# EEZ_DIB_MIO168_r1B1.net
KiCad netlist of a schematic drawn in EAGLE
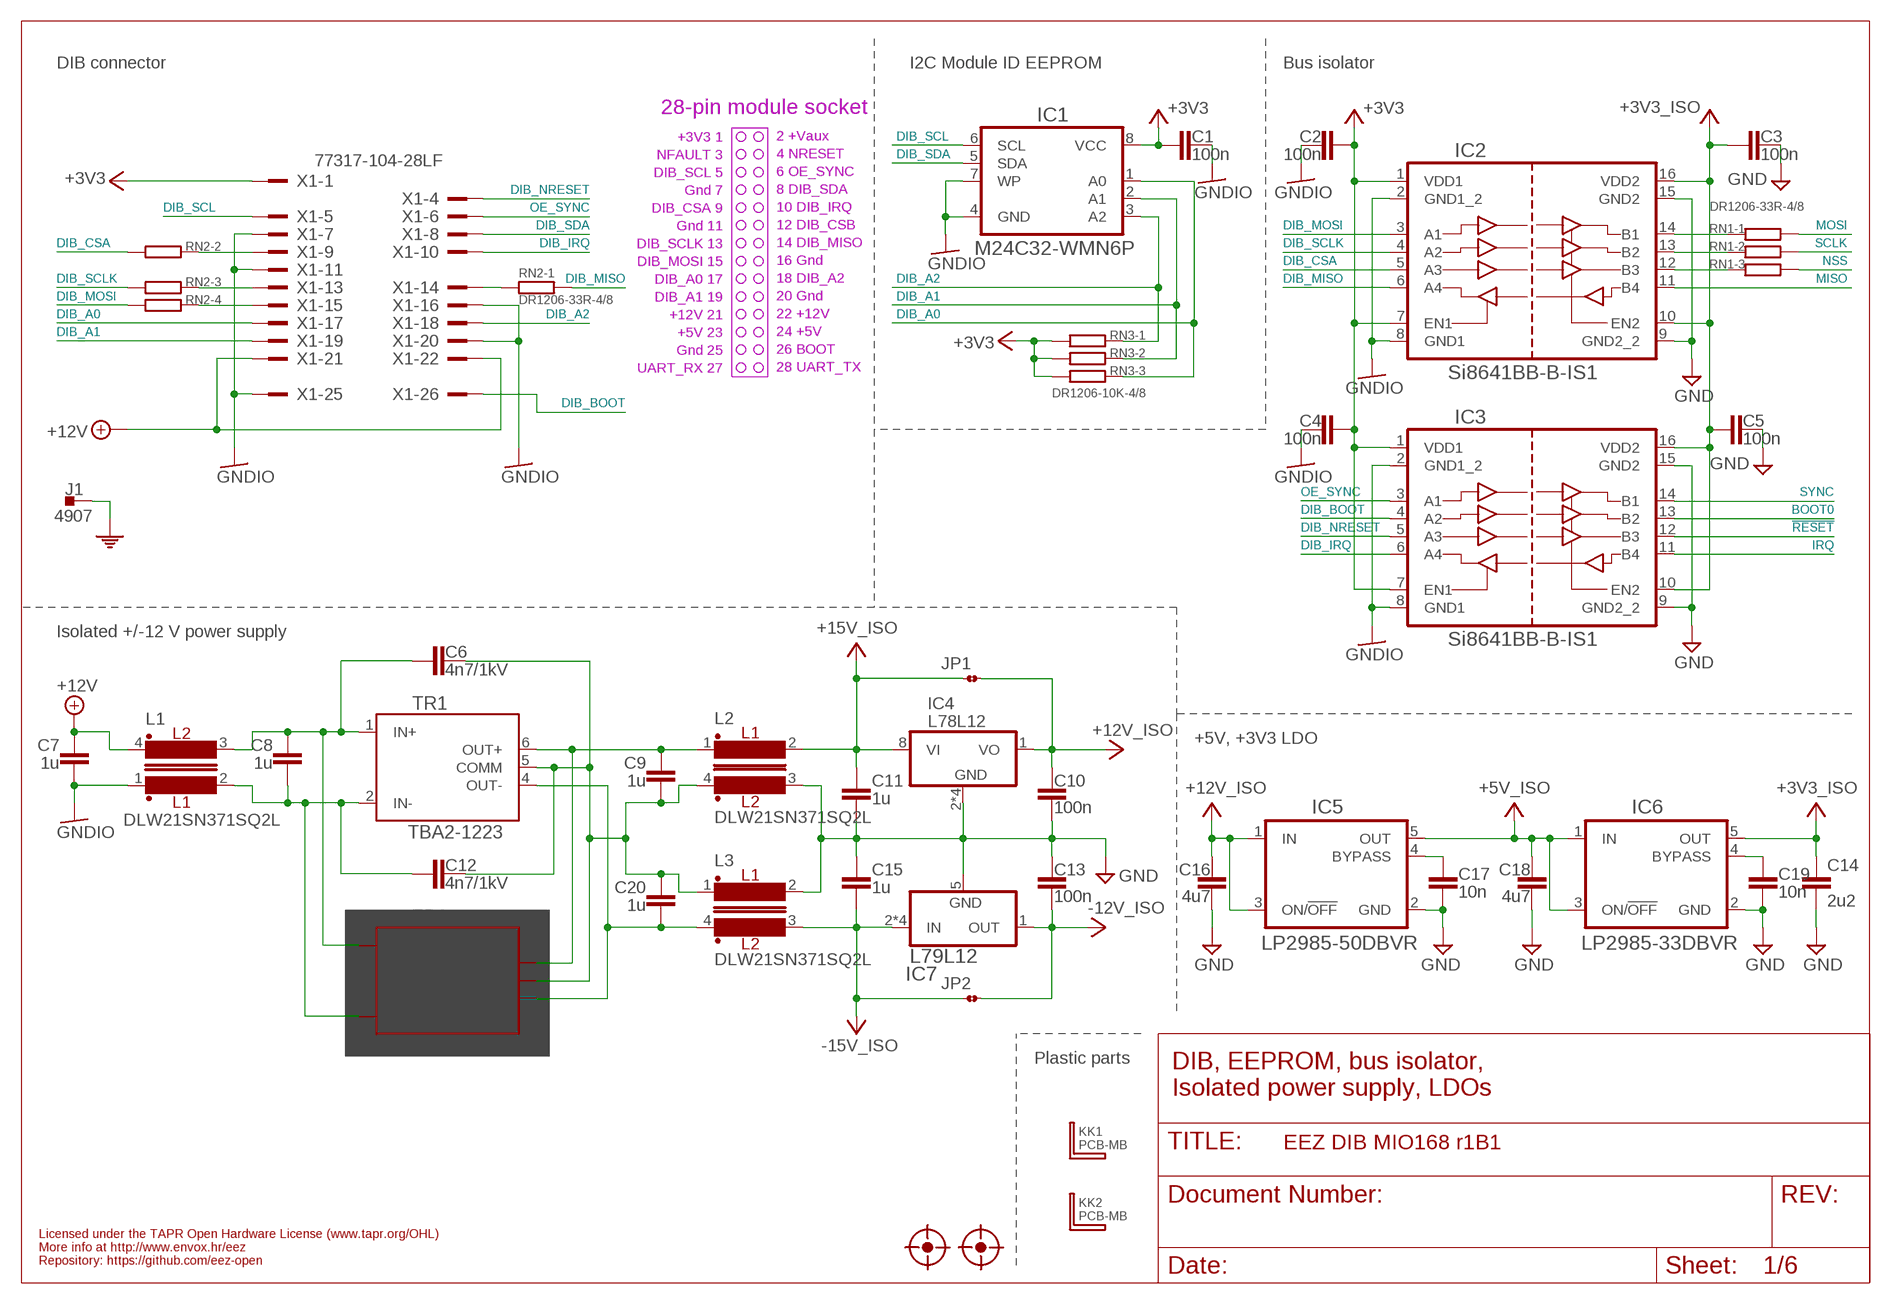
[diagram p0: schematic, sheet 1]
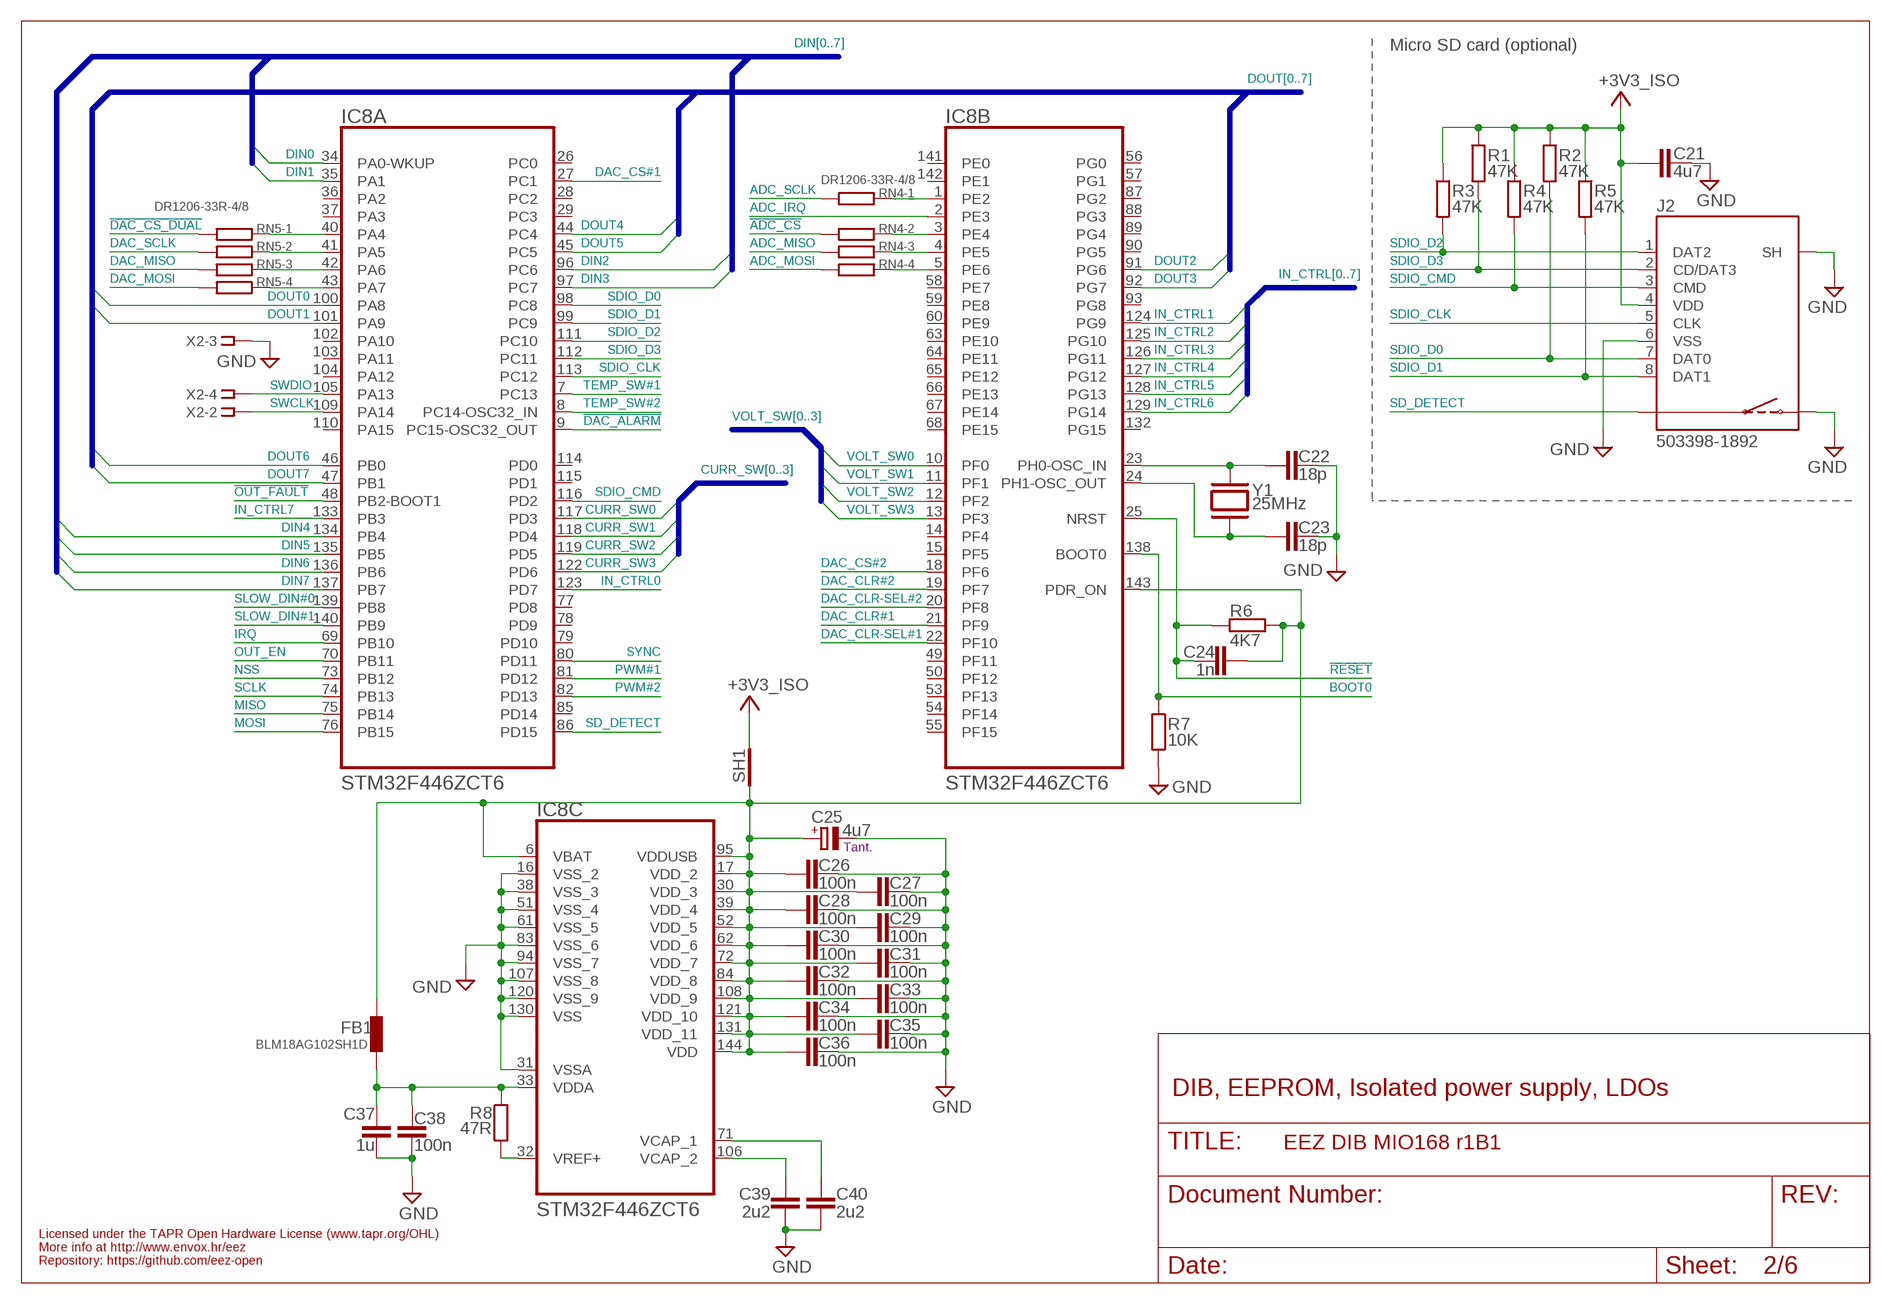
[diagram p1: schematic, sheet 2]
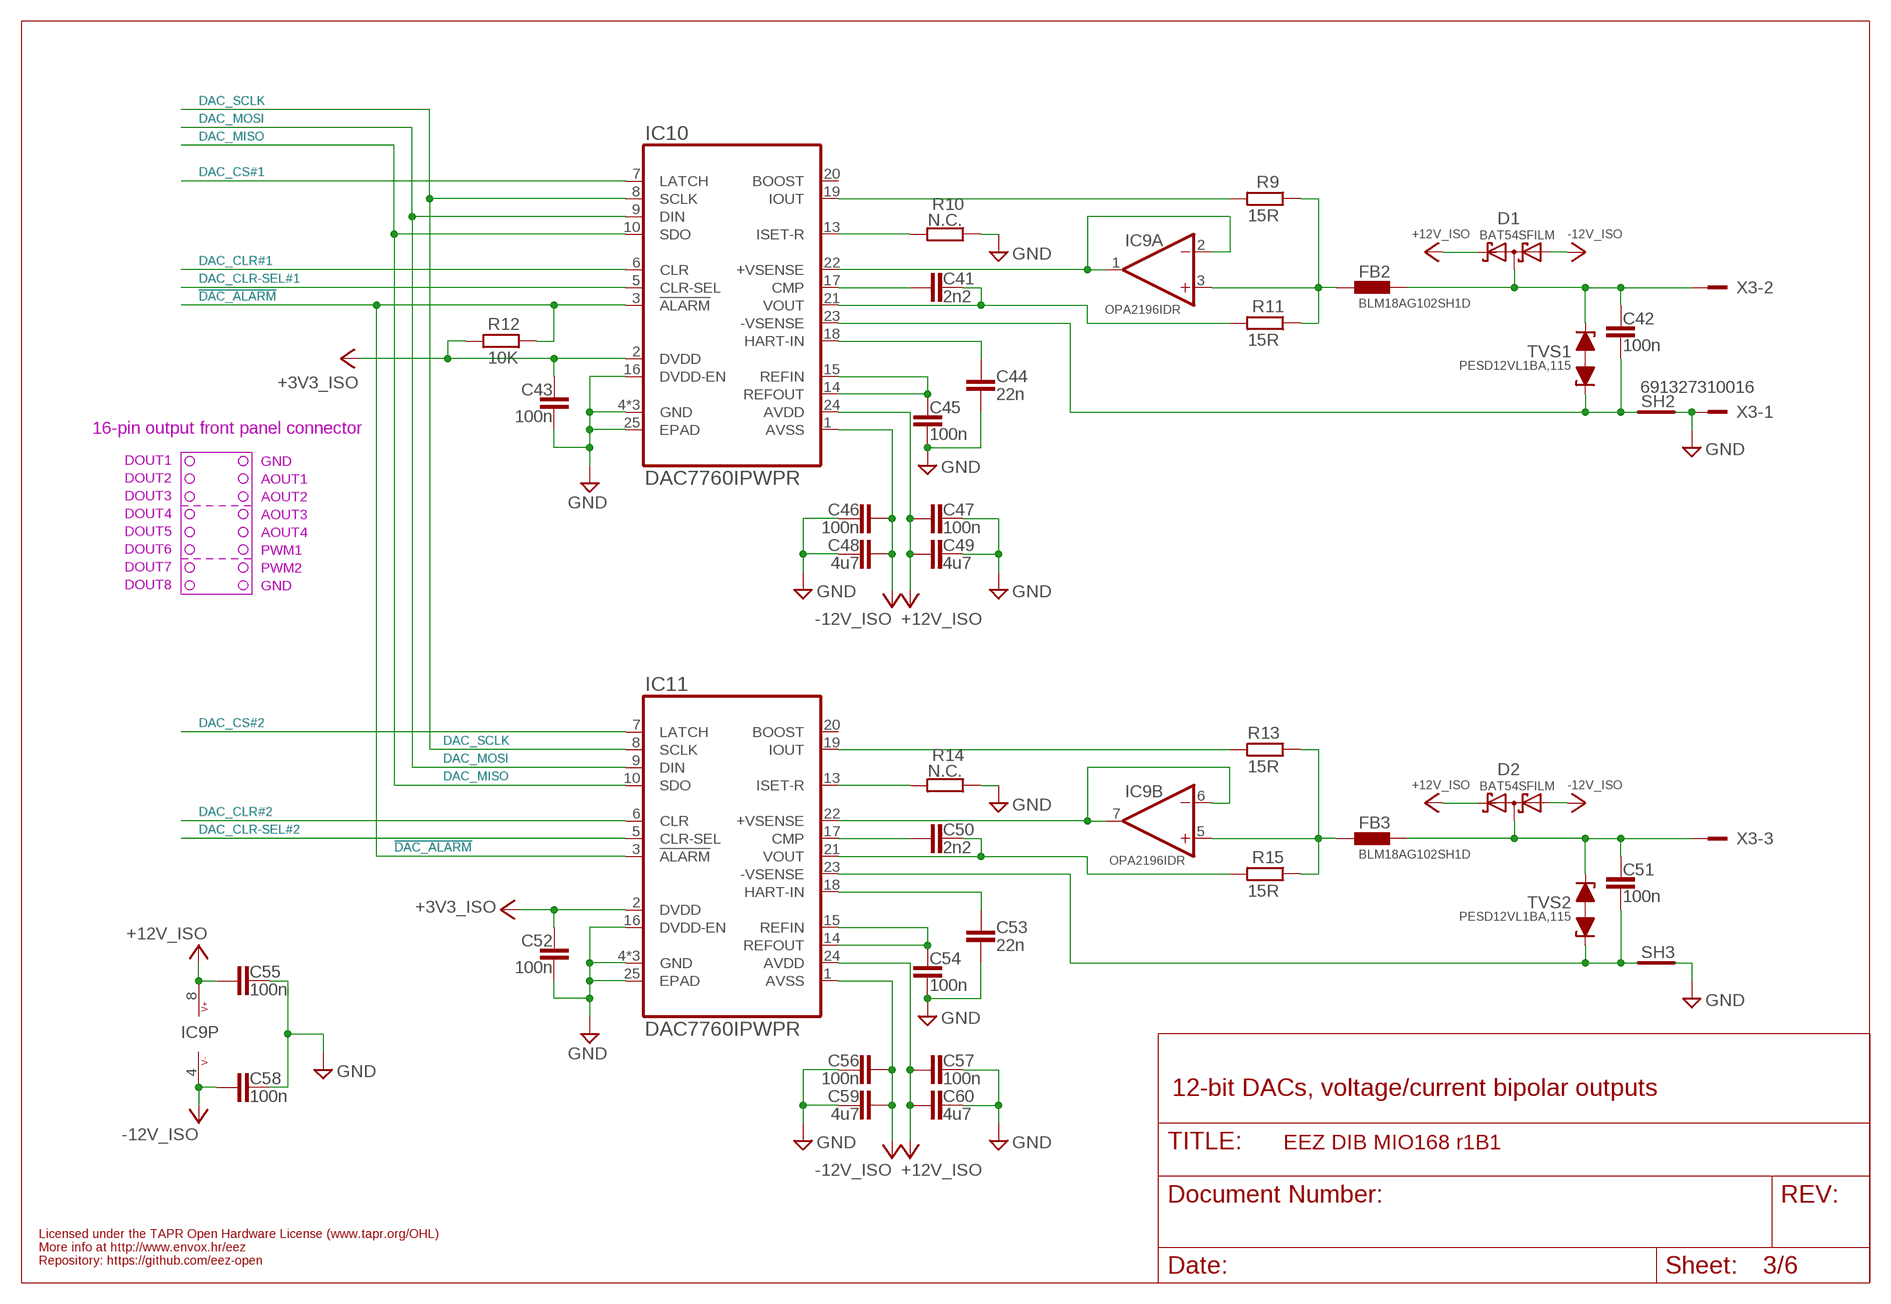
[diagram p2: schematic, sheet 3]
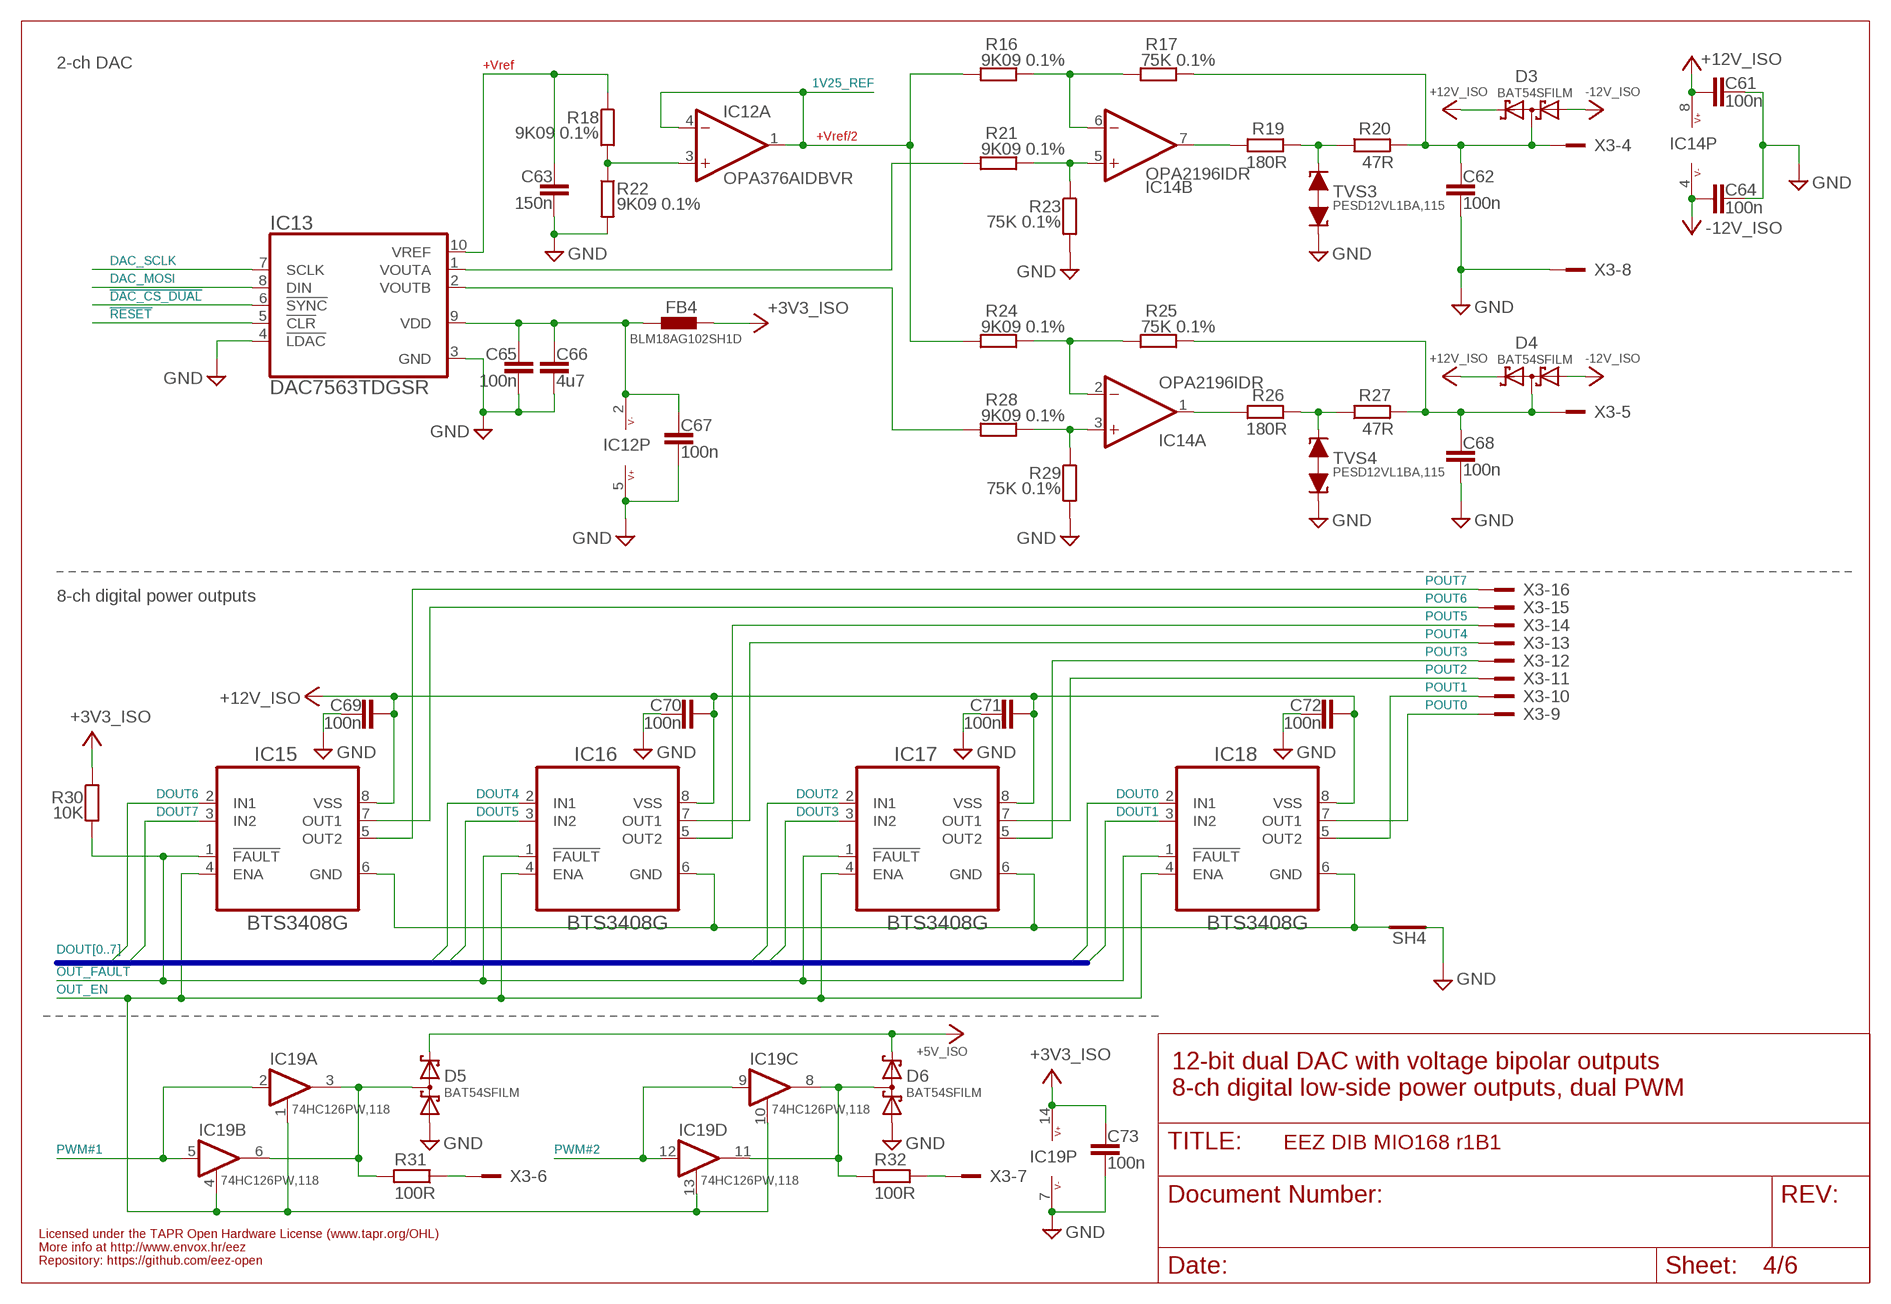
[diagram p3: schematic, sheet 4]
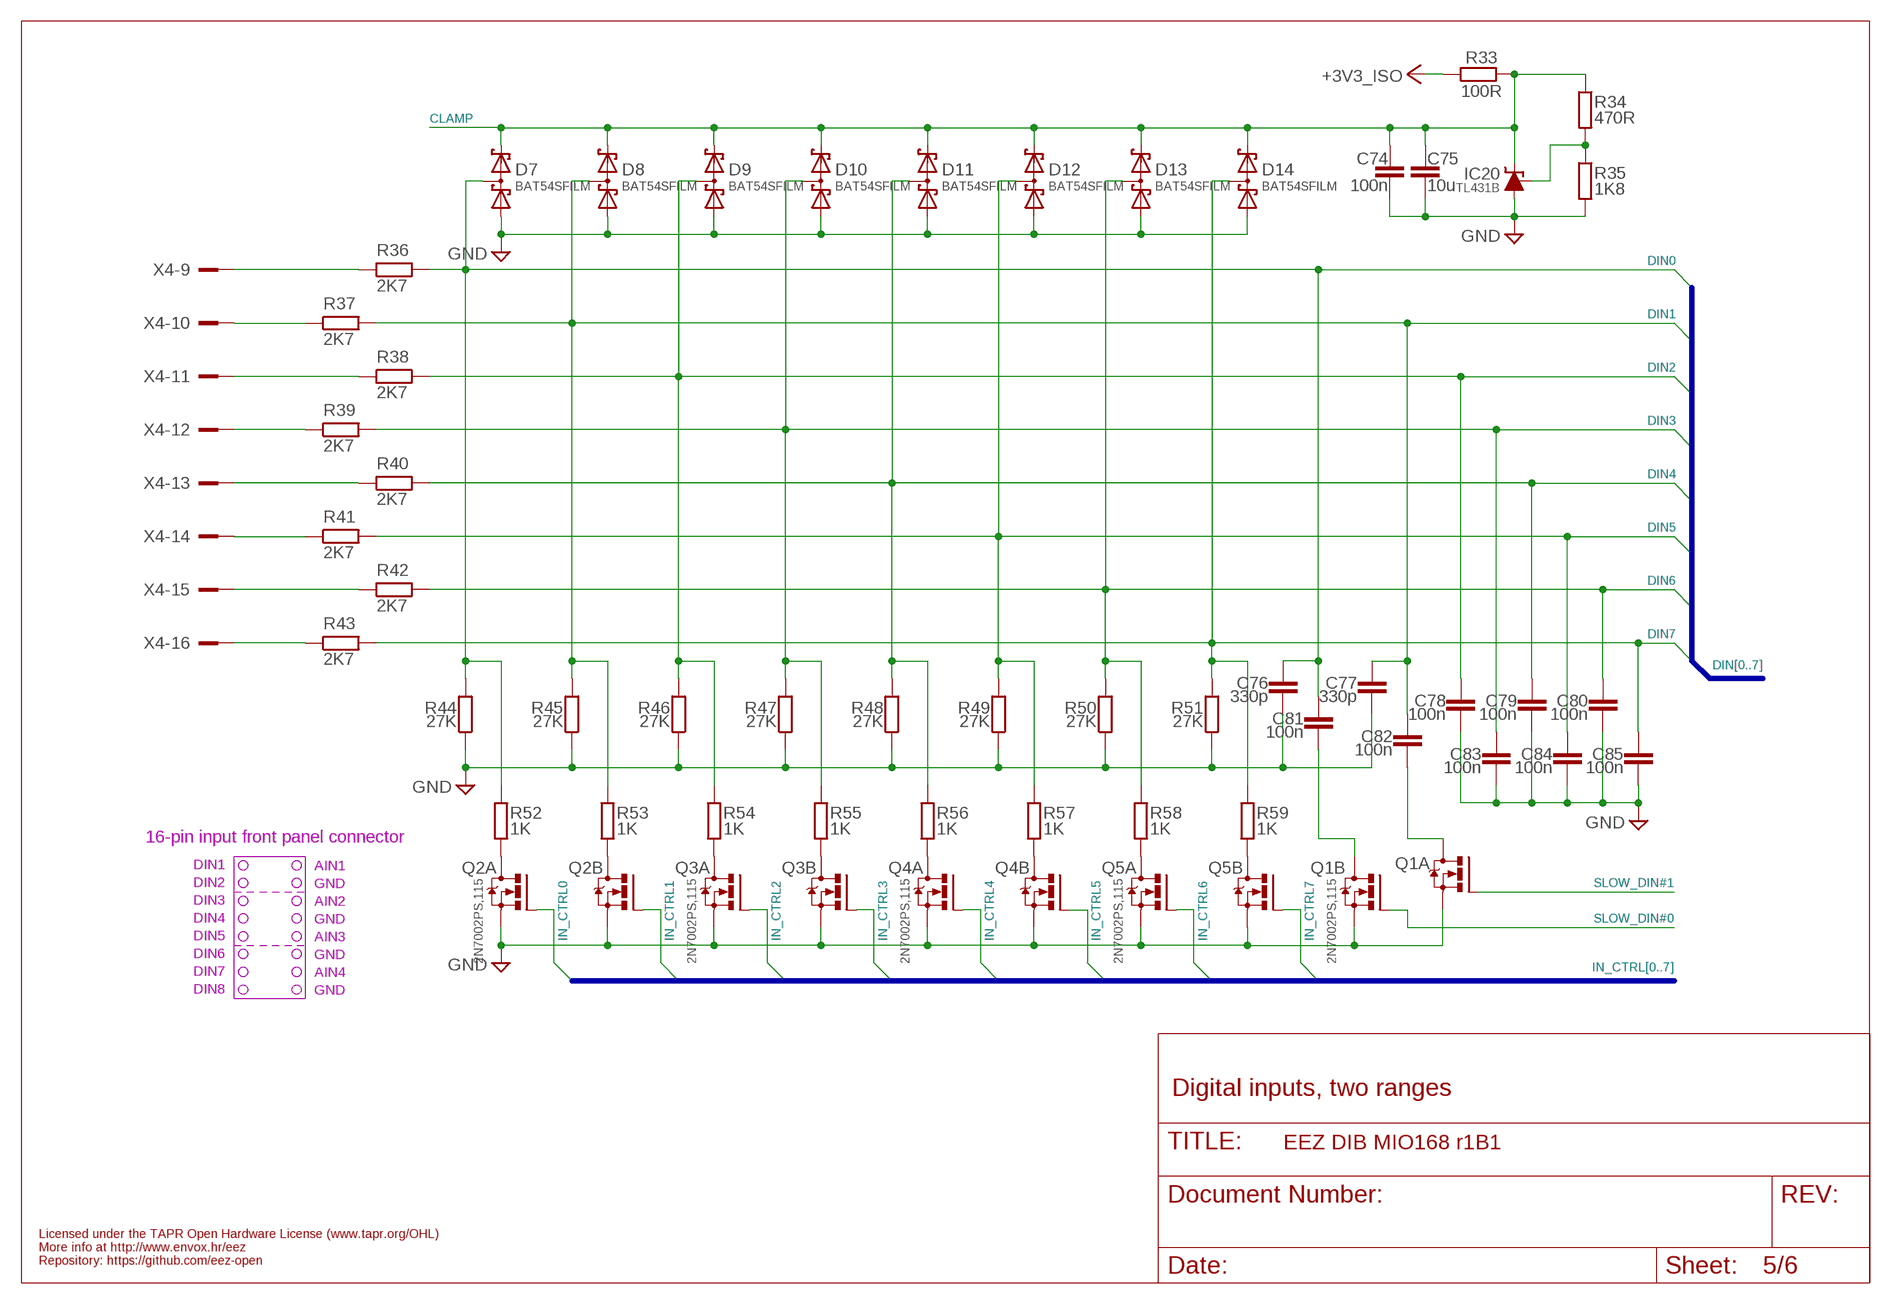
[diagram p4: schematic, sheet 5]
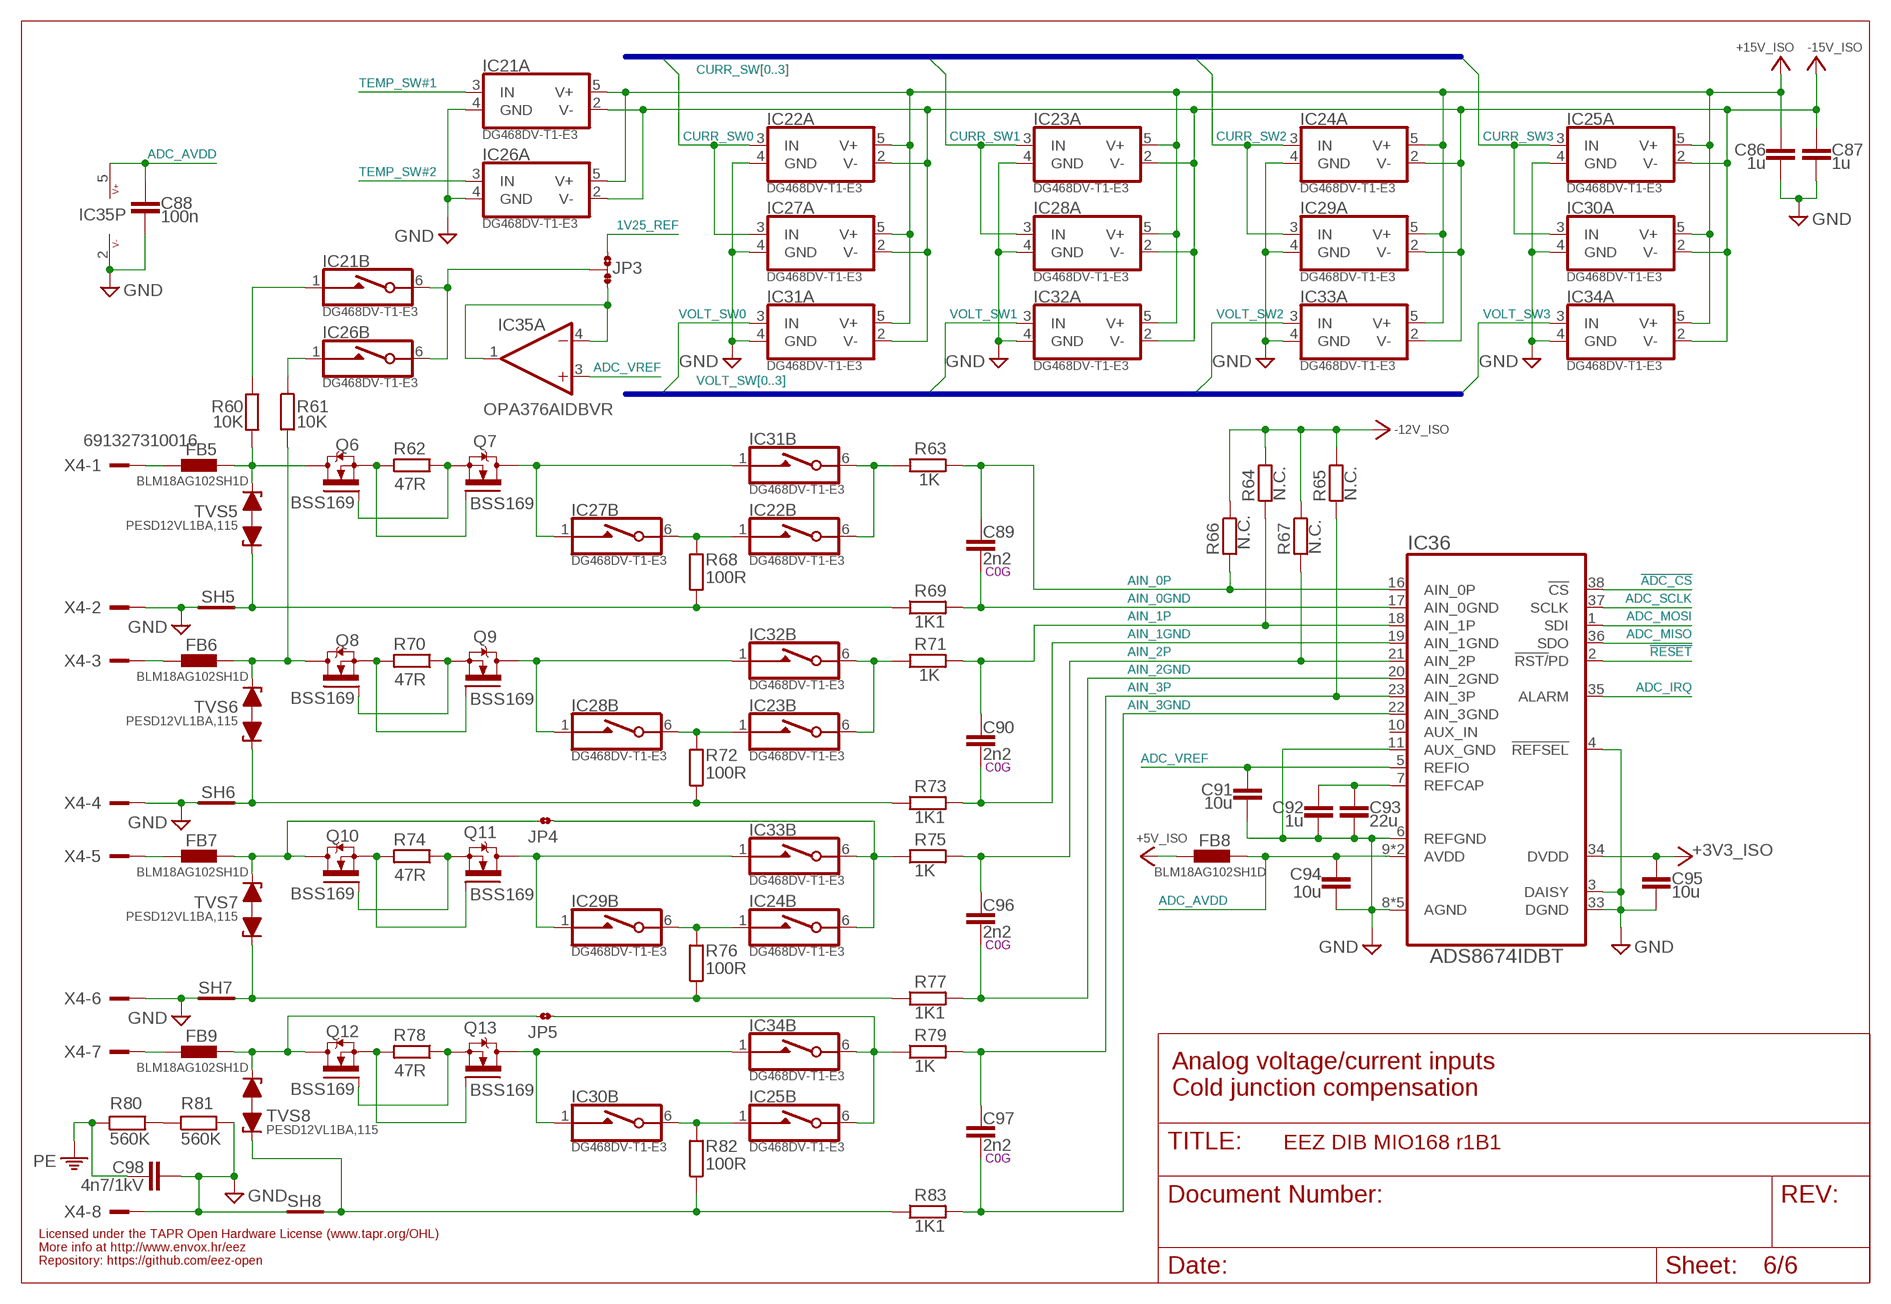
[diagram p5: schematic, sheet 6]

(export (version "E")
  (design (tool "Eeschema 10.0.6"))
  (components
    (comp (ref "C41")
      (value "2n2")
      (footprint "eagle-import:C0805")
      (libsource (lib "eagle-import") (part "C-EUC0805"))
    )
    (comp (ref "C42")
      (value "100n")
      (footprint "eagle-import:C0603")
      (libsource (lib "eagle-import") (part "C-EUC0603"))
    )
    (comp (ref "C43")
      (value "100n")
      (footprint "eagle-import:C0603")
      (libsource (lib "eagle-import") (part "C-EUC0603"))
    )
    (comp (ref "C44")
      (value "22n")
      (footprint "eagle-import:C0805")
      (libsource (lib "eagle-import") (part "C-EUC0805"))
    )
    (comp (ref "C45")
      (value "100n")
      (footprint "eagle-import:C0603")
      (libsource (lib "eagle-import") (part "C-EUC0603"))
    )
    (comp (ref "C46")
      (value "100n")
      (footprint "eagle-import:C0603")
      (libsource (lib "eagle-import") (part "C-EUC0603"))
    )
    (comp (ref "C47")
      (value "100n")
      (footprint "eagle-import:C0603")
      (libsource (lib "eagle-import") (part "C-EUC0603"))
    )
    (comp (ref "C48")
      (value "4u7")
      (footprint "eagle-import:C0805")
      (libsource (lib "eagle-import") (part "C-EUC0805"))
    )
    (comp (ref "C49")
      (value "4u7")
      (footprint "eagle-import:C0805")
      (libsource (lib "eagle-import") (part "C-EUC0805"))
    )
    (comp (ref "C50")
      (value "2n2")
      (footprint "eagle-import:C0805")
      (libsource (lib "eagle-import") (part "C-EUC0805"))
    )
    (comp (ref "C51")
      (value "100n")
      (footprint "eagle-import:C0603")
      (libsource (lib "eagle-import") (part "C-EUC0603"))
    )
    (comp (ref "C52")
      (value "100n")
      (footprint "eagle-import:C0603")
      (libsource (lib "eagle-import") (part "C-EUC0603"))
    )
    (comp (ref "C53")
      (value "22n")
      (footprint "eagle-import:C0805")
      (libsource (lib "eagle-import") (part "C-EUC0805"))
    )
    (comp (ref "C54")
      (value "100n")
      (footprint "eagle-import:C0603")
      (libsource (lib "eagle-import") (part "C-EUC0603"))
    )
    (comp (ref "C55")
      (value "100n")
      (footprint "eagle-import:C0603")
      (libsource (lib "eagle-import") (part "C-EUC0603"))
    )
    (comp (ref "C56")
      (value "100n")
      (footprint "eagle-import:C0603")
      (libsource (lib "eagle-import") (part "C-EUC0603"))
    )
    (comp (ref "C57")
      (value "100n")
      (footprint "eagle-import:C0603")
      (libsource (lib "eagle-import") (part "C-EUC0603"))
    )
    (comp (ref "C58")
      (value "100n")
      (footprint "eagle-import:C0603")
      (libsource (lib "eagle-import") (part "C-EUC0603"))
    )
    (comp (ref "C59")
      (value "4u7")
      (footprint "eagle-import:C0805")
      (libsource (lib "eagle-import") (part "C-EUC0805"))
    )
    (comp (ref "C60")
      (value "4u7")
      (footprint "eagle-import:C0805")
      (libsource (lib "eagle-import") (part "C-EUC0805"))
    )
    (comp (ref "D1")
      (value "BAT54SFILM")
      (footprint "eagle-import:SOT23")
      (libsource (lib "eagle-import") (part "BAT54S"))
    )
    (comp (ref "D2")
      (value "BAT54SFILM")
      (footprint "eagle-import:SOT23")
      (libsource (lib "eagle-import") (part "BAT54S"))
    )
    (comp (ref "FB2")
      (value "BLM18AG102SH1D")
      (footprint "eagle-import:BEAD0603")
      (libsource (lib "eagle-import") (part "FERRITE_BEAD0603"))
    )
    (comp (ref "FB3")
      (value "BLM18AG102SH1D")
      (footprint "eagle-import:BEAD0603")
      (libsource (lib "eagle-import") (part "FERRITE_BEAD0603"))
    )
    (comp (ref "IC9")
      (value "OPA2196IDR")
      (footprint "eagle-import:SOIC127P600X173-8N")
      (libsource (lib "eagle-import") (part "TL072SOIC8"))
    )
    (comp (ref "IC10")
      (value "DAC7760IPWPR")
      (footprint "eagle-import:PWP24")
      (libsource (lib "eagle-import") (part "DAC7760IPWPR"))
    )
    (comp (ref "IC11")
      (value "DAC7760IPWPR")
      (footprint "eagle-import:PWP24")
      (libsource (lib "eagle-import") (part "DAC7760IPWPR"))
    )
    (comp (ref "R9")
      (value "15R")
      (footprint "eagle-import:R0805")
      (libsource (lib "eagle-import") (part "R-EU_R0805"))
    )
    (comp (ref "R10")
      (value "N.C.")
      (footprint "eagle-import:R0805")
      (libsource (lib "eagle-import") (part "R-EU_R0805"))
    )
    (comp (ref "R11")
      (value "15R")
      (footprint "eagle-import:R0805")
      (libsource (lib "eagle-import") (part "R-EU_R0805"))
    )
    (comp (ref "R12")
      (value "10K")
      (footprint "eagle-import:R0805")
      (libsource (lib "eagle-import") (part "R-EU_R0805"))
    )
    (comp (ref "R13")
      (value "15R")
      (footprint "eagle-import:R0805")
      (libsource (lib "eagle-import") (part "R-EU_R0805"))
    )
    (comp (ref "R14")
      (value "N.C.")
      (footprint "eagle-import:R0805")
      (libsource (lib "eagle-import") (part "R-EU_R0805"))
    )
    (comp (ref "R15")
      (value "15R")
      (footprint "eagle-import:R0805")
      (libsource (lib "eagle-import") (part "R-EU_R0805"))
    )
    (comp (ref "SH2")
      (value "SHORTNOHOLE")
      (footprint "eagle-import:SHORT_NOHOLE")
      (libsource (lib "eagle-import") (part "SHORTNOHOLE"))
    )
    (comp (ref "SH3")
      (value "SHORTNOHOLE")
      (footprint "eagle-import:SHORT_NOHOLE")
      (libsource (lib "eagle-import") (part "SHORTNOHOLE"))
    )
    (comp (ref "TVS1")
      (value "PESD12VL1BA,115")
      (footprint "eagle-import:SOD323-BIDIR")
      (libsource (lib "eagle-import") (part "PESDXL1BA"))
    )
    (comp (ref "TVS2")
      (value "PESD12VL1BA,115")
      (footprint "eagle-import:SOD323-BIDIR")
      (libsource (lib "eagle-import") (part "PESDXL1BA"))
    )
    (comp (ref "X3")
      (value "691327310016")
      (footprint "eagle-import:691327310016")
      (libsource (lib "eagle-import") (part "691327310016"))
    )
    (comp (ref "C74")
      (value "100n")
      (footprint "eagle-import:C0603")
      (libsource (lib "eagle-import") (part "C-EUC0603"))
    )
    (comp (ref "C75")
      (value "10u")
      (footprint "eagle-import:C1206")
      (libsource (lib "eagle-import") (part "C-EUC1206"))
    )
    (comp (ref "C76")
      (value "330p")
      (footprint "eagle-import:C0805")
      (libsource (lib "eagle-import") (part "C-EUC0805"))
    )
    (comp (ref "C77")
      (value "330p")
      (footprint "eagle-import:C0805")
      (libsource (lib "eagle-import") (part "C-EUC0805"))
    )
    (comp (ref "C78")
      (value "100n")
      (footprint "eagle-import:C0603")
      (libsource (lib "eagle-import") (part "C-EUC0603"))
    )
    (comp (ref "C79")
      (value "100n")
      (footprint "eagle-import:C0603")
      (libsource (lib "eagle-import") (part "C-EUC0603"))
    )
    (comp (ref "C80")
      (value "100n")
      (footprint "eagle-import:C0603")
      (libsource (lib "eagle-import") (part "C-EUC0603"))
    )
    (comp (ref "C81")
      (value "100n")
      (footprint "eagle-import:C0603")
      (libsource (lib "eagle-import") (part "C-EUC0603"))
    )
    (comp (ref "C82")
      (value "100n")
      (footprint "eagle-import:C0603")
      (libsource (lib "eagle-import") (part "C-EUC0603"))
    )
    (comp (ref "C83")
      (value "100n")
      (footprint "eagle-import:C0603")
      (libsource (lib "eagle-import") (part "C-EUC0603"))
    )
    (comp (ref "C84")
      (value "100n")
      (footprint "eagle-import:C0603")
      (libsource (lib "eagle-import") (part "C-EUC0603"))
    )
    (comp (ref "C85")
      (value "100n")
      (footprint "eagle-import:C0603")
      (libsource (lib "eagle-import") (part "C-EUC0603"))
    )
    (comp (ref "D7")
      (value "BAT54SFILM")
      (footprint "eagle-import:SOT23")
      (libsource (lib "eagle-import") (part "BAT54S"))
    )
    (comp (ref "D8")
      (value "BAT54SFILM")
      (footprint "eagle-import:SOT23")
      (libsource (lib "eagle-import") (part "BAT54S"))
    )
    (comp (ref "D9")
      (value "BAT54SFILM")
      (footprint "eagle-import:SOT23")
      (libsource (lib "eagle-import") (part "BAT54S"))
    )
    (comp (ref "D10")
      (value "BAT54SFILM")
      (footprint "eagle-import:SOT23")
      (libsource (lib "eagle-import") (part "BAT54S"))
    )
    (comp (ref "D11")
      (value "BAT54SFILM")
      (footprint "eagle-import:SOT23")
      (libsource (lib "eagle-import") (part "BAT54S"))
    )
    (comp (ref "D12")
      (value "BAT54SFILM")
      (footprint "eagle-import:SOT23")
      (libsource (lib "eagle-import") (part "BAT54S"))
    )
    (comp (ref "D13")
      (value "BAT54SFILM")
      (footprint "eagle-import:SOT23")
      (libsource (lib "eagle-import") (part "BAT54S"))
    )
    (comp (ref "D14")
      (value "BAT54SFILM")
      (footprint "eagle-import:SOT23")
      (libsource (lib "eagle-import") (part "BAT54S"))
    )
    (comp (ref "IC20")
      (value "TL431B")
      (footprint "eagle-import:SOT103P240X110-3N")
      (libsource (lib "eagle-import") (part "TL431"))
    )
    (comp (ref "Q1")
      (value "2N7002PS,115")
      (footprint "eagle-import:SC88")
      (libsource (lib "eagle-import") (part "2N7002PS,115"))
    )
    (comp (ref "Q2")
      (value "2N7002PS,115")
      (footprint "eagle-import:SC88")
      (libsource (lib "eagle-import") (part "2N7002PS,115"))
    )
    (comp (ref "Q3")
      (value "2N7002PS,115")
      (footprint "eagle-import:SC88")
      (libsource (lib "eagle-import") (part "2N7002PS,115"))
    )
    (comp (ref "Q4")
      (value "2N7002PS,115")
      (footprint "eagle-import:SC88")
      (libsource (lib "eagle-import") (part "2N7002PS,115"))
    )
    (comp (ref "Q5")
      (value "2N7002PS,115")
      (footprint "eagle-import:SC88")
      (libsource (lib "eagle-import") (part "2N7002PS,115"))
    )
    (comp (ref "R33")
      (value "100R")
      (footprint "eagle-import:R0805")
      (libsource (lib "eagle-import") (part "R-EU_R0805"))
    )
    (comp (ref "R34")
      (value "470R")
      (footprint "eagle-import:R0805")
      (libsource (lib "eagle-import") (part "R-EU_R0805"))
    )
    (comp (ref "R35")
      (value "1K8")
      (footprint "eagle-import:R0805")
      (libsource (lib "eagle-import") (part "R-EU_R0805"))
    )
    (comp (ref "R36")
      (value "2K7")
      (footprint "eagle-import:R1206")
      (libsource (lib "eagle-import") (part "R-EU_R1206"))
    )
    (comp (ref "R37")
      (value "2K7")
      (footprint "eagle-import:R1206")
      (libsource (lib "eagle-import") (part "R-EU_R1206"))
    )
    (comp (ref "R38")
      (value "2K7")
      (footprint "eagle-import:R1206")
      (libsource (lib "eagle-import") (part "R-EU_R1206"))
    )
    (comp (ref "R39")
      (value "2K7")
      (footprint "eagle-import:R1206")
      (libsource (lib "eagle-import") (part "R-EU_R1206"))
    )
    (comp (ref "R40")
      (value "2K7")
      (footprint "eagle-import:R1206")
      (libsource (lib "eagle-import") (part "R-EU_R1206"))
    )
    (comp (ref "R41")
      (value "2K7")
      (footprint "eagle-import:R1206")
      (libsource (lib "eagle-import") (part "R-EU_R1206"))
    )
    (comp (ref "R42")
      (value "2K7")
      (footprint "eagle-import:R1206")
      (libsource (lib "eagle-import") (part "R-EU_R1206"))
    )
    (comp (ref "R43")
      (value "2K7")
      (footprint "eagle-import:R1206")
      (libsource (lib "eagle-import") (part "R-EU_R1206"))
    )
    (comp (ref "R44")
      (value "27K")
      (footprint "eagle-import:R0805")
      (libsource (lib "eagle-import") (part "R-EU_R0805"))
    )
    (comp (ref "R45")
      (value "27K")
      (footprint "eagle-import:R0805")
      (libsource (lib "eagle-import") (part "R-EU_R0805"))
    )
    (comp (ref "R46")
      (value "27K")
      (footprint "eagle-import:R0805")
      (libsource (lib "eagle-import") (part "R-EU_R0805"))
    )
    (comp (ref "R47")
      (value "27K")
      (footprint "eagle-import:R0805")
      (libsource (lib "eagle-import") (part "R-EU_R0805"))
    )
    (comp (ref "R48")
      (value "27K")
      (footprint "eagle-import:R0805")
      (libsource (lib "eagle-import") (part "R-EU_R0805"))
    )
    (comp (ref "R49")
      (value "27K")
      (footprint "eagle-import:R0805")
      (libsource (lib "eagle-import") (part "R-EU_R0805"))
    )
    (comp (ref "R50")
      (value "27K")
      (footprint "eagle-import:R0805")
      (libsource (lib "eagle-import") (part "R-EU_R0805"))
    )
    (comp (ref "R51")
      (value "27K")
      (footprint "eagle-import:R0805")
      (libsource (lib "eagle-import") (part "R-EU_R0805"))
    )
    (comp (ref "R52")
      (value "1K")
      (footprint "eagle-import:R0805")
      (libsource (lib "eagle-import") (part "R-EU_R0805"))
    )
    (comp (ref "R53")
      (value "1K")
      (footprint "eagle-import:R0805")
      (libsource (lib "eagle-import") (part "R-EU_R0805"))
    )
    (comp (ref "R54")
      (value "1K")
      (footprint "eagle-import:R0805")
      (libsource (lib "eagle-import") (part "R-EU_R0805"))
    )
    (comp (ref "R55")
      (value "1K")
      (footprint "eagle-import:R0805")
      (libsource (lib "eagle-import") (part "R-EU_R0805"))
    )
    (comp (ref "R56")
      (value "1K")
      (footprint "eagle-import:R0805")
      (libsource (lib "eagle-import") (part "R-EU_R0805"))
    )
    (comp (ref "R57")
      (value "1K")
      (footprint "eagle-import:R0805")
      (libsource (lib "eagle-import") (part "R-EU_R0805"))
    )
    (comp (ref "R58")
      (value "1K")
      (footprint "eagle-import:R0805")
      (libsource (lib "eagle-import") (part "R-EU_R0805"))
    )
    (comp (ref "R59")
      (value "1K")
      (footprint "eagle-import:R0805")
      (libsource (lib "eagle-import") (part "R-EU_R0805"))
    )
    (comp (ref "X4")
      (value "691327310016")
      (footprint "eagle-import:691327310016")
      (libsource (lib "eagle-import") (part "691327310016"))
    )
    (comp (ref "C21")
      (value "4u7")
      (footprint "eagle-import:C0805")
      (libsource (lib "eagle-import") (part "C-EUC0805"))
    )
    (comp (ref "C22")
      (value "18p")
      (footprint "eagle-import:C0603")
      (libsource (lib "eagle-import") (part "C-EUC0603"))
    )
    (comp (ref "C23")
      (value "18p")
      (footprint "eagle-import:C0603")
      (libsource (lib "eagle-import") (part "C-EUC0603"))
    )
    (comp (ref "C24")
      (value "1n")
      (footprint "eagle-import:C0805")
      (libsource (lib "eagle-import") (part "C-EUC0805"))
    )
    (comp (ref "C25")
      (value "4u7")
      (footprint "eagle-import:EC1206")
      (libsource (lib "eagle-import") (part "ECAP1206"))
    )
    (comp (ref "C26")
      (value "100n")
      (footprint "eagle-import:C0603")
      (libsource (lib "eagle-import") (part "C-EUC0603"))
    )
    (comp (ref "C27")
      (value "100n")
      (footprint "eagle-import:C0603")
      (libsource (lib "eagle-import") (part "C-EUC0603"))
    )
    (comp (ref "C28")
      (value "100n")
      (footprint "eagle-import:C0603")
      (libsource (lib "eagle-import") (part "C-EUC0603"))
    )
    (comp (ref "C29")
      (value "100n")
      (footprint "eagle-import:C0603")
      (libsource (lib "eagle-import") (part "C-EUC0603"))
    )
    (comp (ref "C30")
      (value "100n")
      (footprint "eagle-import:C0603")
      (libsource (lib "eagle-import") (part "C-EUC0603"))
    )
    (comp (ref "C31")
      (value "100n")
      (footprint "eagle-import:C0603")
      (libsource (lib "eagle-import") (part "C-EUC0603"))
    )
    (comp (ref "C32")
      (value "100n")
      (footprint "eagle-import:C0603")
      (libsource (lib "eagle-import") (part "C-EUC0603"))
    )
    (comp (ref "C33")
      (value "100n")
      (footprint "eagle-import:C0603")
      (libsource (lib "eagle-import") (part "C-EUC0603"))
    )
    (comp (ref "C34")
      (value "100n")
      (footprint "eagle-import:C0603")
      (libsource (lib "eagle-import") (part "C-EUC0603"))
    )
    (comp (ref "C35")
      (value "100n")
      (footprint "eagle-import:C0603")
      (libsource (lib "eagle-import") (part "C-EUC0603"))
    )
    (comp (ref "C36")
      (value "100n")
      (footprint "eagle-import:C0603")
      (libsource (lib "eagle-import") (part "C-EUC0603"))
    )
    (comp (ref "C37")
      (value "1u")
      (footprint "eagle-import:C0805")
      (libsource (lib "eagle-import") (part "C-EUC0805"))
    )
    (comp (ref "C38")
      (value "100n")
      (footprint "eagle-import:C0603")
      (libsource (lib "eagle-import") (part "C-EUC0603"))
    )
    (comp (ref "C39")
      (value "2u2")
      (footprint "eagle-import:C0805")
      (libsource (lib "eagle-import") (part "C-EUC0805"))
    )
    (comp (ref "C40")
      (value "2u2")
      (footprint "eagle-import:C0805")
      (libsource (lib "eagle-import") (part "C-EUC0805"))
    )
    (comp (ref "FB1")
      (value "BLM18AG102SH1D")
      (footprint "eagle-import:BEAD0603")
      (libsource (lib "eagle-import") (part "FERRITE_BEAD0603"))
    )
    (comp (ref "IC8")
      (value "STM32F446ZCT6")
      (footprint "eagle-import:LQFP-144")
      (libsource (lib "eagle-import") (part "STM32F446ZCT6"))
    )
    (comp (ref "J2")
      (value "503398-1892")
      (footprint "eagle-import:5033981892")
      (libsource (lib "eagle-import") (part "5033981892"))
    )
    (comp (ref "R1")
      (value "47K")
      (footprint "eagle-import:R0805")
      (libsource (lib "eagle-import") (part "R-EU_R0805"))
    )
    (comp (ref "R2")
      (value "47K")
      (footprint "eagle-import:R0805")
      (libsource (lib "eagle-import") (part "R-EU_R0805"))
    )
    (comp (ref "R3")
      (value "47K")
      (footprint "eagle-import:R0805")
      (libsource (lib "eagle-import") (part "R-EU_R0805"))
    )
    (comp (ref "R4")
      (value "47K")
      (footprint "eagle-import:R0805")
      (libsource (lib "eagle-import") (part "R-EU_R0805"))
    )
    (comp (ref "R5")
      (value "47K")
      (footprint "eagle-import:R0805")
      (libsource (lib "eagle-import") (part "R-EU_R0805"))
    )
    (comp (ref "R6")
      (value "4K7")
      (footprint "eagle-import:R0805")
      (libsource (lib "eagle-import") (part "R-EU_R0805"))
    )
    (comp (ref "R7")
      (value "10K")
      (footprint "eagle-import:R0805")
      (libsource (lib "eagle-import") (part "R-EU_R0805"))
    )
    (comp (ref "R8")
      (value "47R")
      (footprint "eagle-import:R0805")
      (libsource (lib "eagle-import") (part "R-EU_R0805"))
    )
    (comp (ref "RN4")
      (value "DR1206-33R-4/8")
      (footprint "eagle-import:CAY16")
      (libsource (lib "eagle-import") (part "R_ARRAY4"))
    )
    (comp (ref "RN5")
      (value "DR1206-33R-4/8")
      (footprint "eagle-import:CAY16")
      (libsource (lib "eagle-import") (part "R_ARRAY4"))
    )
    (comp (ref "SH1")
      (value "SHORTNOHOLE")
      (footprint "eagle-import:SHORT_NOHOLE")
      (libsource (lib "eagle-import") (part "SHORTNOHOLE"))
    )
    (comp (ref "X2")
      (value "SSW-106-02-S-S")
      (footprint "eagle-import:SSW-106-02-S-S")
      (libsource (lib "eagle-import") (part "SSW-106-02-S-S"))
    )
    (comp (ref "Y1")
      (value "25MHz")
      (footprint "eagle-import:HC-49_4H")
      (libsource (lib "eagle-import") (part "XTALSMD"))
    )
    (comp (ref "C1")
      (value "100n")
      (footprint "eagle-import:C0603")
      (libsource (lib "eagle-import") (part "C-EUC0603"))
    )
    (comp (ref "C2")
      (value "100n")
      (footprint "eagle-import:C0603")
      (libsource (lib "eagle-import") (part "C-EUC0603"))
    )
    (comp (ref "C3")
      (value "100n")
      (footprint "eagle-import:C0603")
      (libsource (lib "eagle-import") (part "C-EUC0603"))
    )
    (comp (ref "C4")
      (value "100n")
      (footprint "eagle-import:C0603")
      (libsource (lib "eagle-import") (part "C-EUC0603"))
    )
    (comp (ref "C5")
      (value "100n")
      (footprint "eagle-import:C0603")
      (libsource (lib "eagle-import") (part "C-EUC0603"))
    )
    (comp (ref "C6")
      (value "4n7/1kV")
      (footprint "eagle-import:C1812")
      (libsource (lib "eagle-import") (part "C-EUC1812"))
    )
    (comp (ref "C7")
      (value "1u")
      (footprint "eagle-import:C0805")
      (libsource (lib "eagle-import") (part "C-EUC0805"))
    )
    (comp (ref "C8")
      (value "1u")
      (footprint "eagle-import:C0805")
      (libsource (lib "eagle-import") (part "C-EUC0805"))
    )
    (comp (ref "C9")
      (value "1u")
      (footprint "eagle-import:C0805")
      (libsource (lib "eagle-import") (part "C-EUC0805"))
    )
    (comp (ref "C10")
      (value "100n")
      (footprint "eagle-import:C0603")
      (libsource (lib "eagle-import") (part "C-EUC0603"))
    )
    (comp (ref "C11")
      (value "1u")
      (footprint "eagle-import:C0805")
      (libsource (lib "eagle-import") (part "C-EUC0805"))
    )
    (comp (ref "C12")
      (value "4n7/1kV")
      (footprint "eagle-import:C1812")
      (libsource (lib "eagle-import") (part "C-EUC1812"))
    )
    (comp (ref "C13")
      (value "100n")
      (footprint "eagle-import:C0603")
      (libsource (lib "eagle-import") (part "C-EUC0603"))
    )
    (comp (ref "C14")
      (value "2u2")
      (footprint "eagle-import:C0805")
      (libsource (lib "eagle-import") (part "C-EUC0805"))
    )
    (comp (ref "C15")
      (value "1u")
      (footprint "eagle-import:C0805")
      (libsource (lib "eagle-import") (part "C-EUC0805"))
    )
    (comp (ref "C16")
      (value "4u7")
      (footprint "eagle-import:C0805")
      (libsource (lib "eagle-import") (part "C-EUC0805"))
    )
    (comp (ref "C17")
      (value "10n")
      (footprint "eagle-import:C0805")
      (libsource (lib "eagle-import") (part "C-EUC0805"))
    )
    (comp (ref "C18")
      (value "4u7")
      (footprint "eagle-import:C0805")
      (libsource (lib "eagle-import") (part "C-EUC0805"))
    )
    (comp (ref "C19")
      (value "10n")
      (footprint "eagle-import:C0805")
      (libsource (lib "eagle-import") (part "C-EUC0805"))
    )
    (comp (ref "C20")
      (value "1u")
      (footprint "eagle-import:C0805")
      (libsource (lib "eagle-import") (part "C-EUC0805"))
    )
    (comp (ref "FM1")
      (value "FIDUCIAL_2")
      (footprint "eagle-import:FIDUCIAL_DUAL")
      (libsource (lib "eagle-import") (part "FIDUCIAL_2"))
    )
    (comp (ref "FM2")
      (value "FIDUCIAL_2")
      (footprint "eagle-import:FIDUCIAL_DUAL")
      (libsource (lib "eagle-import") (part "FIDUCIAL_2"))
    )
    (comp (ref "IC1")
      (value "M24C32-WMN6P")
      (footprint "eagle-import:SOIC127P600X173-8N")
      (libsource (lib "eagle-import") (part "AT24CXXSOIC8"))
    )
    (comp (ref "IC2")
      (value "Si8641BB-B-IS1")
      (footprint "eagle-import:SOIC-16")
      (libsource (lib "eagle-import") (part "SI8641NSOIC-16"))
    )
    (comp (ref "IC3")
      (value "Si8641BB-B-IS1")
      (footprint "eagle-import:SOIC-16")
      (libsource (lib "eagle-import") (part "SI8641NSOIC-16"))
    )
    (comp (ref "IC4")
      (value "L78L12")
      (footprint "eagle-import:SOIC127P600X173-8N")
      (libsource (lib "eagle-import") (part "MC78LXXSOIC8"))
    )
    (comp (ref "IC5")
      (value "LP2985-50DBVR")
      (footprint "eagle-import:SOT95P270X145-5N")
      (libsource (lib "eagle-import") (part "LP2985"))
    )
    (comp (ref "IC6")
      (value "LP2985-33DBVR")
      (footprint "eagle-import:SOT95P270X145-5N")
      (libsource (lib "eagle-import") (part "LP2985"))
    )
    (comp (ref "IC7")
      (value "L79L12")
      (footprint "eagle-import:SOIC127P600X173-8N")
      (libsource (lib "eagle-import") (part "MC79LXXSOIC"))
    )
    (comp (ref "J1")
      (value "4907")
      (footprint "eagle-import:PCB_TAB-4907")
      (libsource (lib "eagle-import") (part "PCB_TAB-4907"))
    )
    (comp (ref "JP1")
      (value "JP2-CUT-0805")
      (footprint "eagle-import:R_0805")
      (libsource (lib "eagle-import") (part "JP2-CUT-0805"))
    )
    (comp (ref "JP2")
      (value "JP2-CUT-0805")
      (footprint "eagle-import:R_0805")
      (libsource (lib "eagle-import") (part "JP2-CUT-0805"))
    )
    (comp (ref "KK1")
      (value "PCB-MB")
      (footprint "eagle-import:PCB-MB")
      (libsource (lib "eagle-import") (part "PCB-MB"))
    )
    (comp (ref "KK2")
      (value "PCB-MB")
      (footprint "eagle-import:PCB-MB")
      (libsource (lib "eagle-import") (part "PCB-MB"))
    )
    (comp (ref "L1")
      (value "DLW21SN371SQ2L")
      (footprint "eagle-import:MURATA_DLW21S")
      (libsource (lib "eagle-import") (part "DLW21S"))
    )
    (comp (ref "L2")
      (value "DLW21SN371SQ2L")
      (footprint "eagle-import:MURATA_DLW21S")
      (libsource (lib "eagle-import") (part "DLW21S"))
    )
    (comp (ref "L3")
      (value "DLW21SN371SQ2L")
      (footprint "eagle-import:MURATA_DLW21S")
      (libsource (lib "eagle-import") (part "DLW21S"))
    )
    (comp (ref "RN1")
      (value "DR1206-33R-4/8")
      (footprint "eagle-import:CAY16")
      (libsource (lib "eagle-import") (part "R_ARRAY4"))
    )
    (comp (ref "RN2")
      (value "DR1206-33R-4/8")
      (footprint "eagle-import:CAY16")
      (libsource (lib "eagle-import") (part "R_ARRAY4"))
    )
    (comp (ref "RN3")
      (value "DR1206-10K-4/8")
      (footprint "eagle-import:CAY16")
      (libsource (lib "eagle-import") (part "R_ARRAY4"))
    )
    (comp (ref "TR1")
      (value "TBA2-1223")
      (footprint "eagle-import:TBA2")
      (libsource (lib "eagle-import") (part "TBA-DUAL-2W"))
    )
    (comp (ref "TR2")
      (value "MDD02M-15")
      (footprint "eagle-import:MDD02")
      (libsource (lib "eagle-import") (part "MDD02"))
    )
    (comp (ref "X1")
      (value "77317-104-28LF")
      (footprint "eagle-import:77317-104-28LF")
      (libsource (lib "eagle-import") (part "77317-104-28LF"))
    )
    (comp (ref "C86")
      (value "1u")
      (footprint "eagle-import:C0805")
      (libsource (lib "eagle-import") (part "C-EUC0805"))
    )
    (comp (ref "C87")
      (value "1u")
      (footprint "eagle-import:C0805")
      (libsource (lib "eagle-import") (part "C-EUC0805"))
    )
    (comp (ref "C88")
      (value "100n")
      (footprint "eagle-import:C0603")
      (libsource (lib "eagle-import") (part "C-EUC0603"))
    )
    (comp (ref "C89")
      (value "2n2")
      (footprint "eagle-import:C0805")
      (libsource (lib "eagle-import") (part "C-EUC0805"))
    )
    (comp (ref "C90")
      (value "2n2")
      (footprint "eagle-import:C0805")
      (libsource (lib "eagle-import") (part "C-EUC0805"))
    )
    (comp (ref "C91")
      (value "10u")
      (footprint "eagle-import:C1206")
      (libsource (lib "eagle-import") (part "C-EUC1206"))
    )
    (comp (ref "C92")
      (value "1u")
      (footprint "eagle-import:C0805")
      (libsource (lib "eagle-import") (part "C-EUC0805"))
    )
    (comp (ref "C93")
      (value "22u")
      (footprint "eagle-import:C1206")
      (libsource (lib "eagle-import") (part "C-EUC1206"))
    )
    (comp (ref "C94")
      (value "10u")
      (footprint "eagle-import:C1206")
      (libsource (lib "eagle-import") (part "C-EUC1206"))
    )
    (comp (ref "C95")
      (value "10u")
      (footprint "eagle-import:C1206")
      (libsource (lib "eagle-import") (part "C-EUC1206"))
    )
    (comp (ref "C96")
      (value "2n2")
      (footprint "eagle-import:C0805")
      (libsource (lib "eagle-import") (part "C-EUC0805"))
    )
    (comp (ref "C97")
      (value "2n2")
      (footprint "eagle-import:C0805")
      (libsource (lib "eagle-import") (part "C-EUC0805"))
    )
    (comp (ref "C98")
      (value "4n7/1kV")
      (footprint "eagle-import:C1812")
      (libsource (lib "eagle-import") (part "C-EUC1812"))
    )
    (comp (ref "FB5")
      (value "BLM18AG102SH1D")
      (footprint "eagle-import:BEAD0603")
      (libsource (lib "eagle-import") (part "FERRITE_BEAD0603"))
    )
    (comp (ref "FB6")
      (value "BLM18AG102SH1D")
      (footprint "eagle-import:BEAD0603")
      (libsource (lib "eagle-import") (part "FERRITE_BEAD0603"))
    )
    (comp (ref "FB7")
      (value "BLM18AG102SH1D")
      (footprint "eagle-import:BEAD0603")
      (libsource (lib "eagle-import") (part "FERRITE_BEAD0603"))
    )
    (comp (ref "FB8")
      (value "BLM18AG102SH1D")
      (footprint "eagle-import:BEAD0603")
      (libsource (lib "eagle-import") (part "FERRITE_BEAD0603"))
    )
    (comp (ref "FB9")
      (value "BLM18AG102SH1D")
      (footprint "eagle-import:BEAD0603")
      (libsource (lib "eagle-import") (part "FERRITE_BEAD0603"))
    )
    (comp (ref "IC21")
      (value "DG468DV-T1-E3")
      (footprint "eagle-import:DG6_TSOP6")
      (libsource (lib "eagle-import") (part "DG468DV-T1-E3"))
    )
    (comp (ref "IC22")
      (value "DG468DV-T1-E3")
      (footprint "eagle-import:DG6_TSOP6")
      (libsource (lib "eagle-import") (part "DG468DV-T1-E3"))
    )
    (comp (ref "IC23")
      (value "DG468DV-T1-E3")
      (footprint "eagle-import:DG6_TSOP6")
      (libsource (lib "eagle-import") (part "DG468DV-T1-E3"))
    )
    (comp (ref "IC24")
      (value "DG468DV-T1-E3")
      (footprint "eagle-import:DG6_TSOP6")
      (libsource (lib "eagle-import") (part "DG468DV-T1-E3"))
    )
    (comp (ref "IC25")
      (value "DG468DV-T1-E3")
      (footprint "eagle-import:DG6_TSOP6")
      (libsource (lib "eagle-import") (part "DG468DV-T1-E3"))
    )
    (comp (ref "IC26")
      (value "DG468DV-T1-E3")
      (footprint "eagle-import:DG6_TSOP6")
      (libsource (lib "eagle-import") (part "DG468DV-T1-E3"))
    )
    (comp (ref "IC27")
      (value "DG468DV-T1-E3")
      (footprint "eagle-import:DG6_TSOP6")
      (libsource (lib "eagle-import") (part "DG468DV-T1-E3"))
    )
    (comp (ref "IC28")
      (value "DG468DV-T1-E3")
      (footprint "eagle-import:DG6_TSOP6")
      (libsource (lib "eagle-import") (part "DG468DV-T1-E3"))
    )
    (comp (ref "IC29")
      (value "DG468DV-T1-E3")
      (footprint "eagle-import:DG6_TSOP6")
      (libsource (lib "eagle-import") (part "DG468DV-T1-E3"))
    )
    (comp (ref "IC30")
      (value "DG468DV-T1-E3")
      (footprint "eagle-import:DG6_TSOP6")
      (libsource (lib "eagle-import") (part "DG468DV-T1-E3"))
    )
    (comp (ref "IC31")
      (value "DG468DV-T1-E3")
      (footprint "eagle-import:DG6_TSOP6")
      (libsource (lib "eagle-import") (part "DG468DV-T1-E3"))
    )
    (comp (ref "IC32")
      (value "DG468DV-T1-E3")
      (footprint "eagle-import:DG6_TSOP6")
      (libsource (lib "eagle-import") (part "DG468DV-T1-E3"))
    )
    (comp (ref "IC33")
      (value "DG468DV-T1-E3")
      (footprint "eagle-import:DG6_TSOP6")
      (libsource (lib "eagle-import") (part "DG468DV-T1-E3"))
    )
    (comp (ref "IC34")
      (value "DG468DV-T1-E3")
      (footprint "eagle-import:DG6_TSOP6")
      (libsource (lib "eagle-import") (part "DG468DV-T1-E3"))
    )
    (comp (ref "IC35")
      (value "OPA376AIDBVR")
      (footprint "eagle-import:DBV5")
      (libsource (lib "eagle-import") (part "OPA376AIDBVR"))
    )
    (comp (ref "IC36")
      (value "ADS8674IDBT")
      (footprint "eagle-import:DBT38")
      (libsource (lib "eagle-import") (part "ADS8674IDBT"))
    )
    (comp (ref "JP3")
      (value "JP3-CUT")
      (footprint "eagle-import:JP3-CUT")
      (libsource (lib "eagle-import") (part "JP3-CUT"))
    )
    (comp (ref "JP4")
      (value "JP2-CUT-0805")
      (footprint "eagle-import:R_0805")
      (libsource (lib "eagle-import") (part "JP2-CUT-0805"))
    )
    (comp (ref "JP5")
      (value "JP2-CUT-0805")
      (footprint "eagle-import:R_0805")
      (libsource (lib "eagle-import") (part "JP2-CUT-0805"))
    )
    (comp (ref "Q6")
      (value "BSS169")
      (footprint "eagle-import:SOT103P240X110-3N")
      (libsource (lib "eagle-import") (part "BSS169"))
    )
    (comp (ref "Q7")
      (value "BSS169")
      (footprint "eagle-import:SOT103P240X110-3N")
      (libsource (lib "eagle-import") (part "BSS169"))
    )
    (comp (ref "Q8")
      (value "BSS169")
      (footprint "eagle-import:SOT103P240X110-3N")
      (libsource (lib "eagle-import") (part "BSS169"))
    )
    (comp (ref "Q9")
      (value "BSS169")
      (footprint "eagle-import:SOT103P240X110-3N")
      (libsource (lib "eagle-import") (part "BSS169"))
    )
    (comp (ref "Q10")
      (value "BSS169")
      (footprint "eagle-import:SOT103P240X110-3N")
      (libsource (lib "eagle-import") (part "BSS169"))
    )
    (comp (ref "Q11")
      (value "BSS169")
      (footprint "eagle-import:SOT103P240X110-3N")
      (libsource (lib "eagle-import") (part "BSS169"))
    )
    (comp (ref "Q12")
      (value "BSS169")
      (footprint "eagle-import:SOT103P240X110-3N")
      (libsource (lib "eagle-import") (part "BSS169"))
    )
    (comp (ref "Q13")
      (value "BSS169")
      (footprint "eagle-import:SOT103P240X110-3N")
      (libsource (lib "eagle-import") (part "BSS169"))
    )
    (comp (ref "R60")
      (value "10K")
      (footprint "eagle-import:R0805")
      (libsource (lib "eagle-import") (part "R-EU_R0805"))
    )
    (comp (ref "R61")
      (value "10K")
      (footprint "eagle-import:R0805")
      (libsource (lib "eagle-import") (part "R-EU_R0805"))
    )
    (comp (ref "R62")
      (value "47R")
      (footprint "eagle-import:R0805")
      (libsource (lib "eagle-import") (part "R-EU_R0805"))
    )
    (comp (ref "R63")
      (value "1K")
      (footprint "eagle-import:R0805")
      (libsource (lib "eagle-import") (part "R-EU_R0805"))
    )
    (comp (ref "R64")
      (value "N.C.")
      (footprint "eagle-import:R0805")
      (libsource (lib "eagle-import") (part "R-EU_R0805"))
    )
    (comp (ref "R65")
      (value "N.C.")
      (footprint "eagle-import:R0805")
      (libsource (lib "eagle-import") (part "R-EU_R0805"))
    )
    (comp (ref "R66")
      (value "N.C.")
      (footprint "eagle-import:R0805")
      (libsource (lib "eagle-import") (part "R-EU_R0805"))
    )
    (comp (ref "R67")
      (value "N.C.")
      (footprint "eagle-import:R0805")
      (libsource (lib "eagle-import") (part "R-EU_R0805"))
    )
    (comp (ref "R68")
      (value "100R")
      (footprint "eagle-import:R0805")
      (libsource (lib "eagle-import") (part "R-EU_R0805"))
    )
    (comp (ref "R69")
      (value "1K1")
      (footprint "eagle-import:R0805")
      (libsource (lib "eagle-import") (part "R-EU_R0805"))
    )
    (comp (ref "R70")
      (value "47R")
      (footprint "eagle-import:R0805")
      (libsource (lib "eagle-import") (part "R-EU_R0805"))
    )
    (comp (ref "R71")
      (value "1K")
      (footprint "eagle-import:R0805")
      (libsource (lib "eagle-import") (part "R-EU_R0805"))
    )
    (comp (ref "R72")
      (value "100R")
      (footprint "eagle-import:R0805")
      (libsource (lib "eagle-import") (part "R-EU_R0805"))
    )
    (comp (ref "R73")
      (value "1K1")
      (footprint "eagle-import:R0805")
      (libsource (lib "eagle-import") (part "R-EU_R0805"))
    )
    (comp (ref "R74")
      (value "47R")
      (footprint "eagle-import:R0805")
      (libsource (lib "eagle-import") (part "R-EU_R0805"))
    )
    (comp (ref "R75")
      (value "1K")
      (footprint "eagle-import:R0805")
      (libsource (lib "eagle-import") (part "R-EU_R0805"))
    )
    (comp (ref "R76")
      (value "100R")
      (footprint "eagle-import:R0805")
      (libsource (lib "eagle-import") (part "R-EU_R0805"))
    )
    (comp (ref "R77")
      (value "1K1")
      (footprint "eagle-import:R0805")
      (libsource (lib "eagle-import") (part "R-EU_R0805"))
    )
    (comp (ref "R78")
      (value "47R")
      (footprint "eagle-import:R0805")
      (libsource (lib "eagle-import") (part "R-EU_R0805"))
    )
    (comp (ref "R79")
      (value "1K")
      (footprint "eagle-import:R0805")
      (libsource (lib "eagle-import") (part "R-EU_R0805"))
    )
    (comp (ref "R80")
      (value "560K")
      (footprint "eagle-import:R1206")
      (libsource (lib "eagle-import") (part "R-EU_R1206"))
    )
    (comp (ref "R81")
      (value "560K")
      (footprint "eagle-import:R1206")
      (libsource (lib "eagle-import") (part "R-EU_R1206"))
    )
    (comp (ref "R82")
      (value "100R")
      (footprint "eagle-import:R0805")
      (libsource (lib "eagle-import") (part "R-EU_R0805"))
    )
    (comp (ref "R83")
      (value "1K1")
      (footprint "eagle-import:R0805")
      (libsource (lib "eagle-import") (part "R-EU_R0805"))
    )
    (comp (ref "SH5")
      (value "SHORTNOHOLE")
      (footprint "eagle-import:SHORT_NOHOLE")
      (libsource (lib "eagle-import") (part "SHORTNOHOLE"))
    )
    (comp (ref "SH6")
      (value "SHORTNOHOLE")
      (footprint "eagle-import:SHORT_NOHOLE")
      (libsource (lib "eagle-import") (part "SHORTNOHOLE"))
    )
    (comp (ref "SH7")
      (value "SHORTNOHOLE")
      (footprint "eagle-import:SHORT_NOHOLE")
      (libsource (lib "eagle-import") (part "SHORTNOHOLE"))
    )
    (comp (ref "SH8")
      (value "SHORTNOHOLE")
      (footprint "eagle-import:SHORT_NOHOLE")
      (libsource (lib "eagle-import") (part "SHORTNOHOLE"))
    )
    (comp (ref "TVS5")
      (value "PESD12VL1BA,115")
      (footprint "eagle-import:SOD323-BIDIR")
      (libsource (lib "eagle-import") (part "PESDXL1BA"))
    )
    (comp (ref "TVS6")
      (value "PESD12VL1BA,115")
      (footprint "eagle-import:SOD323-BIDIR")
      (libsource (lib "eagle-import") (part "PESDXL1BA"))
    )
    (comp (ref "TVS7")
      (value "PESD12VL1BA,115")
      (footprint "eagle-import:SOD323-BIDIR")
      (libsource (lib "eagle-import") (part "PESDXL1BA"))
    )
    (comp (ref "TVS8")
      (value "PESD12VL1BA,115")
      (footprint "eagle-import:SOD323-BIDIR")
      (libsource (lib "eagle-import") (part "PESDXL1BA"))
    )
    (comp (ref "C61")
      (value "100n")
      (footprint "eagle-import:C0603")
      (libsource (lib "eagle-import") (part "C-EUC0603"))
    )
    (comp (ref "C62")
      (value "100n")
      (footprint "eagle-import:C0603")
      (libsource (lib "eagle-import") (part "C-EUC0603"))
    )
    (comp (ref "C63")
      (value "150n")
      (footprint "eagle-import:C0805")
      (libsource (lib "eagle-import") (part "C-EUC0805"))
    )
    (comp (ref "C64")
      (value "100n")
      (footprint "eagle-import:C0603")
      (libsource (lib "eagle-import") (part "C-EUC0603"))
    )
    (comp (ref "C65")
      (value "100n")
      (footprint "eagle-import:C0603")
      (libsource (lib "eagle-import") (part "C-EUC0603"))
    )
    (comp (ref "C66")
      (value "4u7")
      (footprint "eagle-import:C0805")
      (libsource (lib "eagle-import") (part "C-EUC0805"))
    )
    (comp (ref "C67")
      (value "100n")
      (footprint "eagle-import:C0603")
      (libsource (lib "eagle-import") (part "C-EUC0603"))
    )
    (comp (ref "C68")
      (value "100n")
      (footprint "eagle-import:C0603")
      (libsource (lib "eagle-import") (part "C-EUC0603"))
    )
    (comp (ref "C69")
      (value "100n")
      (footprint "eagle-import:C0603")
      (libsource (lib "eagle-import") (part "C-EUC0603"))
    )
    (comp (ref "C70")
      (value "100n")
      (footprint "eagle-import:C0603")
      (libsource (lib "eagle-import") (part "C-EUC0603"))
    )
    (comp (ref "C71")
      (value "100n")
      (footprint "eagle-import:C0603")
      (libsource (lib "eagle-import") (part "C-EUC0603"))
    )
    (comp (ref "C72")
      (value "100n")
      (footprint "eagle-import:C0603")
      (libsource (lib "eagle-import") (part "C-EUC0603"))
    )
    (comp (ref "C73")
      (value "100n")
      (footprint "eagle-import:C0603")
      (libsource (lib "eagle-import") (part "C-EUC0603"))
    )
    (comp (ref "D3")
      (value "BAT54SFILM")
      (footprint "eagle-import:SOT23")
      (libsource (lib "eagle-import") (part "BAT54S"))
    )
    (comp (ref "D4")
      (value "BAT54SFILM")
      (footprint "eagle-import:SOT23")
      (libsource (lib "eagle-import") (part "BAT54S"))
    )
    (comp (ref "D5")
      (value "BAT54SFILM")
      (footprint "eagle-import:SOT23")
      (libsource (lib "eagle-import") (part "BAT54S"))
    )
    (comp (ref "D6")
      (value "BAT54SFILM")
      (footprint "eagle-import:SOT23")
      (libsource (lib "eagle-import") (part "BAT54S"))
    )
    (comp (ref "FB4")
      (value "BLM18AG102SH1D")
      (footprint "eagle-import:BEAD0603")
      (libsource (lib "eagle-import") (part "FERRITE_BEAD0603"))
    )
    (comp (ref "IC12")
      (value "OPA376AIDBVR")
      (footprint "eagle-import:DBV5")
      (libsource (lib "eagle-import") (part "OPA376AIDBVR"))
    )
    (comp (ref "IC13")
      (value "DAC7563TDGSR")
      (footprint "eagle-import:DGS10")
      (libsource (lib "eagle-import") (part "DAC7563TDGSR"))
    )
    (comp (ref "IC14")
      (value "OPA2196IDR")
      (footprint "eagle-import:SOIC127P600X173-8N")
      (libsource (lib "eagle-import") (part "TL072SOIC8"))
    )
    (comp (ref "IC15")
      (value "BTS3408G")
      (footprint "eagle-import:SOIC127P600X173-8N")
      (libsource (lib "eagle-import") (part "BTS3408G"))
    )
    (comp (ref "IC16")
      (value "BTS3408G")
      (footprint "eagle-import:SOIC127P600X173-8N")
      (libsource (lib "eagle-import") (part "BTS3408G"))
    )
    (comp (ref "IC17")
      (value "BTS3408G")
      (footprint "eagle-import:SOIC127P600X173-8N")
      (libsource (lib "eagle-import") (part "BTS3408G"))
    )
    (comp (ref "IC18")
      (value "BTS3408G")
      (footprint "eagle-import:SOIC127P600X173-8N")
      (libsource (lib "eagle-import") (part "BTS3408G"))
    )
    (comp (ref "IC19")
      (value "74HC126PW,118")
      (footprint "eagle-import:PW14")
      (libsource (lib "eagle-import") (part "74HC126PW,118"))
    )
    (comp (ref "R16")
      (value "9K09 0.1%")
      (footprint "eagle-import:R0805")
      (libsource (lib "eagle-import") (part "R-EU_R0805"))
    )
    (comp (ref "R17")
      (value "75K 0.1%")
      (footprint "eagle-import:R0805")
      (libsource (lib "eagle-import") (part "R-EU_R0805"))
    )
    (comp (ref "R18")
      (value "9K09 0.1%")
      (footprint "eagle-import:R0805")
      (libsource (lib "eagle-import") (part "R-EU_R0805"))
    )
    (comp (ref "R19")
      (value "180R")
      (footprint "eagle-import:R0805")
      (libsource (lib "eagle-import") (part "R-EU_R0805"))
    )
    (comp (ref "R20")
      (value "47R")
      (footprint "eagle-import:R0805")
      (libsource (lib "eagle-import") (part "R-EU_R0805"))
    )
    (comp (ref "R21")
      (value "9K09 0.1%")
      (footprint "eagle-import:R0805")
      (libsource (lib "eagle-import") (part "R-EU_R0805"))
    )
    (comp (ref "R22")
      (value "9K09 0.1%")
      (footprint "eagle-import:R0805")
      (libsource (lib "eagle-import") (part "R-EU_R0805"))
    )
    (comp (ref "R23")
      (value "75K 0.1%")
      (footprint "eagle-import:R0805")
      (libsource (lib "eagle-import") (part "R-EU_R0805"))
    )
    (comp (ref "R24")
      (value "9K09 0.1%")
      (footprint "eagle-import:R0805")
      (libsource (lib "eagle-import") (part "R-EU_R0805"))
    )
    (comp (ref "R25")
      (value "75K 0.1%")
      (footprint "eagle-import:R0805")
      (libsource (lib "eagle-import") (part "R-EU_R0805"))
    )
    (comp (ref "R26")
      (value "180R")
      (footprint "eagle-import:R0805")
      (libsource (lib "eagle-import") (part "R-EU_R0805"))
    )
    (comp (ref "R27")
      (value "47R")
      (footprint "eagle-import:R0805")
      (libsource (lib "eagle-import") (part "R-EU_R0805"))
    )
    (comp (ref "R28")
      (value "9K09 0.1%")
      (footprint "eagle-import:R0805")
      (libsource (lib "eagle-import") (part "R-EU_R0805"))
    )
    (comp (ref "R29")
      (value "75K 0.1%")
      (footprint "eagle-import:R0805")
      (libsource (lib "eagle-import") (part "R-EU_R0805"))
    )
    (comp (ref "R30")
      (value "10K")
      (footprint "eagle-import:R0805")
      (libsource (lib "eagle-import") (part "R-EU_R0805"))
    )
    (comp (ref "R31")
      (value "100R")
      (footprint "eagle-import:R0805")
      (libsource (lib "eagle-import") (part "R-EU_R0805"))
    )
    (comp (ref "R32")
      (value "100R")
      (footprint "eagle-import:R0805")
      (libsource (lib "eagle-import") (part "R-EU_R0805"))
    )
    (comp (ref "SH4")
      (value "SHORTNOHOLE")
      (footprint "eagle-import:SHORT_NOHOLE")
      (libsource (lib "eagle-import") (part "SHORTNOHOLE"))
    )
    (comp (ref "TVS3")
      (value "PESD12VL1BA,115")
      (footprint "eagle-import:SOD323-BIDIR")
      (libsource (lib "eagle-import") (part "PESDXL1BA"))
    )
    (comp (ref "TVS4")
      (value "PESD12VL1BA,115")
      (footprint "eagle-import:SOD323-BIDIR")
      (libsource (lib "eagle-import") (part "PESDXL1BA"))
    )
  )
  (nets
    (net (code "1") (name "+3V3") (class "Default")
      (node (ref "C1") (pin "2") (pinfunction "2_2") (pintype "passive"))
      (node (ref "C2") (pin "1") (pinfunction "1_1") (pintype "passive"))
      (node (ref "C4") (pin "1") (pinfunction "1_1") (pintype "passive"))
      (node (ref "IC1") (pin "8") (pinfunction "VCC_8") (pintype "power_in"))
      (node (ref "IC2") (pin "1") (pinfunction "VDD1_1") (pintype "passive"))
      (node (ref "IC2") (pin "7") (pinfunction "EN1_7") (pintype "input"))
      (node (ref "IC3") (pin "1") (pinfunction "VDD1_1") (pintype "passive"))
      (node (ref "IC3") (pin "7") (pinfunction "EN1_7") (pintype "input"))
      (node (ref "RN3") (pin "6") (pinfunction "2_6") (pintype "passive"))
      (node (ref "RN3") (pin "7") (pinfunction "2_7") (pintype "passive"))
      (node (ref "RN3") (pin "8") (pinfunction "2_8") (pintype "passive"))
      (node (ref "X1") (pin "1") (pinfunction "1_1") (pintype "passive"))
    )
    (net (code "2") (name "+3V3_ISO") (class "Default")
      (node (ref "C14") (pin "1") (pinfunction "1_1") (pintype "passive"))
      (node (ref "C21") (pin "1") (pinfunction "1_1") (pintype "passive"))
      (node (ref "C3") (pin "2") (pinfunction "2_2") (pintype "passive"))
      (node (ref "C43") (pin "1") (pinfunction "1_1") (pintype "passive"))
      (node (ref "C5") (pin "2") (pinfunction "2_2") (pintype "passive"))
      (node (ref "C52") (pin "1") (pinfunction "1_1") (pintype "passive"))
      (node (ref "C73") (pin "2") (pinfunction "2_2") (pintype "passive"))
      (node (ref "C95") (pin "2") (pinfunction "2_2") (pintype "passive"))
      (node (ref "FB4") (pin "P$2") (pinfunction "2_P$2") (pintype "passive"))
      (node (ref "IC10") (pin "2") (pinfunction "DVDD_2") (pintype "power_in"))
      (node (ref "IC11") (pin "2") (pinfunction "DVDD_2") (pintype "power_in"))
      (node (ref "IC19") (pin "14") (pinfunction "V+_14") (pintype "power_in"))
      (node (ref "IC2") (pin "10") (pinfunction "EN2_10") (pintype "input"))
      (node (ref "IC2") (pin "16") (pinfunction "VDD2_16") (pintype "passive"))
      (node (ref "IC3") (pin "10") (pinfunction "EN2_10") (pintype "input"))
      (node (ref "IC3") (pin "16") (pinfunction "VDD2_16") (pintype "passive"))
      (node (ref "IC36") (pin "34") (pinfunction "DVDD_34") (pintype "power_in"))
      (node (ref "IC6") (pin "5") (pinfunction "OUT_5") (pintype "passive"))
      (node (ref "J2") (pin "4") (pinfunction "VDD_4") (pintype "power_in"))
      (node (ref "R1") (pin "1") (pinfunction "1_1") (pintype "passive"))
      (node (ref "R12") (pin "1") (pinfunction "1_1") (pintype "passive"))
      (node (ref "R2") (pin "1") (pinfunction "1_1") (pintype "passive"))
      (node (ref "R3") (pin "1") (pinfunction "1_1") (pintype "passive"))
      (node (ref "R30") (pin "1") (pinfunction "1_1") (pintype "passive"))
      (node (ref "R33") (pin "1") (pinfunction "1_1") (pintype "passive"))
      (node (ref "R4") (pin "1") (pinfunction "1_1") (pintype "passive"))
      (node (ref "R5") (pin "1") (pinfunction "1_1") (pintype "passive"))
      (node (ref "SH1") (pin "2") (pinfunction "GND_B_2") (pintype "bidirectional"))
    )
    (net (code "3") (name "+5V_ISO") (class "Default")
      (node (ref "C18") (pin "2") (pinfunction "2_2") (pintype "passive"))
      (node (ref "D5") (pin "2") (pinfunction "C2_2") (pintype "passive"))
      (node (ref "D6") (pin "2") (pinfunction "C2_2") (pintype "passive"))
      (node (ref "FB8") (pin "P$1") (pinfunction "1_P$1") (pintype "passive"))
      (node (ref "IC5") (pin "5") (pinfunction "OUT_5") (pintype "passive"))
      (node (ref "IC6") (pin "1") (pinfunction "IN_1") (pintype "input"))
      (node (ref "IC6") (pin "3") (pinfunction "ON/~{OFF}_3") (pintype "input"))
    )
    (net (code "4") (name "+12V") (class "Default")
      (node (ref "C7") (pin "2") (pinfunction "2_2") (pintype "passive"))
      (node (ref "L1") (pin "4") (pinfunction "4_4") (pintype "passive"))
      (node (ref "X1") (pin "21") (pinfunction "1_21") (pintype "passive"))
      (node (ref "X1") (pin "22") (pinfunction "1_22") (pintype "passive"))
    )
    (net (code "5") (name "+12V_ISO") (class "Default")
      (node (ref "C10") (pin "1") (pinfunction "1_1") (pintype "passive"))
      (node (ref "C16") (pin "2") (pinfunction "2_2") (pintype "passive"))
      (node (ref "C47") (pin "1") (pinfunction "1_1") (pintype "passive"))
      (node (ref "C49") (pin "2") (pinfunction "2_2") (pintype "passive"))
      (node (ref "C55") (pin "1") (pinfunction "1_1") (pintype "passive"))
      (node (ref "C57") (pin "1") (pinfunction "1_1") (pintype "passive"))
      (node (ref "C60") (pin "2") (pinfunction "2_2") (pintype "passive"))
      (node (ref "C61") (pin "1") (pinfunction "1_1") (pintype "passive"))
      (node (ref "C69") (pin "2") (pinfunction "2_2") (pintype "passive"))
      (node (ref "C70") (pin "2") (pinfunction "2_2") (pintype "passive"))
      (node (ref "C71") (pin "2") (pinfunction "2_2") (pintype "passive"))
      (node (ref "C72") (pin "2") (pinfunction "2_2") (pintype "passive"))
      (node (ref "D1") (pin "2") (pinfunction "C2_2") (pintype "passive"))
      (node (ref "D2") (pin "2") (pinfunction "C2_2") (pintype "passive"))
      (node (ref "D3") (pin "2") (pinfunction "C2_2") (pintype "passive"))
      (node (ref "D4") (pin "2") (pinfunction "C2_2") (pintype "passive"))
      (node (ref "IC10") (pin "24") (pinfunction "AVDD_24") (pintype "power_in"))
      (node (ref "IC11") (pin "24") (pinfunction "AVDD_24") (pintype "power_in"))
      (node (ref "IC14") (pin "8") (pinfunction "V+_8") (pintype "power_in"))
      (node (ref "IC15") (pin "8") (pinfunction "VSS_8") (pintype "passive"))
      (node (ref "IC16") (pin "8") (pinfunction "VSS_8") (pintype "passive"))
      (node (ref "IC17") (pin "8") (pinfunction "VSS_8") (pintype "passive"))
      (node (ref "IC18") (pin "8") (pinfunction "VSS_8") (pintype "passive"))
      (node (ref "IC4") (pin "1") (pinfunction "VO_1") (pintype "passive"))
      (node (ref "IC5") (pin "1") (pinfunction "IN_1") (pintype "input"))
      (node (ref "IC5") (pin "3") (pinfunction "ON/~{OFF}_3") (pintype "input"))
      (node (ref "IC9") (pin "8") (pinfunction "V+_8") (pintype "power_in"))
      (node (ref "JP1") (pin "2") (pinfunction "2_2") (pintype "passive"))
    )
    (net (code "6") (name "+15V_ISO") (class "Default")
      (node (ref "C11") (pin "2") (pinfunction "2_2") (pintype "passive"))
      (node (ref "C86") (pin "1") (pinfunction "1_1") (pintype "passive"))
      (node (ref "IC21") (pin "5") (pinfunction "V+_5") (pintype "passive"))
      (node (ref "IC22") (pin "5") (pinfunction "V+_5") (pintype "passive"))
      (node (ref "IC23") (pin "5") (pinfunction "V+_5") (pintype "passive"))
      (node (ref "IC24") (pin "5") (pinfunction "V+_5") (pintype "passive"))
      (node (ref "IC25") (pin "5") (pinfunction "V+_5") (pintype "passive"))
      (node (ref "IC26") (pin "5") (pinfunction "V+_5") (pintype "passive"))
      (node (ref "IC27") (pin "5") (pinfunction "V+_5") (pintype "passive"))
      (node (ref "IC28") (pin "5") (pinfunction "V+_5") (pintype "passive"))
      (node (ref "IC29") (pin "5") (pinfunction "V+_5") (pintype "passive"))
      (node (ref "IC30") (pin "5") (pinfunction "V+_5") (pintype "passive"))
      (node (ref "IC31") (pin "5") (pinfunction "V+_5") (pintype "passive"))
      (node (ref "IC32") (pin "5") (pinfunction "V+_5") (pintype "passive"))
      (node (ref "IC33") (pin "5") (pinfunction "V+_5") (pintype "passive"))
      (node (ref "IC34") (pin "5") (pinfunction "V+_5") (pintype "passive"))
      (node (ref "IC4") (pin "8") (pinfunction "VI_8") (pintype "input"))
      (node (ref "JP1") (pin "1") (pinfunction "1_1") (pintype "passive"))
      (node (ref "L2") (pin "2") (pinfunction "2_2") (pintype "passive"))
    )
    (net (code "7") (name "-12V_ISO") (class "Default")
      (node (ref "C13") (pin "2") (pinfunction "2_2") (pintype "passive"))
      (node (ref "C46") (pin "1") (pinfunction "1_1") (pintype "passive"))
      (node (ref "C48") (pin "2") (pinfunction "2_2") (pintype "passive"))
      (node (ref "C56") (pin "1") (pinfunction "1_1") (pintype "passive"))
      (node (ref "C58") (pin "1") (pinfunction "1_1") (pintype "passive"))
      (node (ref "C59") (pin "2") (pinfunction "2_2") (pintype "passive"))
      (node (ref "C64") (pin "1") (pinfunction "1_1") (pintype "passive"))
      (node (ref "D1") (pin "1") (pinfunction "A1_1") (pintype "passive"))
      (node (ref "D2") (pin "1") (pinfunction "A1_1") (pintype "passive"))
      (node (ref "D3") (pin "1") (pinfunction "A1_1") (pintype "passive"))
      (node (ref "D4") (pin "1") (pinfunction "A1_1") (pintype "passive"))
      (node (ref "IC10") (pin "1") (pinfunction "AVSS_1") (pintype "power_in"))
      (node (ref "IC11") (pin "1") (pinfunction "AVSS_1") (pintype "power_in"))
      (node (ref "IC14") (pin "4") (pinfunction "V-_4") (pintype "power_in"))
      (node (ref "IC7") (pin "1") (pinfunction "OUT_1") (pintype "passive"))
      (node (ref "IC9") (pin "4") (pinfunction "V-_4") (pintype "power_in"))
      (node (ref "JP2") (pin "2") (pinfunction "2_2") (pintype "passive"))
      (node (ref "R64") (pin "1") (pinfunction "1_1") (pintype "passive"))
      (node (ref "R65") (pin "1") (pinfunction "1_1") (pintype "passive"))
      (node (ref "R66") (pin "1") (pinfunction "1_1") (pintype "passive"))
      (node (ref "R67") (pin "1") (pinfunction "1_1") (pintype "passive"))
    )
    (net (code "8") (name "-15V_ISO") (class "Default")
      (node (ref "C15") (pin "1") (pinfunction "1_1") (pintype "passive"))
      (node (ref "C87") (pin "1") (pinfunction "1_1") (pintype "passive"))
      (node (ref "IC21") (pin "2") (pinfunction "V-_2") (pintype "passive"))
      (node (ref "IC22") (pin "2") (pinfunction "V-_2") (pintype "passive"))
      (node (ref "IC23") (pin "2") (pinfunction "V-_2") (pintype "passive"))
      (node (ref "IC24") (pin "2") (pinfunction "V-_2") (pintype "passive"))
      (node (ref "IC25") (pin "2") (pinfunction "V-_2") (pintype "passive"))
      (node (ref "IC26") (pin "2") (pinfunction "V-_2") (pintype "passive"))
      (node (ref "IC27") (pin "2") (pinfunction "V-_2") (pintype "passive"))
      (node (ref "IC28") (pin "2") (pinfunction "V-_2") (pintype "passive"))
      (node (ref "IC29") (pin "2") (pinfunction "V-_2") (pintype "passive"))
      (node (ref "IC30") (pin "2") (pinfunction "V-_2") (pintype "passive"))
      (node (ref "IC31") (pin "2") (pinfunction "V-_2") (pintype "passive"))
      (node (ref "IC32") (pin "2") (pinfunction "V-_2") (pintype "passive"))
      (node (ref "IC33") (pin "2") (pinfunction "V-_2") (pintype "passive"))
      (node (ref "IC34") (pin "2") (pinfunction "V-_2") (pintype "passive"))
      (node (ref "IC7") (pin "2") (pinfunction "IN_2") (pintype "input"))
      (node (ref "IC7") (pin "3") (pinfunction "IN_3") (pintype "input"))
      (node (ref "IC7") (pin "6") (pinfunction "IN_6") (pintype "input"))
      (node (ref "IC7") (pin "7") (pinfunction "IN_7") (pintype "input"))
      (node (ref "JP2") (pin "1") (pinfunction "1_1") (pintype "passive"))
      (node (ref "L3") (pin "3") (pinfunction "3_3") (pintype "passive"))
    )
    (net (code "19") (name "1V25_REF") (class "Default")
      (node (ref "IC12") (pin "1") (pinfunction "OUT_1") (pintype "output"))
      (node (ref "IC12") (pin "4") (pinfunction "-IN_4") (pintype "input"))
      (node (ref "JP3") (pin "NO") (pinfunction "NO_NO") (pintype "passive"))
      (node (ref "R16") (pin "2") (pinfunction "2_2") (pintype "passive"))
      (node (ref "R24") (pin "2") (pinfunction "2_2") (pintype "passive"))
    )
    (net (code "20") (name "ADC_AVDD") (class "Default")
      (node (ref "C88") (pin "1") (pinfunction "1_1") (pintype "passive"))
      (node (ref "C94") (pin "2") (pinfunction "2_2") (pintype "passive"))
      (node (ref "FB8") (pin "P$2") (pinfunction "2_P$2") (pintype "passive"))
      (node (ref "IC35") (pin "5") (pinfunction "V+_5") (pintype "power_in"))
      (node (ref "IC36") (pin "30") (pinfunction "AVDD_30") (pintype "power_in"))
      (node (ref "IC36") (pin "9") (pinfunction "AVDD_9") (pintype "power_in"))
    )
    (net (code "21") (name "ADC_IRQ") (class "Default")
      (node (ref "IC36") (pin "35") (pinfunction "ALARM_35") (pintype "output"))
      (node (ref "IC8") (pin "2") (pinfunction "PE3_2") (pintype "bidirectional"))
    )
    (net (code "22") (name "ADC_MISO") (class "Default")
      (node (ref "IC36") (pin "36") (pinfunction "SDO_36") (pintype "output"))
      (node (ref "RN4") (pin "3") (pinfunction "1_3") (pintype "passive"))
    )
    (net (code "23") (name "ADC_MOSI") (class "Default")
      (node (ref "IC36") (pin "1") (pinfunction "SDI_1") (pintype "input"))
      (node (ref "RN4") (pin "4") (pinfunction "1_4") (pintype "passive"))
    )
    (net (code "24") (name "ADC_SCLK") (class "Default")
      (node (ref "IC36") (pin "37") (pinfunction "SCLK_37") (pintype "input"))
      (node (ref "RN4") (pin "1") (pinfunction "1_1") (pintype "passive"))
    )
    (net (code "25") (name "ADC_VREF") (class "Default")
      (node (ref "C91") (pin "2") (pinfunction "2_2") (pintype "passive"))
      (node (ref "IC35") (pin "3") (pinfunction "+IN_3") (pintype "input"))
      (node (ref "IC36") (pin "5") (pinfunction "REFIO_5") (pintype "bidirectional"))
    )
    (net (code "26") (name "AIN_0GND") (class "Default")
      (node (ref "C89") (pin "1") (pinfunction "1_1") (pintype "passive"))
      (node (ref "IC36") (pin "17") (pinfunction "AIN_0GND_17") (pintype "input"))
      (node (ref "R69") (pin "2") (pinfunction "2_2") (pintype "passive"))
    )
    (net (code "27") (name "AIN_0P") (class "Default")
      (node (ref "C89") (pin "2") (pinfunction "2_2") (pintype "passive"))
      (node (ref "IC36") (pin "16") (pinfunction "AIN_0P_16") (pintype "input"))
      (node (ref "R63") (pin "2") (pinfunction "2_2") (pintype "passive"))
      (node (ref "R66") (pin "2") (pinfunction "2_2") (pintype "passive"))
    )
    (net (code "28") (name "AIN_1GND") (class "Default")
      (node (ref "C90") (pin "1") (pinfunction "1_1") (pintype "passive"))
      (node (ref "IC36") (pin "19") (pinfunction "AIN_1GND_19") (pintype "input"))
      (node (ref "R73") (pin "2") (pinfunction "2_2") (pintype "passive"))
    )
    (net (code "29") (name "AIN_1P") (class "Default")
      (node (ref "C90") (pin "2") (pinfunction "2_2") (pintype "passive"))
      (node (ref "IC36") (pin "18") (pinfunction "AIN_1P_18") (pintype "input"))
      (node (ref "R64") (pin "2") (pinfunction "2_2") (pintype "passive"))
      (node (ref "R71") (pin "2") (pinfunction "2_2") (pintype "passive"))
    )
    (net (code "30") (name "AIN_2GND") (class "Default")
      (node (ref "C96") (pin "1") (pinfunction "1_1") (pintype "passive"))
      (node (ref "IC36") (pin "20") (pinfunction "AIN_2GND_20") (pintype "input"))
      (node (ref "R77") (pin "2") (pinfunction "2_2") (pintype "passive"))
    )
    (net (code "31") (name "AIN_2P") (class "Default")
      (node (ref "C96") (pin "2") (pinfunction "2_2") (pintype "passive"))
      (node (ref "IC36") (pin "21") (pinfunction "AIN_2P_21") (pintype "input"))
      (node (ref "R67") (pin "2") (pinfunction "2_2") (pintype "passive"))
      (node (ref "R75") (pin "2") (pinfunction "2_2") (pintype "passive"))
    )
    (net (code "32") (name "AIN_3GND") (class "Default")
      (node (ref "C97") (pin "1") (pinfunction "1_1") (pintype "passive"))
      (node (ref "IC36") (pin "22") (pinfunction "AIN_3GND_22") (pintype "input"))
      (node (ref "R83") (pin "2") (pinfunction "2_2") (pintype "passive"))
    )
    (net (code "33") (name "AIN_3P") (class "Default")
      (node (ref "C97") (pin "2") (pinfunction "2_2") (pintype "passive"))
      (node (ref "IC36") (pin "23") (pinfunction "AIN_3P_23") (pintype "input"))
      (node (ref "R65") (pin "2") (pinfunction "2_2") (pintype "passive"))
      (node (ref "R79") (pin "2") (pinfunction "2_2") (pintype "passive"))
    )
    (net (code "34") (name "BOOT0") (class "Default")
      (node (ref "IC3") (pin "13") (pinfunction "B2_13") (pintype "output"))
      (node (ref "IC8") (pin "138") (pinfunction "BOOT0_138") (pintype "input"))
      (node (ref "R7") (pin "2") (pinfunction "2_2") (pintype "passive"))
    )
    (net (code "35") (name "CLAMP") (class "Default")
      (node (ref "C74") (pin "1") (pinfunction "1_1") (pintype "passive"))
      (node (ref "C75") (pin "1") (pinfunction "1_1") (pintype "passive"))
      (node (ref "D10") (pin "2") (pinfunction "C2_2") (pintype "passive"))
      (node (ref "D11") (pin "2") (pinfunction "C2_2") (pintype "passive"))
      (node (ref "D12") (pin "2") (pinfunction "C2_2") (pintype "passive"))
      (node (ref "D13") (pin "2") (pinfunction "C2_2") (pintype "passive"))
      (node (ref "D14") (pin "2") (pinfunction "C2_2") (pintype "passive"))
      (node (ref "D7") (pin "2") (pinfunction "C2_2") (pintype "passive"))
      (node (ref "D8") (pin "2") (pinfunction "C2_2") (pintype "passive"))
      (node (ref "D9") (pin "2") (pinfunction "C2_2") (pintype "passive"))
      (node (ref "IC20") (pin "1") (pinfunction "C_1") (pintype "passive"))
      (node (ref "R33") (pin "2") (pinfunction "2_2") (pintype "passive"))
      (node (ref "R34") (pin "1") (pinfunction "1_1") (pintype "passive"))
    )
    (net (code "36") (name "CURR_SW0") (class "Default")
      (node (ref "IC22") (pin "3") (pinfunction "IN_3") (pintype "input"))
      (node (ref "IC27") (pin "3") (pinfunction "IN_3") (pintype "input"))
      (node (ref "IC8") (pin "117") (pinfunction "PD3_117") (pintype "bidirectional"))
    )
    (net (code "37") (name "CURR_SW1") (class "Default")
      (node (ref "IC23") (pin "3") (pinfunction "IN_3") (pintype "input"))
      (node (ref "IC28") (pin "3") (pinfunction "IN_3") (pintype "input"))
      (node (ref "IC8") (pin "118") (pinfunction "PD4_118") (pintype "bidirectional"))
    )
    (net (code "38") (name "CURR_SW2") (class "Default")
      (node (ref "IC24") (pin "3") (pinfunction "IN_3") (pintype "input"))
      (node (ref "IC29") (pin "3") (pinfunction "IN_3") (pintype "input"))
      (node (ref "IC8") (pin "119") (pinfunction "PD5_119") (pintype "bidirectional"))
    )
    (net (code "39") (name "CURR_SW3") (class "Default")
      (node (ref "IC25") (pin "3") (pinfunction "IN_3") (pintype "input"))
      (node (ref "IC30") (pin "3") (pinfunction "IN_3") (pintype "input"))
      (node (ref "IC8") (pin "122") (pinfunction "PD6_122") (pintype "bidirectional"))
    )
    (net (code "40") (name "DAC_CLR#1") (class "Default")
      (node (ref "IC10") (pin "6") (pinfunction "CLR_6") (pintype "input"))
      (node (ref "IC8") (pin "21") (pinfunction "PF9_21") (pintype "bidirectional"))
    )
    (net (code "41") (name "DAC_CLR#2") (class "Default")
      (node (ref "IC11") (pin "6") (pinfunction "CLR_6") (pintype "input"))
      (node (ref "IC8") (pin "19") (pinfunction "PF7_19") (pintype "bidirectional"))
    )
    (net (code "42") (name "DAC_CLR-SEL#1") (class "Default")
      (node (ref "IC10") (pin "5") (pinfunction "CLR-SEL_5") (pintype "input"))
      (node (ref "IC8") (pin "22") (pinfunction "PF10_22") (pintype "bidirectional"))
    )
    (net (code "43") (name "DAC_CLR-SEL#2") (class "Default")
      (node (ref "IC11") (pin "5") (pinfunction "CLR-SEL_5") (pintype "input"))
      (node (ref "IC8") (pin "20") (pinfunction "PF8_20") (pintype "bidirectional"))
    )
    (net (code "44") (name "DAC_CS#1") (class "Default")
      (node (ref "IC10") (pin "7") (pinfunction "LATCH_7") (pintype "input"))
      (node (ref "IC8") (pin "27") (pinfunction "PC1_27") (pintype "bidirectional"))
    )
    (net (code "45") (name "DAC_CS#2") (class "Default")
      (node (ref "IC11") (pin "7") (pinfunction "LATCH_7") (pintype "input"))
      (node (ref "IC8") (pin "18") (pinfunction "PF6_18") (pintype "bidirectional"))
    )
    (net (code "46") (name "DAC_MISO") (class "Default")
      (node (ref "IC10") (pin "10") (pinfunction "SDO_10") (pintype "output"))
      (node (ref "IC11") (pin "10") (pinfunction "SDO_10") (pintype "output"))
      (node (ref "RN5") (pin "3") (pinfunction "1_3") (pintype "passive"))
    )
    (net (code "47") (name "DAC_MOSI") (class "Default")
      (node (ref "IC10") (pin "9") (pinfunction "DIN_9") (pintype "input"))
      (node (ref "IC11") (pin "9") (pinfunction "DIN_9") (pintype "input"))
      (node (ref "IC13") (pin "8") (pinfunction "DIN_8") (pintype "input"))
      (node (ref "RN5") (pin "4") (pinfunction "1_4") (pintype "passive"))
    )
    (net (code "48") (name "DAC_SCLK") (class "Default")
      (node (ref "IC10") (pin "8") (pinfunction "SCLK_8") (pintype "input"))
      (node (ref "IC11") (pin "8") (pinfunction "SCLK_8") (pintype "input"))
      (node (ref "IC13") (pin "7") (pinfunction "SCLK_7") (pintype "input"))
      (node (ref "RN5") (pin "2") (pinfunction "1_2") (pintype "passive"))
    )
    (net (code "49") (name "DIB_A0") (class "Default")
      (node (ref "IC1") (pin "1") (pinfunction "A0_1") (pintype "input"))
      (node (ref "RN3") (pin "3") (pinfunction "1_3") (pintype "passive"))
      (node (ref "X1") (pin "17") (pinfunction "1_17") (pintype "passive"))
    )
    (net (code "50") (name "DIB_A1") (class "Default")
      (node (ref "IC1") (pin "2") (pinfunction "A1_2") (pintype "input"))
      (node (ref "RN3") (pin "2") (pinfunction "1_2") (pintype "passive"))
      (node (ref "X1") (pin "19") (pinfunction "1_19") (pintype "passive"))
    )
    (net (code "51") (name "DIB_A2") (class "Default")
      (node (ref "IC1") (pin "3") (pinfunction "A2_3") (pintype "input"))
      (node (ref "RN3") (pin "1") (pinfunction "1_1") (pintype "passive"))
      (node (ref "X1") (pin "18") (pinfunction "1_18") (pintype "passive"))
    )
    (net (code "52") (name "DIB_BOOT") (class "Default")
      (node (ref "IC3") (pin "4") (pinfunction "A2_4") (pintype "input"))
      (node (ref "X1") (pin "26") (pinfunction "1_26") (pintype "passive"))
    )
    (net (code "53") (name "DIB_CSA") (class "Default")
      (node (ref "IC2") (pin "5") (pinfunction "A3_5") (pintype "input"))
      (node (ref "RN2") (pin "2") (pinfunction "1_2") (pintype "passive"))
    )
    (net (code "54") (name "DIB_IRQ") (class "Default")
      (node (ref "IC3") (pin "6") (pinfunction "A4_6") (pintype "output"))
      (node (ref "X1") (pin "10") (pinfunction "1_10") (pintype "passive"))
    )
    (net (code "55") (name "DIB_MISO") (class "Default")
      (node (ref "IC2") (pin "6") (pinfunction "A4_6") (pintype "output"))
      (node (ref "RN2") (pin "1") (pinfunction "1_1") (pintype "passive"))
    )
    (net (code "56") (name "DIB_MOSI") (class "Default")
      (node (ref "IC2") (pin "3") (pinfunction "A1_3") (pintype "input"))
      (node (ref "RN2") (pin "4") (pinfunction "1_4") (pintype "passive"))
    )
    (net (code "57") (name "DIB_NRESET") (class "Default")
      (node (ref "IC3") (pin "5") (pinfunction "A3_5") (pintype "input"))
      (node (ref "X1") (pin "4") (pinfunction "1_4") (pintype "passive"))
    )
    (net (code "58") (name "DIB_SCL") (class "Default")
      (node (ref "IC1") (pin "6") (pinfunction "SCL_6") (pintype "bidirectional"))
      (node (ref "X1") (pin "5") (pinfunction "1_5") (pintype "passive"))
    )
    (net (code "59") (name "DIB_SCLK") (class "Default")
      (node (ref "IC2") (pin "4") (pinfunction "A2_4") (pintype "input"))
      (node (ref "RN2") (pin "3") (pinfunction "1_3") (pintype "passive"))
    )
    (net (code "60") (name "DIB_SDA") (class "Default")
      (node (ref "IC1") (pin "5") (pinfunction "SDA_5") (pintype "bidirectional"))
      (node (ref "X1") (pin "8") (pinfunction "1_8") (pintype "passive"))
    )
    (net (code "61") (name "DIN0") (class "Default")
      (node (ref "C76") (pin "1") (pinfunction "1_1") (pintype "passive"))
      (node (ref "C81") (pin "1") (pinfunction "1_1") (pintype "passive"))
      (node (ref "D7") (pin "3") (pinfunction "C1A2_3") (pintype "passive"))
      (node (ref "IC8") (pin "34") (pinfunction "PA0-WKUP_34") (pintype "bidirectional"))
      (node (ref "R36") (pin "2") (pinfunction "2_2") (pintype "passive"))
      (node (ref "R44") (pin "2") (pinfunction "2_2") (pintype "passive"))
      (node (ref "R52") (pin "1") (pinfunction "1_1") (pintype "passive"))
    )
    (net (code "62") (name "DIN1") (class "Default")
      (node (ref "C77") (pin "1") (pinfunction "1_1") (pintype "passive"))
      (node (ref "C82") (pin "1") (pinfunction "1_1") (pintype "passive"))
      (node (ref "D8") (pin "3") (pinfunction "C1A2_3") (pintype "passive"))
      (node (ref "IC8") (pin "35") (pinfunction "PA1_35") (pintype "bidirectional"))
      (node (ref "R37") (pin "2") (pinfunction "2_2") (pintype "passive"))
      (node (ref "R45") (pin "2") (pinfunction "2_2") (pintype "passive"))
      (node (ref "R53") (pin "1") (pinfunction "1_1") (pintype "passive"))
    )
    (net (code "63") (name "DIN2") (class "Default")
      (node (ref "C78") (pin "1") (pinfunction "1_1") (pintype "passive"))
      (node (ref "D9") (pin "3") (pinfunction "C1A2_3") (pintype "passive"))
      (node (ref "IC8") (pin "96") (pinfunction "PC6_96") (pintype "bidirectional"))
      (node (ref "R38") (pin "2") (pinfunction "2_2") (pintype "passive"))
      (node (ref "R46") (pin "2") (pinfunction "2_2") (pintype "passive"))
      (node (ref "R54") (pin "1") (pinfunction "1_1") (pintype "passive"))
    )
    (net (code "64") (name "DIN3") (class "Default")
      (node (ref "C83") (pin "1") (pinfunction "1_1") (pintype "passive"))
      (node (ref "D10") (pin "3") (pinfunction "C1A2_3") (pintype "passive"))
      (node (ref "IC8") (pin "97") (pinfunction "PC7_97") (pintype "bidirectional"))
      (node (ref "R39") (pin "2") (pinfunction "2_2") (pintype "passive"))
      (node (ref "R47") (pin "2") (pinfunction "2_2") (pintype "passive"))
      (node (ref "R55") (pin "1") (pinfunction "1_1") (pintype "passive"))
    )
    (net (code "65") (name "DIN4") (class "Default")
      (node (ref "C79") (pin "1") (pinfunction "1_1") (pintype "passive"))
      (node (ref "D11") (pin "3") (pinfunction "C1A2_3") (pintype "passive"))
      (node (ref "IC8") (pin "134") (pinfunction "PB4_134") (pintype "bidirectional"))
      (node (ref "R40") (pin "2") (pinfunction "2_2") (pintype "passive"))
      (node (ref "R48") (pin "2") (pinfunction "2_2") (pintype "passive"))
      (node (ref "R56") (pin "1") (pinfunction "1_1") (pintype "passive"))
    )
    (net (code "66") (name "DIN5") (class "Default")
      (node (ref "C84") (pin "1") (pinfunction "1_1") (pintype "passive"))
      (node (ref "D12") (pin "3") (pinfunction "C1A2_3") (pintype "passive"))
      (node (ref "IC8") (pin "135") (pinfunction "PB5_135") (pintype "bidirectional"))
      (node (ref "R41") (pin "2") (pinfunction "2_2") (pintype "passive"))
      (node (ref "R49") (pin "2") (pinfunction "2_2") (pintype "passive"))
      (node (ref "R57") (pin "1") (pinfunction "1_1") (pintype "passive"))
    )
    (net (code "67") (name "DIN6") (class "Default")
      (node (ref "C80") (pin "1") (pinfunction "1_1") (pintype "passive"))
      (node (ref "D13") (pin "3") (pinfunction "C1A2_3") (pintype "passive"))
      (node (ref "IC8") (pin "136") (pinfunction "PB6_136") (pintype "bidirectional"))
      (node (ref "R42") (pin "2") (pinfunction "2_2") (pintype "passive"))
      (node (ref "R50") (pin "2") (pinfunction "2_2") (pintype "passive"))
      (node (ref "R58") (pin "1") (pinfunction "1_1") (pintype "passive"))
    )
    (net (code "68") (name "DIN7") (class "Default")
      (node (ref "C85") (pin "1") (pinfunction "1_1") (pintype "passive"))
      (node (ref "D14") (pin "3") (pinfunction "C1A2_3") (pintype "passive"))
      (node (ref "IC8") (pin "137") (pinfunction "PB7_137") (pintype "bidirectional"))
      (node (ref "R43") (pin "2") (pinfunction "2_2") (pintype "passive"))
      (node (ref "R51") (pin "2") (pinfunction "2_2") (pintype "passive"))
      (node (ref "R59") (pin "1") (pinfunction "1_1") (pintype "passive"))
    )
    (net (code "69") (name "DOUT0") (class "Default")
      (node (ref "IC18") (pin "2") (pinfunction "IN1_2") (pintype "input"))
      (node (ref "IC8") (pin "100") (pinfunction "PA8_100") (pintype "bidirectional"))
    )
    (net (code "70") (name "DOUT1") (class "Default")
      (node (ref "IC18") (pin "3") (pinfunction "IN2_3") (pintype "input"))
      (node (ref "IC8") (pin "101") (pinfunction "PA9_101") (pintype "bidirectional"))
    )
    (net (code "71") (name "DOUT2") (class "Default")
      (node (ref "IC17") (pin "2") (pinfunction "IN1_2") (pintype "input"))
      (node (ref "IC8") (pin "91") (pinfunction "PG6_91") (pintype "bidirectional"))
    )
    (net (code "72") (name "DOUT3") (class "Default")
      (node (ref "IC17") (pin "3") (pinfunction "IN2_3") (pintype "input"))
      (node (ref "IC8") (pin "92") (pinfunction "PG7_92") (pintype "bidirectional"))
    )
    (net (code "73") (name "DOUT4") (class "Default")
      (node (ref "IC16") (pin "2") (pinfunction "IN1_2") (pintype "input"))
      (node (ref "IC8") (pin "44") (pinfunction "PC4_44") (pintype "bidirectional"))
    )
    (net (code "74") (name "DOUT5") (class "Default")
      (node (ref "IC16") (pin "3") (pinfunction "IN2_3") (pintype "input"))
      (node (ref "IC8") (pin "45") (pinfunction "PC5_45") (pintype "bidirectional"))
    )
    (net (code "75") (name "DOUT6") (class "Default")
      (node (ref "IC15") (pin "2") (pinfunction "IN1_2") (pintype "input"))
      (node (ref "IC8") (pin "46") (pinfunction "PB0_46") (pintype "bidirectional"))
    )
    (net (code "76") (name "DOUT7") (class "Default")
      (node (ref "IC15") (pin "3") (pinfunction "IN2_3") (pintype "input"))
      (node (ref "IC8") (pin "47") (pinfunction "PB1_47") (pintype "bidirectional"))
    )
    (net (code "77") (name "GND") (class "Default")
      (node (ref "C10") (pin "2") (pinfunction "2_2") (pintype "passive"))
      (node (ref "C11") (pin "1") (pinfunction "1_1") (pintype "passive"))
      (node (ref "C13") (pin "1") (pinfunction "1_1") (pintype "passive"))
      (node (ref "C14") (pin "2") (pinfunction "2_2") (pintype "passive"))
      (node (ref "C15") (pin "2") (pinfunction "2_2") (pintype "passive"))
      (node (ref "C16") (pin "1") (pinfunction "1_1") (pintype "passive"))
      (node (ref "C17") (pin "1") (pinfunction "1_1") (pintype "passive"))
      (node (ref "C18") (pin "1") (pinfunction "1_1") (pintype "passive"))
      (node (ref "C19") (pin "1") (pinfunction "1_1") (pintype "passive"))
      (node (ref "C21") (pin "2") (pinfunction "2_2") (pintype "passive"))
      (node (ref "C22") (pin "1") (pinfunction "1_1") (pintype "passive"))
      (node (ref "C23") (pin "1") (pinfunction "1_1") (pintype "passive"))
      (node (ref "C25") (pin "-") (pinfunction "-_-") (pintype "passive"))
      (node (ref "C26") (pin "2") (pinfunction "2_2") (pintype "passive"))
      (node (ref "C27") (pin "2") (pinfunction "2_2") (pintype "passive"))
      (node (ref "C28") (pin "2") (pinfunction "2_2") (pintype "passive"))
      (node (ref "C29") (pin "2") (pinfunction "2_2") (pintype "passive"))
      (node (ref "C3") (pin "1") (pinfunction "1_1") (pintype "passive"))
      (node (ref "C30") (pin "2") (pinfunction "2_2") (pintype "passive"))
      (node (ref "C31") (pin "2") (pinfunction "2_2") (pintype "passive"))
      (node (ref "C32") (pin "2") (pinfunction "2_2") (pintype "passive"))
      (node (ref "C33") (pin "2") (pinfunction "2_2") (pintype "passive"))
      (node (ref "C34") (pin "2") (pinfunction "2_2") (pintype "passive"))
      (node (ref "C35") (pin "2") (pinfunction "2_2") (pintype "passive"))
      (node (ref "C36") (pin "2") (pinfunction "2_2") (pintype "passive"))
      (node (ref "C37") (pin "2") (pinfunction "2_2") (pintype "passive"))
      (node (ref "C38") (pin "2") (pinfunction "2_2") (pintype "passive"))
      (node (ref "C39") (pin "1") (pinfunction "1_1") (pintype "passive"))
      (node (ref "C40") (pin "1") (pinfunction "1_1") (pintype "passive"))
      (node (ref "C43") (pin "2") (pinfunction "2_2") (pintype "passive"))
      (node (ref "C44") (pin "1") (pinfunction "1_1") (pintype "passive"))
      (node (ref "C45") (pin "2") (pinfunction "2_2") (pintype "passive"))
      (node (ref "C46") (pin "2") (pinfunction "2_2") (pintype "passive"))
      (node (ref "C47") (pin "2") (pinfunction "2_2") (pintype "passive"))
      (node (ref "C48") (pin "1") (pinfunction "1_1") (pintype "passive"))
      (node (ref "C49") (pin "1") (pinfunction "1_1") (pintype "passive"))
      (node (ref "C5") (pin "1") (pinfunction "1_1") (pintype "passive"))
      (node (ref "C52") (pin "2") (pinfunction "2_2") (pintype "passive"))
      (node (ref "C53") (pin "1") (pinfunction "1_1") (pintype "passive"))
      (node (ref "C54") (pin "2") (pinfunction "2_2") (pintype "passive"))
      (node (ref "C55") (pin "2") (pinfunction "2_2") (pintype "passive"))
      (node (ref "C56") (pin "2") (pinfunction "2_2") (pintype "passive"))
      (node (ref "C57") (pin "2") (pinfunction "2_2") (pintype "passive"))
      (node (ref "C58") (pin "2") (pinfunction "2_2") (pintype "passive"))
      (node (ref "C59") (pin "1") (pinfunction "1_1") (pintype "passive"))
      (node (ref "C60") (pin "1") (pinfunction "1_1") (pintype "passive"))
      (node (ref "C61") (pin "2") (pinfunction "2_2") (pintype "passive"))
      (node (ref "C62") (pin "2") (pinfunction "2_2") (pintype "passive"))
      (node (ref "C63") (pin "1") (pinfunction "1_1") (pintype "passive"))
      (node (ref "C64") (pin "2") (pinfunction "2_2") (pintype "passive"))
      (node (ref "C65") (pin "2") (pinfunction "2_2") (pintype "passive"))
      (node (ref "C66") (pin "1") (pinfunction "1_1") (pintype "passive"))
      (node (ref "C67") (pin "2") (pinfunction "2_2") (pintype "passive"))
      (node (ref "C68") (pin "2") (pinfunction "2_2") (pintype "passive"))
      (node (ref "C69") (pin "1") (pinfunction "1_1") (pintype "passive"))
      (node (ref "C70") (pin "1") (pinfunction "1_1") (pintype "passive"))
      (node (ref "C71") (pin "1") (pinfunction "1_1") (pintype "passive"))
      (node (ref "C72") (pin "1") (pinfunction "1_1") (pintype "passive"))
      (node (ref "C73") (pin "1") (pinfunction "1_1") (pintype "passive"))
      (node (ref "C74") (pin "2") (pinfunction "2_2") (pintype "passive"))
      (node (ref "C75") (pin "2") (pinfunction "2_2") (pintype "passive"))
      (node (ref "C76") (pin "2") (pinfunction "2_2") (pintype "passive"))
      (node (ref "C77") (pin "2") (pinfunction "2_2") (pintype "passive"))
      (node (ref "C78") (pin "2") (pinfunction "2_2") (pintype "passive"))
      (node (ref "C79") (pin "2") (pinfunction "2_2") (pintype "passive"))
      (node (ref "C80") (pin "2") (pinfunction "2_2") (pintype "passive"))
      (node (ref "C83") (pin "2") (pinfunction "2_2") (pintype "passive"))
      (node (ref "C84") (pin "2") (pinfunction "2_2") (pintype "passive"))
      (node (ref "C85") (pin "2") (pinfunction "2_2") (pintype "passive"))
      (node (ref "C86") (pin "2") (pinfunction "2_2") (pintype "passive"))
      (node (ref "C87") (pin "2") (pinfunction "2_2") (pintype "passive"))
      (node (ref "C88") (pin "2") (pinfunction "2_2") (pintype "passive"))
      (node (ref "C91") (pin "1") (pinfunction "1_1") (pintype "passive"))
      (node (ref "C92") (pin "1") (pinfunction "1_1") (pintype "passive"))
      (node (ref "C93") (pin "1") (pinfunction "1_1") (pintype "passive"))
      (node (ref "C94") (pin "1") (pinfunction "1_1") (pintype "passive"))
      (node (ref "C95") (pin "1") (pinfunction "1_1") (pintype "passive"))
      (node (ref "C98") (pin "2") (pinfunction "2_2") (pintype "passive"))
      (node (ref "D10") (pin "1") (pinfunction "A1_1") (pintype "passive"))
      (node (ref "D11") (pin "1") (pinfunction "A1_1") (pintype "passive"))
      (node (ref "D12") (pin "1") (pinfunction "A1_1") (pintype "passive"))
      (node (ref "D13") (pin "1") (pinfunction "A1_1") (pintype "passive"))
      (node (ref "D14") (pin "1") (pinfunction "A1_1") (pintype "passive"))
      (node (ref "D5") (pin "1") (pinfunction "A1_1") (pintype "passive"))
      (node (ref "D6") (pin "1") (pinfunction "A1_1") (pintype "passive"))
      (node (ref "D7") (pin "1") (pinfunction "A1_1") (pintype "passive"))
      (node (ref "D8") (pin "1") (pinfunction "A1_1") (pintype "passive"))
      (node (ref "D9") (pin "1") (pinfunction "A1_1") (pintype "passive"))
      (node (ref "IC10") (pin "11") (pinfunction "GND_11") (pintype "power_in"))
      (node (ref "IC10") (pin "12") (pinfunction "GND_12") (pintype "power_in"))
      (node (ref "IC10") (pin "16") (pinfunction "DVDD-EN_16") (pintype "power_in"))
      (node (ref "IC10") (pin "25") (pinfunction "EPAD_25") (pintype "passive"))
      (node (ref "IC10") (pin "4") (pinfunction "GND_4") (pintype "power_in"))
      (node (ref "IC11") (pin "11") (pinfunction "GND_11") (pintype "power_in"))
      (node (ref "IC11") (pin "12") (pinfunction "GND_12") (pintype "power_in"))
      (node (ref "IC11") (pin "16") (pinfunction "DVDD-EN_16") (pintype "power_in"))
      (node (ref "IC11") (pin "25") (pinfunction "EPAD_25") (pintype "passive"))
      (node (ref "IC11") (pin "4") (pinfunction "GND_4") (pintype "power_in"))
      (node (ref "IC12") (pin "5") (pinfunction "V+_5") (pintype "power_in"))
      (node (ref "IC13") (pin "3") (pinfunction "GND_3") (pintype "power_in"))
      (node (ref "IC13") (pin "4") (pinfunction "~{LDAC}_4") (pintype "input"))
      (node (ref "IC19") (pin "7") (pinfunction "V-_7") (pintype "power_in"))
      (node (ref "IC2") (pin "15") (pinfunction "GND2_15") (pintype "passive"))
      (node (ref "IC2") (pin "9") (pinfunction "GND2_2_9") (pintype "passive"))
      (node (ref "IC20") (pin "3") (pinfunction "A_3") (pintype "passive"))
      (node (ref "IC21") (pin "4") (pinfunction "GND_4") (pintype "passive"))
      (node (ref "IC22") (pin "4") (pinfunction "GND_4") (pintype "passive"))
      (node (ref "IC23") (pin "4") (pinfunction "GND_4") (pintype "passive"))
      (node (ref "IC24") (pin "4") (pinfunction "GND_4") (pintype "passive"))
      (node (ref "IC25") (pin "4") (pinfunction "GND_4") (pintype "passive"))
      (node (ref "IC26") (pin "4") (pinfunction "GND_4") (pintype "passive"))
      (node (ref "IC27") (pin "4") (pinfunction "GND_4") (pintype "passive"))
      (node (ref "IC28") (pin "4") (pinfunction "GND_4") (pintype "passive"))
      (node (ref "IC29") (pin "4") (pinfunction "GND_4") (pintype "passive"))
      (node (ref "IC3") (pin "15") (pinfunction "GND2_15") (pintype "passive"))
      (node (ref "IC3") (pin "9") (pinfunction "GND2_2_9") (pintype "passive"))
      (node (ref "IC30") (pin "4") (pinfunction "GND_4") (pintype "passive"))
      (node (ref "IC31") (pin "4") (pinfunction "GND_4") (pintype "passive"))
      (node (ref "IC32") (pin "4") (pinfunction "GND_4") (pintype "passive"))
      (node (ref "IC33") (pin "4") (pinfunction "GND_4") (pintype "passive"))
      (node (ref "IC34") (pin "4") (pinfunction "GND_4") (pintype "passive"))
      (node (ref "IC35") (pin "2") (pinfunction "V-_2") (pintype "power_in"))
      (node (ref "IC36") (pin "11") (pinfunction "AUX_GND_11") (pintype "power_in"))
      (node (ref "IC36") (pin "28") (pinfunction "AGND_28") (pintype "power_in"))
      (node (ref "IC36") (pin "29") (pinfunction "AGND_29") (pintype "power_in"))
      (node (ref "IC36") (pin "3") (pinfunction "DAISY_3") (pintype "input"))
      (node (ref "IC36") (pin "31") (pinfunction "AGND_31") (pintype "power_in"))
      (node (ref "IC36") (pin "32") (pinfunction "AGND_32") (pintype "power_in"))
      (node (ref "IC36") (pin "33") (pinfunction "DGND_33") (pintype "power_in"))
      (node (ref "IC36") (pin "4") (pinfunction "~{REFSEL}_4") (pintype "input"))
      (node (ref "IC36") (pin "6") (pinfunction "REFGND_6") (pintype "power_in"))
      (node (ref "IC36") (pin "8") (pinfunction "AGND_8") (pintype "power_in"))
      (node (ref "IC4") (pin "2") (pinfunction "GND_2") (pintype "passive"))
      (node (ref "IC4") (pin "3") (pinfunction "GND_3") (pintype "passive"))
      (node (ref "IC4") (pin "6") (pinfunction "GND_6") (pintype "passive"))
      (node (ref "IC4") (pin "7") (pinfunction "GND_7") (pintype "passive"))
      (node (ref "IC5") (pin "2") (pinfunction "GND_2") (pintype "passive"))
      (node (ref "IC6") (pin "2") (pinfunction "GND_2") (pintype "passive"))
      (node (ref "IC7") (pin "5") (pinfunction "GND_5") (pintype "passive"))
      (node (ref "IC8") (pin "107") (pinfunction "VSS_8_107") (pintype "power_in"))
      (node (ref "IC8") (pin "120") (pinfunction "VSS_9_120") (pintype "power_in"))
      (node (ref "IC8") (pin "130") (pinfunction "VSS_130") (pintype "power_in"))
      (node (ref "IC8") (pin "16") (pinfunction "VSS_2_16") (pintype "bidirectional"))
      (node (ref "IC8") (pin "31") (pinfunction "VSSA_31") (pintype "power_in"))
      (node (ref "IC8") (pin "38") (pinfunction "VSS_3_38") (pintype "power_in"))
      (node (ref "IC8") (pin "51") (pinfunction "VSS_4_51") (pintype "power_in"))
      (node (ref "IC8") (pin "61") (pinfunction "VSS_5_61") (pintype "power_in"))
      (node (ref "IC8") (pin "83") (pinfunction "VSS_6_83") (pintype "power_in"))
      (node (ref "IC8") (pin "94") (pinfunction "VSS_7_94") (pintype "power_in"))
      (node (ref "J2") (pin "6") (pinfunction "VSS_6") (pintype "power_in"))
      (node (ref "J2") (pin "S") (pinfunction "SH_S") (pintype "passive"))
      (node (ref "J2") (pin "S1") (pinfunction "SH_S1") (pintype "passive"))
      (node (ref "J2") (pin "S2") (pinfunction "SH_S2") (pintype "passive"))
      (node (ref "J2") (pin "SW2") (pinfunction "SW2_SW2") (pintype "passive"))
      (node (ref "L2") (pin "3") (pinfunction "3_3") (pintype "passive"))
      (node (ref "L3") (pin "2") (pinfunction "2_2") (pintype "passive"))
      (node (ref "Q1") (pin "1") (pinfunction "S_1") (pintype "passive"))
      (node (ref "Q1") (pin "4") (pinfunction "S_4") (pintype "passive"))
      (node (ref "Q2") (pin "1") (pinfunction "S_1") (pintype "passive"))
      (node (ref "Q2") (pin "4") (pinfunction "S_4") (pintype "passive"))
      (node (ref "Q3") (pin "1") (pinfunction "S_1") (pintype "passive"))
      (node (ref "Q3") (pin "4") (pinfunction "S_4") (pintype "passive"))
      (node (ref "Q4") (pin "1") (pinfunction "S_1") (pintype "passive"))
      (node (ref "Q4") (pin "4") (pinfunction "S_4") (pintype "passive"))
      (node (ref "Q5") (pin "1") (pinfunction "S_1") (pintype "passive"))
      (node (ref "Q5") (pin "4") (pinfunction "S_4") (pintype "passive"))
      (node (ref "R10") (pin "1") (pinfunction "1_1") (pintype "passive"))
      (node (ref "R14") (pin "1") (pinfunction "1_1") (pintype "passive"))
      (node (ref "R22") (pin "2") (pinfunction "2_2") (pintype "passive"))
      (node (ref "R23") (pin "2") (pinfunction "2_2") (pintype "passive"))
      (node (ref "R29") (pin "2") (pinfunction "2_2") (pintype "passive"))
      (node (ref "R35") (pin "2") (pinfunction "2_2") (pintype "passive"))
      (node (ref "R44") (pin "1") (pinfunction "1_1") (pintype "passive"))
      (node (ref "R45") (pin "1") (pinfunction "1_1") (pintype "passive"))
      (node (ref "R46") (pin "1") (pinfunction "1_1") (pintype "passive"))
      (node (ref "R47") (pin "1") (pinfunction "1_1") (pintype "passive"))
      (node (ref "R48") (pin "1") (pinfunction "1_1") (pintype "passive"))
      (node (ref "R49") (pin "1") (pinfunction "1_1") (pintype "passive"))
      (node (ref "R50") (pin "1") (pinfunction "1_1") (pintype "passive"))
      (node (ref "R51") (pin "1") (pinfunction "1_1") (pintype "passive"))
      (node (ref "R7") (pin "1") (pinfunction "1_1") (pintype "passive"))
      (node (ref "R81") (pin "2") (pinfunction "2_2") (pintype "passive"))
      (node (ref "SH2") (pin "1") (pinfunction "GND_A_1") (pintype "bidirectional"))
      (node (ref "SH3") (pin "1") (pinfunction "GND_A_1") (pintype "bidirectional"))
      (node (ref "SH4") (pin "1") (pinfunction "GND_A_1") (pintype "bidirectional"))
      (node (ref "SH5") (pin "1") (pinfunction "GND_A_1") (pintype "bidirectional"))
      (node (ref "SH6") (pin "1") (pinfunction "GND_A_1") (pintype "bidirectional"))
      (node (ref "SH7") (pin "1") (pinfunction "GND_A_1") (pintype "bidirectional"))
      (node (ref "SH8") (pin "1") (pinfunction "GND_A_1") (pintype "bidirectional"))
      (node (ref "TVS3") (pin "C1") (pinfunction "1_C1") (pintype "passive"))
      (node (ref "TVS4") (pin "C1") (pinfunction "1_C1") (pintype "passive"))
      (node (ref "X2") (pin "3") (pinfunction "1_3") (pintype "passive"))
      (node (ref "X3") (pin "1") (pinfunction "1_1") (pintype "passive"))
      (node (ref "X3") (pin "8") (pinfunction "1_8") (pintype "passive"))
      (node (ref "X4") (pin "2") (pinfunction "1_2") (pintype "passive"))
      (node (ref "X4") (pin "4") (pinfunction "1_4") (pintype "passive"))
      (node (ref "X4") (pin "6") (pinfunction "1_6") (pintype "passive"))
      (node (ref "X4") (pin "8") (pinfunction "1_8") (pintype "passive"))
    )
    (net (code "78") (name "GNDIO") (class "Default")
      (node (ref "C1") (pin "1") (pinfunction "1_1") (pintype "passive"))
      (node (ref "C2") (pin "2") (pinfunction "2_2") (pintype "passive"))
      (node (ref "C4") (pin "2") (pinfunction "2_2") (pintype "passive"))
      (node (ref "C7") (pin "1") (pinfunction "1_1") (pintype "passive"))
      (node (ref "IC1") (pin "4") (pinfunction "GND_4") (pintype "passive"))
      (node (ref "IC1") (pin "7") (pinfunction "WP_7") (pintype "input"))
      (node (ref "IC2") (pin "2") (pinfunction "GND1_2_2") (pintype "passive"))
      (node (ref "IC2") (pin "8") (pinfunction "GND1_8") (pintype "passive"))
      (node (ref "IC3") (pin "2") (pinfunction "GND1_2_2") (pintype "passive"))
      (node (ref "IC3") (pin "8") (pinfunction "GND1_8") (pintype "passive"))
      (node (ref "L1") (pin "1") (pinfunction "1_1") (pintype "passive"))
      (node (ref "X1") (pin "11") (pinfunction "1_11") (pintype "passive"))
      (node (ref "X1") (pin "16") (pinfunction "1_16") (pintype "passive"))
      (node (ref "X1") (pin "20") (pinfunction "1_20") (pintype "passive"))
      (node (ref "X1") (pin "25") (pinfunction "1_25") (pintype "passive"))
      (node (ref "X1") (pin "7") (pinfunction "1_7") (pintype "passive"))
    )
    (net (code "79") (name "IN_CTRL0") (class "Default")
      (node (ref "IC8") (pin "123") (pinfunction "PD7_123") (pintype "bidirectional"))
      (node (ref "Q2") (pin "2") (pinfunction "G_2") (pintype "passive"))
    )
    (net (code "80") (name "IN_CTRL1") (class "Default")
      (node (ref "IC8") (pin "124") (pinfunction "PG9_124") (pintype "bidirectional"))
      (node (ref "Q2") (pin "5") (pinfunction "G_5") (pintype "passive"))
    )
    (net (code "81") (name "IN_CTRL2") (class "Default")
      (node (ref "IC8") (pin "125") (pinfunction "PG10_125") (pintype "bidirectional"))
      (node (ref "Q3") (pin "2") (pinfunction "G_2") (pintype "passive"))
    )
    (net (code "82") (name "IN_CTRL3") (class "Default")
      (node (ref "IC8") (pin "126") (pinfunction "PG11_126") (pintype "bidirectional"))
      (node (ref "Q3") (pin "5") (pinfunction "G_5") (pintype "passive"))
    )
    (net (code "83") (name "IN_CTRL4") (class "Default")
      (node (ref "IC8") (pin "127") (pinfunction "PG12_127") (pintype "bidirectional"))
      (node (ref "Q4") (pin "2") (pinfunction "G_2") (pintype "passive"))
    )
    (net (code "84") (name "IN_CTRL5") (class "Default")
      (node (ref "IC8") (pin "128") (pinfunction "PG13_128") (pintype "bidirectional"))
      (node (ref "Q4") (pin "5") (pinfunction "G_5") (pintype "passive"))
    )
    (net (code "85") (name "IN_CTRL6") (class "Default")
      (node (ref "IC8") (pin "129") (pinfunction "PG14_129") (pintype "bidirectional"))
      (node (ref "Q5") (pin "2") (pinfunction "G_2") (pintype "passive"))
    )
    (net (code "86") (name "IN_CTRL7") (class "Default")
      (node (ref "IC8") (pin "133") (pinfunction "PB3_133") (pintype "bidirectional"))
      (node (ref "Q5") (pin "5") (pinfunction "G_5") (pintype "passive"))
    )
    (net (code "87") (name "IRQ") (class "Default")
      (node (ref "IC3") (pin "11") (pinfunction "B4_11") (pintype "input"))
      (node (ref "IC8") (pin "69") (pinfunction "PB10_69") (pintype "bidirectional"))
    )
    (net (code "88") (name "MISO") (class "Default")
      (node (ref "IC2") (pin "11") (pinfunction "B4_11") (pintype "input"))
      (node (ref "IC8") (pin "75") (pinfunction "PB14_75") (pintype "bidirectional"))
    )
    (net (code "89") (name "MOSI") (class "Default")
      (node (ref "IC8") (pin "76") (pinfunction "PB15_76") (pintype "bidirectional"))
      (node (ref "RN1") (pin "8") (pinfunction "2_8") (pintype "passive"))
    )
    (net (code "90") (name "NSS") (class "Default")
      (node (ref "IC8") (pin "73") (pinfunction "PB12_73") (pintype "bidirectional"))
      (node (ref "RN1") (pin "6") (pinfunction "2_6") (pintype "passive"))
    )
    (net (code "91") (name "Net-(D1-C1A2)") (class "Default")
      (node (ref "C42") (pin "1") (pinfunction "1_1") (pintype "passive"))
      (node (ref "D1") (pin "3") (pinfunction "C1A2_3") (pintype "passive"))
      (node (ref "FB2") (pin "P$2") (pinfunction "2_P$2") (pintype "passive"))
      (node (ref "TVS1") (pin "C2") (pinfunction "2_C2") (pintype "passive"))
      (node (ref "X3") (pin "2") (pinfunction "1_2") (pintype "passive"))
    )
    (net (code "92") (name "Net-(D2-C1A2)") (class "Default")
      (node (ref "C51") (pin "1") (pinfunction "1_1") (pintype "passive"))
      (node (ref "D2") (pin "3") (pinfunction "C1A2_3") (pintype "passive"))
      (node (ref "FB3") (pin "P$2") (pinfunction "2_P$2") (pintype "passive"))
      (node (ref "TVS2") (pin "C2") (pinfunction "2_C2") (pintype "passive"))
      (node (ref "X3") (pin "3") (pinfunction "1_3") (pintype "passive"))
    )
    (net (code "93") (name "Net-(D3-C1A2)") (class "Default")
      (node (ref "C62") (pin "1") (pinfunction "1_1") (pintype "passive"))
      (node (ref "D3") (pin "3") (pinfunction "C1A2_3") (pintype "passive"))
      (node (ref "R17") (pin "1") (pinfunction "1_1") (pintype "passive"))
      (node (ref "R20") (pin "2") (pinfunction "2_2") (pintype "passive"))
      (node (ref "X3") (pin "4") (pinfunction "1_4") (pintype "passive"))
    )
    (net (code "94") (name "Net-(D4-C1A2)") (class "Default")
      (node (ref "C68") (pin "1") (pinfunction "1_1") (pintype "passive"))
      (node (ref "D4") (pin "3") (pinfunction "C1A2_3") (pintype "passive"))
      (node (ref "R25") (pin "1") (pinfunction "1_1") (pintype "passive"))
      (node (ref "R27") (pin "2") (pinfunction "2_2") (pintype "passive"))
      (node (ref "X3") (pin "5") (pinfunction "1_5") (pintype "passive"))
    )
    (net (code "95") (name "Net-(D5-C1A2)") (class "Default")
      (node (ref "D5") (pin "3") (pinfunction "C1A2_3") (pintype "passive"))
      (node (ref "IC19") (pin "3") (pinfunction "O_3") (pintype "output"))
      (node (ref "IC19") (pin "6") (pinfunction "O_6") (pintype "output"))
      (node (ref "R31") (pin "2") (pinfunction "2_2") (pintype "passive"))
    )
    (net (code "96") (name "Net-(D6-C1A2)") (class "Default")
      (node (ref "D6") (pin "3") (pinfunction "C1A2_3") (pintype "passive"))
      (node (ref "IC19") (pin "11") (pinfunction "O_11") (pintype "output"))
      (node (ref "IC19") (pin "8") (pinfunction "O_8") (pintype "output"))
      (node (ref "R32") (pin "2") (pinfunction "2_2") (pintype "passive"))
    )
    (net (code "97") (name "Net-(FB1-1)") (class "Default")
      (node (ref "C24") (pin "2") (pinfunction "2_2") (pintype "passive"))
      (node (ref "C25") (pin "+") (pinfunction "+_+") (pintype "passive"))
      (node (ref "C26") (pin "1") (pinfunction "1_1") (pintype "passive"))
      (node (ref "C27") (pin "1") (pinfunction "1_1") (pintype "passive"))
      (node (ref "C28") (pin "1") (pinfunction "1_1") (pintype "passive"))
      (node (ref "C29") (pin "1") (pinfunction "1_1") (pintype "passive"))
      (node (ref "C30") (pin "1") (pinfunction "1_1") (pintype "passive"))
      (node (ref "C31") (pin "1") (pinfunction "1_1") (pintype "passive"))
      (node (ref "C32") (pin "1") (pinfunction "1_1") (pintype "passive"))
      (node (ref "C33") (pin "1") (pinfunction "1_1") (pintype "passive"))
      (node (ref "C34") (pin "1") (pinfunction "1_1") (pintype "passive"))
      (node (ref "C35") (pin "1") (pinfunction "1_1") (pintype "passive"))
      (node (ref "C36") (pin "1") (pinfunction "1_1") (pintype "passive"))
      (node (ref "FB1") (pin "P$1") (pinfunction "1_P$1") (pintype "passive"))
      (node (ref "IC8") (pin "108") (pinfunction "VDD_9_108") (pintype "power_in"))
      (node (ref "IC8") (pin "121") (pinfunction "VDD_10_121") (pintype "power_in"))
      (node (ref "IC8") (pin "131") (pinfunction "VDD_11_131") (pintype "power_in"))
      (node (ref "IC8") (pin "143") (pinfunction "PDR_ON_143") (pintype "input"))
      (node (ref "IC8") (pin "144") (pinfunction "VDD_144") (pintype "power_in"))
      (node (ref "IC8") (pin "17") (pinfunction "VDD_2_17") (pintype "bidirectional"))
      (node (ref "IC8") (pin "30") (pinfunction "VDD_3_30") (pintype "power_in"))
      (node (ref "IC8") (pin "39") (pinfunction "VDD_4_39") (pintype "power_in"))
      (node (ref "IC8") (pin "52") (pinfunction "VDD_5_52") (pintype "power_in"))
      (node (ref "IC8") (pin "6") (pinfunction "VBAT_6") (pintype "power_in"))
      (node (ref "IC8") (pin "62") (pinfunction "VDD_6_62") (pintype "power_in"))
      (node (ref "IC8") (pin "72") (pinfunction "VDD_7_72") (pintype "power_in"))
      (node (ref "IC8") (pin "84") (pinfunction "VDD_8_84") (pintype "power_in"))
      (node (ref "IC8") (pin "95") (pinfunction "VDDUSB_95") (pintype "power_in"))
      (node (ref "R6") (pin "1") (pinfunction "1_1") (pintype "passive"))
      (node (ref "SH1") (pin "1") (pinfunction "GND_A_1") (pintype "bidirectional"))
    )
    (net (code "98") (name "Net-(FB1-2)") (class "Default")
      (node (ref "C37") (pin "1") (pinfunction "1_1") (pintype "passive"))
      (node (ref "C38") (pin "1") (pinfunction "1_1") (pintype "passive"))
      (node (ref "FB1") (pin "P$2") (pinfunction "2_P$2") (pintype "passive"))
      (node (ref "IC8") (pin "33") (pinfunction "VDDA_33") (pintype "power_in"))
      (node (ref "R8") (pin "1") (pinfunction "1_1") (pintype "passive"))
    )
    (net (code "99") (name "Net-(FB2-1)") (class "Default")
      (node (ref "FB2") (pin "P$1") (pinfunction "1_P$1") (pintype "passive"))
      (node (ref "IC9") (pin "3") (pinfunction "+IN_3") (pintype "input"))
      (node (ref "R11") (pin "1") (pinfunction "1_1") (pintype "passive"))
      (node (ref "R9") (pin "1") (pinfunction "1_1") (pintype "passive"))
    )
    (net (code "100") (name "Net-(FB3-1)") (class "Default")
      (node (ref "FB3") (pin "P$1") (pinfunction "1_P$1") (pintype "passive"))
      (node (ref "IC9") (pin "5") (pinfunction "+IN_5") (pintype "input"))
      (node (ref "R13") (pin "1") (pinfunction "1_1") (pintype "passive"))
      (node (ref "R15") (pin "1") (pinfunction "1_1") (pintype "passive"))
    )
    (net (code "101") (name "Net-(FB4-1)") (class "Default")
      (node (ref "C65") (pin "1") (pinfunction "1_1") (pintype "passive"))
      (node (ref "C66") (pin "2") (pinfunction "2_2") (pintype "passive"))
      (node (ref "C67") (pin "1") (pinfunction "1_1") (pintype "passive"))
      (node (ref "FB4") (pin "P$1") (pinfunction "1_P$1") (pintype "passive"))
      (node (ref "IC12") (pin "2") (pinfunction "V-_2") (pintype "power_in"))
      (node (ref "IC13") (pin "9") (pinfunction "VDD_9") (pintype "power_in"))
    )
    (net (code "102") (name "Net-(FB5-1)") (class "Default")
      (node (ref "FB5") (pin "P$1") (pinfunction "1_P$1") (pintype "passive"))
      (node (ref "X4") (pin "1") (pinfunction "1_1") (pintype "passive"))
    )
    (net (code "103") (name "Net-(FB5-2)") (class "Default")
      (node (ref "FB5") (pin "P$2") (pinfunction "2_P$2") (pintype "passive"))
      (node (ref "Q6") (pin "3") (pinfunction "D_3") (pintype "passive"))
      (node (ref "R60") (pin "2") (pinfunction "2_2") (pintype "passive"))
      (node (ref "TVS5") (pin "C2") (pinfunction "2_C2") (pintype "passive"))
    )
    (net (code "104") (name "Net-(FB6-1)") (class "Default")
      (node (ref "FB6") (pin "P$1") (pinfunction "1_P$1") (pintype "passive"))
      (node (ref "X4") (pin "3") (pinfunction "1_3") (pintype "passive"))
    )
    (net (code "105") (name "Net-(FB6-2)") (class "Default")
      (node (ref "FB6") (pin "P$2") (pinfunction "2_P$2") (pintype "passive"))
      (node (ref "Q8") (pin "3") (pinfunction "D_3") (pintype "passive"))
      (node (ref "R61") (pin "2") (pinfunction "2_2") (pintype "passive"))
      (node (ref "TVS6") (pin "C2") (pinfunction "2_C2") (pintype "passive"))
    )
    (net (code "106") (name "Net-(FB7-1)") (class "Default")
      (node (ref "FB7") (pin "P$1") (pinfunction "1_P$1") (pintype "passive"))
      (node (ref "X4") (pin "5") (pinfunction "1_5") (pintype "passive"))
    )
    (net (code "107") (name "Net-(FB7-2)") (class "Default")
      (node (ref "FB7") (pin "P$2") (pinfunction "2_P$2") (pintype "passive"))
      (node (ref "JP4") (pin "1") (pinfunction "1_1") (pintype "passive"))
      (node (ref "Q10") (pin "3") (pinfunction "D_3") (pintype "passive"))
      (node (ref "TVS7") (pin "C2") (pinfunction "2_C2") (pintype "passive"))
    )
    (net (code "108") (name "Net-(FB9-1)") (class "Default")
      (node (ref "FB9") (pin "P$1") (pinfunction "1_P$1") (pintype "passive"))
      (node (ref "X4") (pin "7") (pinfunction "1_7") (pintype "passive"))
    )
    (net (code "109") (name "Net-(FB9-2)") (class "Default")
      (node (ref "FB9") (pin "P$2") (pinfunction "2_P$2") (pintype "passive"))
      (node (ref "JP5") (pin "1") (pinfunction "1_1") (pintype "passive"))
      (node (ref "Q12") (pin "3") (pinfunction "D_3") (pintype "passive"))
      (node (ref "TVS8") (pin "C2") (pinfunction "2_C2") (pintype "passive"))
    )
    (net (code "110") (name "Net-(IC2-B1)") (class "Default")
      (node (ref "IC2") (pin "14") (pinfunction "B1_14") (pintype "output"))
      (node (ref "RN1") (pin "1") (pinfunction "1_1") (pintype "passive"))
    )
    (net (code "111") (name "Net-(IC2-B2)") (class "Default")
      (node (ref "IC2") (pin "13") (pinfunction "B2_13") (pintype "output"))
      (node (ref "RN1") (pin "2") (pinfunction "1_2") (pintype "passive"))
    )
    (net (code "112") (name "Net-(IC2-B3)") (class "Default")
      (node (ref "IC2") (pin "12") (pinfunction "B3_12") (pintype "output"))
      (node (ref "RN1") (pin "3") (pinfunction "1_3") (pintype "passive"))
    )
    (net (code "113") (name "Net-(IC5-BYPASS)") (class "Default")
      (node (ref "C17") (pin "2") (pinfunction "2_2") (pintype "passive"))
      (node (ref "IC5") (pin "4") (pinfunction "BYPASS_4") (pintype "passive"))
    )
    (net (code "114") (name "Net-(IC6-BYPASS)") (class "Default")
      (node (ref "C19") (pin "2") (pinfunction "2_2") (pintype "passive"))
      (node (ref "IC6") (pin "4") (pinfunction "BYPASS_4") (pintype "passive"))
    )
    (net (code "115") (name "Net-(IC8A-PA4)") (class "Default")
      (node (ref "IC8") (pin "40") (pinfunction "PA4_40") (pintype "bidirectional"))
      (node (ref "RN5") (pin "8") (pinfunction "2_8") (pintype "passive"))
    )
    (net (code "116") (name "Net-(IC8A-PA5)") (class "Default")
      (node (ref "IC8") (pin "41") (pinfunction "PA5_41") (pintype "bidirectional"))
      (node (ref "RN5") (pin "7") (pinfunction "2_7") (pintype "passive"))
    )
    (net (code "117") (name "Net-(IC8A-PA6)") (class "Default")
      (node (ref "IC8") (pin "42") (pinfunction "PA6_42") (pintype "bidirectional"))
      (node (ref "RN5") (pin "6") (pinfunction "2_6") (pintype "passive"))
    )
    (net (code "118") (name "Net-(IC8A-PA7)") (class "Default")
      (node (ref "IC8") (pin "43") (pinfunction "PA7_43") (pintype "bidirectional"))
      (node (ref "RN5") (pin "5") (pinfunction "2_5") (pintype "passive"))
    )
    (net (code "119") (name "Net-(IC8B-PE2)") (class "Default")
      (node (ref "IC8") (pin "1") (pinfunction "PE2_1") (pintype "bidirectional"))
      (node (ref "RN4") (pin "8") (pinfunction "2_8") (pintype "passive"))
    )
    (net (code "120") (name "Net-(IC8B-PE4)") (class "Default")
      (node (ref "IC8") (pin "3") (pinfunction "PE4_3") (pintype "bidirectional"))
      (node (ref "RN4") (pin "7") (pinfunction "2_7") (pintype "passive"))
    )
    (net (code "121") (name "Net-(IC8B-PE5)") (class "Default")
      (node (ref "IC8") (pin "4") (pinfunction "PE5_4") (pintype "bidirectional"))
      (node (ref "RN4") (pin "6") (pinfunction "2_6") (pintype "passive"))
    )
    (net (code "122") (name "Net-(IC8B-PE6)") (class "Default")
      (node (ref "IC8") (pin "5") (pinfunction "PE6_5") (pintype "bidirectional"))
      (node (ref "RN4") (pin "5") (pinfunction "2_5") (pintype "passive"))
    )
    (net (code "123") (name "Net-(IC8B-PH0-OSC_IN)") (class "Default")
      (node (ref "C22") (pin "2") (pinfunction "2_2") (pintype "passive"))
      (node (ref "IC8") (pin "23") (pinfunction "PH0-OSC_IN_23") (pintype "bidirectional"))
      (node (ref "Y1") (pin "2") (pinfunction "2_2") (pintype "passive"))
    )
    (net (code "124") (name "Net-(IC8B-PH1-OSC_OUT)") (class "Default")
      (node (ref "C23") (pin "2") (pinfunction "2_2") (pintype "passive"))
      (node (ref "IC8") (pin "24") (pinfunction "PH1-OSC_OUT_24") (pintype "bidirectional"))
      (node (ref "Y1") (pin "1") (pinfunction "1_1") (pintype "passive"))
    )
    (net (code "125") (name "Net-(IC8C-VCAP_1)") (class "Default")
      (node (ref "C40") (pin "2") (pinfunction "2_2") (pintype "passive"))
      (node (ref "IC8") (pin "71") (pinfunction "VCAP_1_71") (pintype "power_in"))
    )
    (net (code "126") (name "Net-(IC8C-VCAP_2)") (class "Default")
      (node (ref "C39") (pin "2") (pinfunction "2_2") (pintype "passive"))
      (node (ref "IC8") (pin "106") (pinfunction "VCAP_2_106") (pintype "power_in"))
    )
    (net (code "127") (name "Net-(IC8C-VREF+)") (class "Default")
      (node (ref "IC8") (pin "32") (pinfunction "VREF+_32") (pintype "power_in"))
      (node (ref "R8") (pin "2") (pinfunction "2_2") (pintype "passive"))
    )
    (net (code "128") (name "Net-(IC10-+VSENSE)") (class "Default")
      (node (ref "IC10") (pin "22") (pinfunction "+VSENSE_22") (pintype "input"))
      (node (ref "IC9") (pin "1") (pinfunction "OUT_1") (pintype "output"))
      (node (ref "IC9") (pin "2") (pinfunction "-IN_2") (pintype "input"))
    )
    (net (code "129") (name "Net-(IC10--VSENSE)") (class "Default")
      (node (ref "C42") (pin "2") (pinfunction "2_2") (pintype "passive"))
      (node (ref "IC10") (pin "23") (pinfunction "-VSENSE_23") (pintype "input"))
      (node (ref "SH2") (pin "2") (pinfunction "GND_B_2") (pintype "bidirectional"))
      (node (ref "TVS1") (pin "C1") (pinfunction "1_C1") (pintype "passive"))
    )
    (net (code "130") (name "Net-(IC10-CMP)") (class "Default")
      (node (ref "C41") (pin "2") (pinfunction "2_2") (pintype "passive"))
      (node (ref "IC10") (pin "17") (pinfunction "CMP_17") (pintype "output"))
    )
    (net (code "131") (name "Net-(IC10-HART-IN)") (class "Default")
      (node (ref "C44") (pin "2") (pinfunction "2_2") (pintype "passive"))
      (node (ref "IC10") (pin "18") (pinfunction "HART-IN_18") (pintype "input"))
    )
    (net (code "132") (name "Net-(IC10-IOUT)") (class "Default")
      (node (ref "IC10") (pin "19") (pinfunction "IOUT_19") (pintype "output"))
      (node (ref "R9") (pin "2") (pinfunction "2_2") (pintype "passive"))
    )
    (net (code "133") (name "Net-(IC10-ISET-R)") (class "Default")
      (node (ref "IC10") (pin "13") (pinfunction "ISET-R_13") (pintype "input"))
      (node (ref "R10") (pin "2") (pinfunction "2_2") (pintype "passive"))
    )
    (net (code "134") (name "Net-(IC10-REFIN)") (class "Default")
      (node (ref "C45") (pin "1") (pinfunction "1_1") (pintype "passive"))
      (node (ref "IC10") (pin "14") (pinfunction "REFOUT_14") (pintype "output"))
      (node (ref "IC10") (pin "15") (pinfunction "REFIN_15") (pintype "input"))
    )
    (net (code "135") (name "Net-(IC10-VOUT)") (class "Default")
      (node (ref "C41") (pin "1") (pinfunction "1_1") (pintype "passive"))
      (node (ref "IC10") (pin "21") (pinfunction "VOUT_21") (pintype "output"))
      (node (ref "R11") (pin "2") (pinfunction "2_2") (pintype "passive"))
    )
    (net (code "136") (name "Net-(IC11-+VSENSE)") (class "Default")
      (node (ref "IC11") (pin "22") (pinfunction "+VSENSE_22") (pintype "input"))
      (node (ref "IC9") (pin "6") (pinfunction "-IN_6") (pintype "input"))
      (node (ref "IC9") (pin "7") (pinfunction "OUT_7") (pintype "output"))
    )
    (net (code "137") (name "Net-(IC11--VSENSE)") (class "Default")
      (node (ref "C51") (pin "2") (pinfunction "2_2") (pintype "passive"))
      (node (ref "IC11") (pin "23") (pinfunction "-VSENSE_23") (pintype "input"))
      (node (ref "SH3") (pin "2") (pinfunction "GND_B_2") (pintype "bidirectional"))
      (node (ref "TVS2") (pin "C1") (pinfunction "1_C1") (pintype "passive"))
    )
    (net (code "138") (name "Net-(IC11-CMP)") (class "Default")
      (node (ref "C50") (pin "2") (pinfunction "2_2") (pintype "passive"))
      (node (ref "IC11") (pin "17") (pinfunction "CMP_17") (pintype "output"))
    )
    (net (code "139") (name "Net-(IC11-HART-IN)") (class "Default")
      (node (ref "C53") (pin "2") (pinfunction "2_2") (pintype "passive"))
      (node (ref "IC11") (pin "18") (pinfunction "HART-IN_18") (pintype "input"))
    )
    (net (code "140") (name "Net-(IC11-IOUT)") (class "Default")
      (node (ref "IC11") (pin "19") (pinfunction "IOUT_19") (pintype "output"))
      (node (ref "R13") (pin "2") (pinfunction "2_2") (pintype "passive"))
    )
    (net (code "141") (name "Net-(IC11-ISET-R)") (class "Default")
      (node (ref "IC11") (pin "13") (pinfunction "ISET-R_13") (pintype "input"))
      (node (ref "R14") (pin "2") (pinfunction "2_2") (pintype "passive"))
    )
    (net (code "142") (name "Net-(IC11-REFIN)") (class "Default")
      (node (ref "C54") (pin "1") (pinfunction "1_1") (pintype "passive"))
      (node (ref "IC11") (pin "14") (pinfunction "REFOUT_14") (pintype "output"))
      (node (ref "IC11") (pin "15") (pinfunction "REFIN_15") (pintype "input"))
    )
    (net (code "143") (name "Net-(IC11-VOUT)") (class "Default")
      (node (ref "C50") (pin "1") (pinfunction "1_1") (pintype "passive"))
      (node (ref "IC11") (pin "21") (pinfunction "VOUT_21") (pintype "output"))
      (node (ref "R15") (pin "2") (pinfunction "2_2") (pintype "passive"))
    )
    (net (code "144") (name "Net-(IC12A-+IN)") (class "Default")
      (node (ref "IC12") (pin "3") (pinfunction "+IN_3") (pintype "input"))
      (node (ref "R18") (pin "2") (pinfunction "2_2") (pintype "passive"))
      (node (ref "R22") (pin "1") (pinfunction "1_1") (pintype "passive"))
    )
    (net (code "145") (name "Net-(IC13-VOUTA)") (class "Default")
      (node (ref "IC13") (pin "1") (pinfunction "VOUTA_1") (pintype "output"))
      (node (ref "R21") (pin "2") (pinfunction "2_2") (pintype "passive"))
    )
    (net (code "146") (name "Net-(IC13-VOUTB)") (class "Default")
      (node (ref "IC13") (pin "2") (pinfunction "VOUTB_2") (pintype "output"))
      (node (ref "R28") (pin "2") (pinfunction "2_2") (pintype "passive"))
    )
    (net (code "147") (name "Net-(IC13-VREF)") (class "Default")
      (node (ref "C63") (pin "2") (pinfunction "2_2") (pintype "passive"))
      (node (ref "IC13") (pin "10") (pinfunction "VREF_10") (pintype "bidirectional"))
      (node (ref "R18") (pin "1") (pinfunction "1_1") (pintype "passive"))
    )
    (net (code "148") (name "Net-(IC14A-+IN)") (class "Default")
      (node (ref "IC14") (pin "3") (pinfunction "+IN_3") (pintype "input"))
      (node (ref "R28") (pin "1") (pinfunction "1_1") (pintype "passive"))
      (node (ref "R29") (pin "1") (pinfunction "1_1") (pintype "passive"))
    )
    (net (code "149") (name "Net-(IC14A--IN)") (class "Default")
      (node (ref "IC14") (pin "2") (pinfunction "-IN_2") (pintype "input"))
      (node (ref "R24") (pin "1") (pinfunction "1_1") (pintype "passive"))
      (node (ref "R25") (pin "2") (pinfunction "2_2") (pintype "passive"))
    )
    (net (code "150") (name "Net-(IC14A-OUT)") (class "Default")
      (node (ref "IC14") (pin "1") (pinfunction "OUT_1") (pintype "output"))
      (node (ref "R26") (pin "1") (pinfunction "1_1") (pintype "passive"))
    )
    (net (code "151") (name "Net-(IC14B-+IN)") (class "Default")
      (node (ref "IC14") (pin "5") (pinfunction "+IN_5") (pintype "input"))
      (node (ref "R21") (pin "1") (pinfunction "1_1") (pintype "passive"))
      (node (ref "R23") (pin "1") (pinfunction "1_1") (pintype "passive"))
    )
    (net (code "152") (name "Net-(IC14B--IN)") (class "Default")
      (node (ref "IC14") (pin "6") (pinfunction "-IN_6") (pintype "input"))
      (node (ref "R16") (pin "1") (pinfunction "1_1") (pintype "passive"))
      (node (ref "R17") (pin "2") (pinfunction "2_2") (pintype "passive"))
    )
    (net (code "153") (name "Net-(IC14B-OUT)") (class "Default")
      (node (ref "IC14") (pin "7") (pinfunction "OUT_7") (pintype "output"))
      (node (ref "R19") (pin "1") (pinfunction "1_1") (pintype "passive"))
    )
    (net (code "154") (name "Net-(IC15-GND)") (class "Default")
      (node (ref "IC15") (pin "6") (pinfunction "GND_6") (pintype "passive"))
      (node (ref "IC16") (pin "6") (pinfunction "GND_6") (pintype "passive"))
      (node (ref "IC17") (pin "6") (pinfunction "GND_6") (pintype "passive"))
      (node (ref "IC18") (pin "6") (pinfunction "GND_6") (pintype "passive"))
      (node (ref "SH4") (pin "2") (pinfunction "GND_B_2") (pintype "bidirectional"))
    )
    (net (code "155") (name "Net-(IC20-R)") (class "Default")
      (node (ref "IC20") (pin "2") (pinfunction "R_2") (pintype "passive"))
      (node (ref "R34") (pin "2") (pinfunction "2_2") (pintype "passive"))
      (node (ref "R35") (pin "1") (pinfunction "1_1") (pintype "passive"))
    )
    (net (code "156") (name "Net-(IC21B-COM)") (class "Default")
      (node (ref "IC21") (pin "6") (pinfunction "COM_6") (pintype "bidirectional"))
      (node (ref "IC26") (pin "6") (pinfunction "COM_6") (pintype "bidirectional"))
      (node (ref "JP3") (pin "COM") (pinfunction "COM_COM") (pintype "passive"))
    )
    (net (code "157") (name "Net-(IC21B-NO)") (class "Default")
      (node (ref "IC21") (pin "1") (pinfunction "NO_1") (pintype "bidirectional"))
      (node (ref "R60") (pin "1") (pinfunction "1_1") (pintype "passive"))
    )
    (net (code "158") (name "Net-(IC22B-COM)") (class "Default")
      (node (ref "IC22") (pin "6") (pinfunction "COM_6") (pintype "bidirectional"))
      (node (ref "IC31") (pin "6") (pinfunction "COM_6") (pintype "bidirectional"))
      (node (ref "R63") (pin "1") (pinfunction "1_1") (pintype "passive"))
    )
    (net (code "159") (name "Net-(IC22B-NO)") (class "Default")
      (node (ref "IC22") (pin "1") (pinfunction "NO_1") (pintype "bidirectional"))
      (node (ref "IC27") (pin "6") (pinfunction "COM_6") (pintype "bidirectional"))
      (node (ref "R68") (pin "2") (pinfunction "2_2") (pintype "passive"))
    )
    (net (code "160") (name "Net-(IC23B-COM)") (class "Default")
      (node (ref "IC23") (pin "6") (pinfunction "COM_6") (pintype "bidirectional"))
      (node (ref "IC32") (pin "6") (pinfunction "COM_6") (pintype "bidirectional"))
      (node (ref "R71") (pin "1") (pinfunction "1_1") (pintype "passive"))
    )
    (net (code "161") (name "Net-(IC23B-NO)") (class "Default")
      (node (ref "IC23") (pin "1") (pinfunction "NO_1") (pintype "bidirectional"))
      (node (ref "IC28") (pin "6") (pinfunction "COM_6") (pintype "bidirectional"))
      (node (ref "R72") (pin "2") (pinfunction "2_2") (pintype "passive"))
    )
    (net (code "162") (name "Net-(IC24B-COM)") (class "Default")
      (node (ref "IC24") (pin "6") (pinfunction "COM_6") (pintype "bidirectional"))
      (node (ref "IC33") (pin "6") (pinfunction "COM_6") (pintype "bidirectional"))
      (node (ref "JP4") (pin "2") (pinfunction "2_2") (pintype "passive"))
      (node (ref "R75") (pin "1") (pinfunction "1_1") (pintype "passive"))
    )
    (net (code "163") (name "Net-(IC24B-NO)") (class "Default")
      (node (ref "IC24") (pin "1") (pinfunction "NO_1") (pintype "bidirectional"))
      (node (ref "IC29") (pin "6") (pinfunction "COM_6") (pintype "bidirectional"))
      (node (ref "R76") (pin "2") (pinfunction "2_2") (pintype "passive"))
    )
    (net (code "164") (name "Net-(IC25B-COM)") (class "Default")
      (node (ref "IC25") (pin "6") (pinfunction "COM_6") (pintype "bidirectional"))
      (node (ref "IC34") (pin "6") (pinfunction "COM_6") (pintype "bidirectional"))
      (node (ref "JP5") (pin "2") (pinfunction "2_2") (pintype "passive"))
      (node (ref "R79") (pin "1") (pinfunction "1_1") (pintype "passive"))
    )
    (net (code "165") (name "Net-(IC25B-NO)") (class "Default")
      (node (ref "IC25") (pin "1") (pinfunction "NO_1") (pintype "bidirectional"))
      (node (ref "IC30") (pin "6") (pinfunction "COM_6") (pintype "bidirectional"))
      (node (ref "R82") (pin "2") (pinfunction "2_2") (pintype "passive"))
    )
    (net (code "166") (name "Net-(IC26B-NO)") (class "Default")
      (node (ref "IC26") (pin "1") (pinfunction "NO_1") (pintype "bidirectional"))
      (node (ref "R61") (pin "1") (pinfunction "1_1") (pintype "passive"))
    )
    (net (code "167") (name "Net-(IC27B-NO)") (class "Default")
      (node (ref "IC27") (pin "1") (pinfunction "NO_1") (pintype "bidirectional"))
      (node (ref "IC31") (pin "1") (pinfunction "NO_1") (pintype "bidirectional"))
      (node (ref "Q7") (pin "3") (pinfunction "D_3") (pintype "passive"))
    )
    (net (code "168") (name "Net-(IC28B-NO)") (class "Default")
      (node (ref "IC28") (pin "1") (pinfunction "NO_1") (pintype "bidirectional"))
      (node (ref "IC32") (pin "1") (pinfunction "NO_1") (pintype "bidirectional"))
      (node (ref "Q9") (pin "3") (pinfunction "D_3") (pintype "passive"))
    )
    (net (code "169") (name "Net-(IC29B-NO)") (class "Default")
      (node (ref "IC29") (pin "1") (pinfunction "NO_1") (pintype "bidirectional"))
      (node (ref "IC33") (pin "1") (pinfunction "NO_1") (pintype "bidirectional"))
      (node (ref "Q11") (pin "3") (pinfunction "D_3") (pintype "passive"))
    )
    (net (code "170") (name "Net-(IC30B-NO)") (class "Default")
      (node (ref "IC30") (pin "1") (pinfunction "NO_1") (pintype "bidirectional"))
      (node (ref "IC34") (pin "1") (pinfunction "NO_1") (pintype "bidirectional"))
      (node (ref "Q13") (pin "3") (pinfunction "D_3") (pintype "passive"))
    )
    (net (code "171") (name "Net-(IC35A--IN)") (class "Default")
      (node (ref "IC35") (pin "1") (pinfunction "OUT_1") (pintype "output"))
      (node (ref "IC35") (pin "4") (pinfunction "-IN_4") (pintype "input"))
      (node (ref "JP3") (pin "NC") (pinfunction "NC_NC") (pintype "passive"))
    )
    (net (code "172") (name "Net-(IC36-REFCAP)") (class "Default")
      (node (ref "C92") (pin "2") (pinfunction "2_2") (pintype "passive"))
      (node (ref "C93") (pin "2") (pinfunction "2_2") (pintype "passive"))
      (node (ref "IC36") (pin "7") (pinfunction "REFCAP_7") (pintype "output"))
    )
    (net (code "173") (name "Net-(Q1A-D)") (class "Default")
      (node (ref "C82") (pin "2") (pinfunction "2_2") (pintype "passive"))
      (node (ref "Q1") (pin "6") (pinfunction "D_6") (pintype "passive"))
    )
    (net (code "174") (name "Net-(Q1B-D)") (class "Default")
      (node (ref "C81") (pin "2") (pinfunction "2_2") (pintype "passive"))
      (node (ref "Q1") (pin "3") (pinfunction "D_3") (pintype "passive"))
    )
    (net (code "175") (name "Net-(Q2A-D)") (class "Default")
      (node (ref "Q2") (pin "6") (pinfunction "D_6") (pintype "passive"))
      (node (ref "R52") (pin "2") (pinfunction "2_2") (pintype "passive"))
    )
    (net (code "176") (name "Net-(Q2B-D)") (class "Default")
      (node (ref "Q2") (pin "3") (pinfunction "D_3") (pintype "passive"))
      (node (ref "R53") (pin "2") (pinfunction "2_2") (pintype "passive"))
    )
    (net (code "177") (name "Net-(Q3A-D)") (class "Default")
      (node (ref "Q3") (pin "6") (pinfunction "D_6") (pintype "passive"))
      (node (ref "R54") (pin "2") (pinfunction "2_2") (pintype "passive"))
    )
    (net (code "178") (name "Net-(Q3B-D)") (class "Default")
      (node (ref "Q3") (pin "3") (pinfunction "D_3") (pintype "passive"))
      (node (ref "R55") (pin "2") (pinfunction "2_2") (pintype "passive"))
    )
    (net (code "179") (name "Net-(Q4A-D)") (class "Default")
      (node (ref "Q4") (pin "6") (pinfunction "D_6") (pintype "passive"))
      (node (ref "R56") (pin "2") (pinfunction "2_2") (pintype "passive"))
    )
    (net (code "180") (name "Net-(Q4B-D)") (class "Default")
      (node (ref "Q4") (pin "3") (pinfunction "D_3") (pintype "passive"))
      (node (ref "R57") (pin "2") (pinfunction "2_2") (pintype "passive"))
    )
    (net (code "181") (name "Net-(Q5A-D)") (class "Default")
      (node (ref "Q5") (pin "6") (pinfunction "D_6") (pintype "passive"))
      (node (ref "R58") (pin "2") (pinfunction "2_2") (pintype "passive"))
    )
    (net (code "182") (name "Net-(Q5B-D)") (class "Default")
      (node (ref "Q5") (pin "3") (pinfunction "D_3") (pintype "passive"))
      (node (ref "R59") (pin "2") (pinfunction "2_2") (pintype "passive"))
    )
    (net (code "183") (name "Net-(Q6-G)") (class "Default")
      (node (ref "Q6") (pin "1") (pinfunction "G_1") (pintype "passive"))
      (node (ref "Q7") (pin "2") (pinfunction "S_2") (pintype "passive"))
      (node (ref "R62") (pin "1") (pinfunction "1_1") (pintype "passive"))
    )
    (net (code "184") (name "Net-(Q6-S)") (class "Default")
      (node (ref "Q6") (pin "2") (pinfunction "S_2") (pintype "passive"))
      (node (ref "Q7") (pin "1") (pinfunction "G_1") (pintype "passive"))
      (node (ref "R62") (pin "2") (pinfunction "2_2") (pintype "passive"))
    )
    (net (code "185") (name "Net-(Q8-G)") (class "Default")
      (node (ref "Q8") (pin "1") (pinfunction "G_1") (pintype "passive"))
      (node (ref "Q9") (pin "2") (pinfunction "S_2") (pintype "passive"))
      (node (ref "R70") (pin "1") (pinfunction "1_1") (pintype "passive"))
    )
    (net (code "186") (name "Net-(Q8-S)") (class "Default")
      (node (ref "Q8") (pin "2") (pinfunction "S_2") (pintype "passive"))
      (node (ref "Q9") (pin "1") (pinfunction "G_1") (pintype "passive"))
      (node (ref "R70") (pin "2") (pinfunction "2_2") (pintype "passive"))
    )
    (net (code "187") (name "Net-(Q10-G)") (class "Default")
      (node (ref "Q10") (pin "1") (pinfunction "G_1") (pintype "passive"))
      (node (ref "Q11") (pin "2") (pinfunction "S_2") (pintype "passive"))
      (node (ref "R74") (pin "1") (pinfunction "1_1") (pintype "passive"))
    )
    (net (code "188") (name "Net-(Q10-S)") (class "Default")
      (node (ref "Q10") (pin "2") (pinfunction "S_2") (pintype "passive"))
      (node (ref "Q11") (pin "1") (pinfunction "G_1") (pintype "passive"))
      (node (ref "R74") (pin "2") (pinfunction "2_2") (pintype "passive"))
    )
    (net (code "189") (name "Net-(Q12-G)") (class "Default")
      (node (ref "Q12") (pin "1") (pinfunction "G_1") (pintype "passive"))
      (node (ref "Q13") (pin "2") (pinfunction "S_2") (pintype "passive"))
      (node (ref "R78") (pin "1") (pinfunction "1_1") (pintype "passive"))
    )
    (net (code "190") (name "Net-(Q12-S)") (class "Default")
      (node (ref "Q12") (pin "2") (pinfunction "S_2") (pintype "passive"))
      (node (ref "Q13") (pin "1") (pinfunction "G_1") (pintype "passive"))
      (node (ref "R78") (pin "2") (pinfunction "2_2") (pintype "passive"))
    )
    (net (code "191") (name "Net-(R80-Pad2)") (class "Default")
      (node (ref "R80") (pin "2") (pinfunction "2_2") (pintype "passive"))
      (node (ref "R81") (pin "1") (pinfunction "1_1") (pintype "passive"))
    )
    (net (code "192") (name "Net-(RN2A-2)") (class "Default")
      (node (ref "RN2") (pin "8") (pinfunction "2_8") (pintype "passive"))
      (node (ref "X1") (pin "14") (pinfunction "1_14") (pintype "passive"))
    )
    (net (code "193") (name "Net-(RN2B-2)") (class "Default")
      (node (ref "RN2") (pin "7") (pinfunction "2_7") (pintype "passive"))
      (node (ref "X1") (pin "9") (pinfunction "1_9") (pintype "passive"))
    )
    (net (code "194") (name "Net-(RN2C-2)") (class "Default")
      (node (ref "RN2") (pin "6") (pinfunction "2_6") (pintype "passive"))
      (node (ref "X1") (pin "13") (pinfunction "1_13") (pintype "passive"))
    )
    (net (code "195") (name "Net-(RN2D-2)") (class "Default")
      (node (ref "RN2") (pin "5") (pinfunction "2_5") (pintype "passive"))
      (node (ref "X1") (pin "15") (pinfunction "1_15") (pintype "passive"))
    )
    (net (code "196") (name "Net-(SH5-GND_B)") (class "Default")
      (node (ref "R68") (pin "1") (pinfunction "1_1") (pintype "passive"))
      (node (ref "R69") (pin "1") (pinfunction "1_1") (pintype "passive"))
      (node (ref "SH5") (pin "2") (pinfunction "GND_B_2") (pintype "bidirectional"))
      (node (ref "TVS5") (pin "C1") (pinfunction "1_C1") (pintype "passive"))
    )
    (net (code "197") (name "Net-(SH6-GND_B)") (class "Default")
      (node (ref "R72") (pin "1") (pinfunction "1_1") (pintype "passive"))
      (node (ref "R73") (pin "1") (pinfunction "1_1") (pintype "passive"))
      (node (ref "SH6") (pin "2") (pinfunction "GND_B_2") (pintype "bidirectional"))
      (node (ref "TVS6") (pin "C1") (pinfunction "1_C1") (pintype "passive"))
    )
    (net (code "198") (name "Net-(SH7-GND_B)") (class "Default")
      (node (ref "R76") (pin "1") (pinfunction "1_1") (pintype "passive"))
      (node (ref "R77") (pin "1") (pinfunction "1_1") (pintype "passive"))
      (node (ref "SH7") (pin "2") (pinfunction "GND_B_2") (pintype "bidirectional"))
      (node (ref "TVS7") (pin "C1") (pinfunction "1_C1") (pintype "passive"))
    )
    (net (code "199") (name "Net-(SH8-GND_B)") (class "Default")
      (node (ref "R82") (pin "1") (pinfunction "1_1") (pintype "passive"))
      (node (ref "R83") (pin "1") (pinfunction "1_1") (pintype "passive"))
      (node (ref "SH8") (pin "2") (pinfunction "GND_B_2") (pintype "bidirectional"))
      (node (ref "TVS8") (pin "C1") (pinfunction "1_C1") (pintype "passive"))
    )
    (net (code "200") (name "Net-(TR1-COMM)") (class "Default")
      (node (ref "C12") (pin "2") (pinfunction "2_2") (pintype "passive"))
      (node (ref "C20") (pin "2") (pinfunction "2_2") (pintype "passive"))
      (node (ref "C6") (pin "2") (pinfunction "2_2") (pintype "passive"))
      (node (ref "C9") (pin "1") (pinfunction "1_1") (pintype "passive"))
      (node (ref "L2") (pin "4") (pinfunction "4_4") (pintype "passive"))
      (node (ref "L3") (pin "1") (pinfunction "1_1") (pintype "passive"))
      (node (ref "TR1") (pin "5") (pinfunction "COMM_5") (pintype "passive"))
      (node (ref "TR2") (pin "6") (pinfunction "COMM_6") (pintype "passive"))
    )
    (net (code "201") (name "Net-(TR1-IN+)") (class "Default")
      (node (ref "C6") (pin "1") (pinfunction "1_1") (pintype "passive"))
      (node (ref "C8") (pin "2") (pinfunction "2_2") (pintype "passive"))
      (node (ref "L1") (pin "3") (pinfunction "3_3") (pintype "passive"))
      (node (ref "TR1") (pin "1") (pinfunction "IN+_1") (pintype "input"))
      (node (ref "TR2") (pin "1") (pinfunction "IN+_1") (pintype "input"))
    )
    (net (code "202") (name "Net-(TR1-IN-)") (class "Default")
      (node (ref "C12") (pin "1") (pinfunction "1_1") (pintype "passive"))
      (node (ref "C8") (pin "1") (pinfunction "1_1") (pintype "passive"))
      (node (ref "L1") (pin "2") (pinfunction "2_2") (pintype "passive"))
      (node (ref "TR1") (pin "2") (pinfunction "IN-_2") (pintype "input"))
      (node (ref "TR2") (pin "2") (pinfunction "IN-_2") (pintype "input"))
    )
    (net (code "203") (name "Net-(TR1-OUT+)") (class "Default")
      (node (ref "C9") (pin "2") (pinfunction "2_2") (pintype "passive"))
      (node (ref "L2") (pin "1") (pinfunction "1_1") (pintype "passive"))
      (node (ref "TR1") (pin "6") (pinfunction "OUT+_6") (pintype "passive"))
      (node (ref "TR2") (pin "7") (pinfunction "OUT+_7") (pintype "passive"))
    )
    (net (code "204") (name "Net-(TR1-OUT-)") (class "Default")
      (node (ref "C20") (pin "1") (pinfunction "1_1") (pintype "passive"))
      (node (ref "L3") (pin "4") (pinfunction "4_4") (pintype "passive"))
      (node (ref "TR1") (pin "4") (pinfunction "OUT-_4") (pintype "passive"))
      (node (ref "TR2") (pin "5") (pinfunction "OUT-_5") (pintype "passive"))
    )
    (net (code "205") (name "Net-(TVS3-2)") (class "Default")
      (node (ref "R19") (pin "2") (pinfunction "2_2") (pintype "passive"))
      (node (ref "R20") (pin "1") (pinfunction "1_1") (pintype "passive"))
      (node (ref "TVS3") (pin "C2") (pinfunction "2_C2") (pintype "passive"))
    )
    (net (code "206") (name "Net-(TVS4-2)") (class "Default")
      (node (ref "R26") (pin "2") (pinfunction "2_2") (pintype "passive"))
      (node (ref "R27") (pin "1") (pinfunction "1_1") (pintype "passive"))
      (node (ref "TVS4") (pin "C2") (pinfunction "2_C2") (pintype "passive"))
    )
    (net (code "207") (name "Net-(X3M-1)") (class "Default")
      (node (ref "R31") (pin "1") (pinfunction "1_1") (pintype "passive"))
      (node (ref "X3") (pin "6") (pinfunction "1_6") (pintype "passive"))
    )
    (net (code "208") (name "Net-(X3N-1)") (class "Default")
      (node (ref "R32") (pin "1") (pinfunction "1_1") (pintype "passive"))
      (node (ref "X3") (pin "7") (pinfunction "1_7") (pintype "passive"))
    )
    (net (code "209") (name "Net-(X4B-1)") (class "Default")
      (node (ref "R37") (pin "1") (pinfunction "1_1") (pintype "passive"))
      (node (ref "X4") (pin "10") (pinfunction "1_10") (pintype "passive"))
    )
    (net (code "210") (name "Net-(X4C-1)") (class "Default")
      (node (ref "R38") (pin "1") (pinfunction "1_1") (pintype "passive"))
      (node (ref "X4") (pin "11") (pinfunction "1_11") (pintype "passive"))
    )
    (net (code "211") (name "Net-(X4D-1)") (class "Default")
      (node (ref "R39") (pin "1") (pinfunction "1_1") (pintype "passive"))
      (node (ref "X4") (pin "12") (pinfunction "1_12") (pintype "passive"))
    )
    (net (code "212") (name "Net-(X4E-1)") (class "Default")
      (node (ref "R40") (pin "1") (pinfunction "1_1") (pintype "passive"))
      (node (ref "X4") (pin "13") (pinfunction "1_13") (pintype "passive"))
    )
    (net (code "213") (name "Net-(X4F-1)") (class "Default")
      (node (ref "R41") (pin "1") (pinfunction "1_1") (pintype "passive"))
      (node (ref "X4") (pin "14") (pinfunction "1_14") (pintype "passive"))
    )
    (net (code "214") (name "Net-(X4G-1)") (class "Default")
      (node (ref "R42") (pin "1") (pinfunction "1_1") (pintype "passive"))
      (node (ref "X4") (pin "15") (pinfunction "1_15") (pintype "passive"))
    )
    (net (code "215") (name "Net-(X4H-1)") (class "Default")
      (node (ref "R43") (pin "1") (pinfunction "1_1") (pintype "passive"))
      (node (ref "X4") (pin "16") (pinfunction "1_16") (pintype "passive"))
    )
    (net (code "216") (name "Net-(X4P-1)") (class "Default")
      (node (ref "R36") (pin "1") (pinfunction "1_1") (pintype "passive"))
      (node (ref "X4") (pin "9") (pinfunction "1_9") (pintype "passive"))
    )
    (net (code "217") (name "OE_SYNC") (class "Default")
      (node (ref "IC3") (pin "3") (pinfunction "A1_3") (pintype "input"))
      (node (ref "X1") (pin "6") (pinfunction "1_6") (pintype "passive"))
    )
    (net (code "218") (name "OUT_EN") (class "Default")
      (node (ref "IC15") (pin "4") (pinfunction "ENA_4") (pintype "input"))
      (node (ref "IC16") (pin "4") (pinfunction "ENA_4") (pintype "input"))
      (node (ref "IC17") (pin "4") (pinfunction "ENA_4") (pintype "input"))
      (node (ref "IC18") (pin "4") (pinfunction "ENA_4") (pintype "input"))
      (node (ref "IC19") (pin "1") (pinfunction "EN_1") (pintype "input"))
      (node (ref "IC19") (pin "10") (pinfunction "EN_10") (pintype "input"))
      (node (ref "IC19") (pin "13") (pinfunction "EN_13") (pintype "input"))
      (node (ref "IC19") (pin "4") (pinfunction "EN_4") (pintype "input"))
      (node (ref "IC8") (pin "70") (pinfunction "PB11_70") (pintype "bidirectional"))
    )
    (net (code "219") (name "PE") (class "Default")
      (node (ref "C98") (pin "1") (pinfunction "1_1") (pintype "passive"))
      (node (ref "J1") (pin "1") (pinfunction "P$1_1") (pintype "bidirectional"))
      (node (ref "J1") (pin "2") (pinfunction "P$1_2") (pintype "bidirectional"))
      (node (ref "R80") (pin "1") (pinfunction "1_1") (pintype "passive"))
    )
    (net (code "220") (name "POUT0") (class "Default")
      (node (ref "IC18") (pin "7") (pinfunction "OUT1_7") (pintype "output"))
      (node (ref "X3") (pin "9") (pinfunction "1_9") (pintype "passive"))
    )
    (net (code "221") (name "POUT1") (class "Default")
      (node (ref "IC18") (pin "5") (pinfunction "OUT2_5") (pintype "output"))
      (node (ref "X3") (pin "10") (pinfunction "1_10") (pintype "passive"))
    )
    (net (code "222") (name "POUT2") (class "Default")
      (node (ref "IC17") (pin "7") (pinfunction "OUT1_7") (pintype "output"))
      (node (ref "X3") (pin "11") (pinfunction "1_11") (pintype "passive"))
    )
    (net (code "223") (name "POUT3") (class "Default")
      (node (ref "IC17") (pin "5") (pinfunction "OUT2_5") (pintype "output"))
      (node (ref "X3") (pin "12") (pinfunction "1_12") (pintype "passive"))
    )
    (net (code "224") (name "POUT4") (class "Default")
      (node (ref "IC16") (pin "7") (pinfunction "OUT1_7") (pintype "output"))
      (node (ref "X3") (pin "13") (pinfunction "1_13") (pintype "passive"))
    )
    (net (code "225") (name "POUT5") (class "Default")
      (node (ref "IC16") (pin "5") (pinfunction "OUT2_5") (pintype "output"))
      (node (ref "X3") (pin "14") (pinfunction "1_14") (pintype "passive"))
    )
    (net (code "226") (name "POUT6") (class "Default")
      (node (ref "IC15") (pin "7") (pinfunction "OUT1_7") (pintype "output"))
      (node (ref "X3") (pin "15") (pinfunction "1_15") (pintype "passive"))
    )
    (net (code "227") (name "POUT7") (class "Default")
      (node (ref "IC15") (pin "5") (pinfunction "OUT2_5") (pintype "output"))
      (node (ref "X3") (pin "16") (pinfunction "1_16") (pintype "passive"))
    )
    (net (code "228") (name "PWM#1") (class "Default")
      (node (ref "IC19") (pin "2") (pinfunction "I_2") (pintype "input"))
      (node (ref "IC19") (pin "5") (pinfunction "I_5") (pintype "input"))
      (node (ref "IC8") (pin "81") (pinfunction "PD12_81") (pintype "bidirectional"))
    )
    (net (code "229") (name "PWM#2") (class "Default")
      (node (ref "IC19") (pin "12") (pinfunction "I_12") (pintype "input"))
      (node (ref "IC19") (pin "9") (pinfunction "I_9") (pintype "input"))
      (node (ref "IC8") (pin "82") (pinfunction "PD13_82") (pintype "bidirectional"))
    )
    (net (code "230") (name "SCLK") (class "Default")
      (node (ref "IC8") (pin "74") (pinfunction "PB13_74") (pintype "bidirectional"))
      (node (ref "RN1") (pin "7") (pinfunction "2_7") (pintype "passive"))
    )
    (net (code "231") (name "SDIO_CLK") (class "Default")
      (node (ref "IC8") (pin "113") (pinfunction "PC12_113") (pintype "bidirectional"))
      (node (ref "J2") (pin "5") (pinfunction "CLK_5") (pintype "passive"))
    )
    (net (code "232") (name "SDIO_CMD") (class "Default")
      (node (ref "IC8") (pin "116") (pinfunction "PD2_116") (pintype "bidirectional"))
      (node (ref "J2") (pin "3") (pinfunction "CMD_3") (pintype "passive"))
      (node (ref "R4") (pin "2") (pinfunction "2_2") (pintype "passive"))
    )
    (net (code "233") (name "SDIO_D0") (class "Default")
      (node (ref "IC8") (pin "98") (pinfunction "PC8_98") (pintype "bidirectional"))
      (node (ref "J2") (pin "7") (pinfunction "DAT0_7") (pintype "passive"))
      (node (ref "R2") (pin "2") (pinfunction "2_2") (pintype "passive"))
    )
    (net (code "234") (name "SDIO_D1") (class "Default")
      (node (ref "IC8") (pin "99") (pinfunction "PC9_99") (pintype "bidirectional"))
      (node (ref "J2") (pin "8") (pinfunction "DAT1_8") (pintype "passive"))
      (node (ref "R5") (pin "2") (pinfunction "2_2") (pintype "passive"))
    )
    (net (code "235") (name "SDIO_D2") (class "Default")
      (node (ref "IC8") (pin "111") (pinfunction "PC10_111") (pintype "bidirectional"))
      (node (ref "J2") (pin "1") (pinfunction "DAT2_1") (pintype "passive"))
      (node (ref "R3") (pin "2") (pinfunction "2_2") (pintype "passive"))
    )
    (net (code "236") (name "SDIO_D3") (class "Default")
      (node (ref "IC8") (pin "112") (pinfunction "PC11_112") (pintype "bidirectional"))
      (node (ref "J2") (pin "2") (pinfunction "CD/DAT3_2") (pintype "passive"))
      (node (ref "R1") (pin "2") (pinfunction "2_2") (pintype "passive"))
    )
    (net (code "237") (name "SD_DETECT") (class "Default")
      (node (ref "IC8") (pin "86") (pinfunction "PD15_86") (pintype "bidirectional"))
      (node (ref "J2") (pin "SW1") (pinfunction "SW1_SW1") (pintype "passive"))
    )
    (net (code "238") (name "SLOW_DIN#0") (class "Default")
      (node (ref "IC8") (pin "139") (pinfunction "PB8_139") (pintype "bidirectional"))
      (node (ref "Q1") (pin "5") (pinfunction "G_5") (pintype "passive"))
    )
    (net (code "239") (name "SLOW_DIN#1") (class "Default")
      (node (ref "IC8") (pin "140") (pinfunction "PB9_140") (pintype "bidirectional"))
      (node (ref "Q1") (pin "2") (pinfunction "G_2") (pintype "passive"))
    )
    (net (code "240") (name "SWCLK") (class "Default")
      (node (ref "IC8") (pin "109") (pinfunction "PA14_109") (pintype "bidirectional"))
      (node (ref "X2") (pin "2") (pinfunction "1_2") (pintype "passive"))
    )
    (net (code "241") (name "SWDIO") (class "Default")
      (node (ref "IC8") (pin "105") (pinfunction "PA13_105") (pintype "bidirectional"))
      (node (ref "X2") (pin "4") (pinfunction "1_4") (pintype "passive"))
    )
    (net (code "242") (name "SYNC") (class "Default")
      (node (ref "IC3") (pin "14") (pinfunction "B1_14") (pintype "output"))
      (node (ref "IC8") (pin "80") (pinfunction "PD11_80") (pintype "bidirectional"))
    )
    (net (code "243") (name "TEMP_SW#1") (class "Default")
      (node (ref "IC21") (pin "3") (pinfunction "IN_3") (pintype "input"))
      (node (ref "IC8") (pin "7") (pinfunction "PC13_7") (pintype "bidirectional"))
    )
    (net (code "244") (name "TEMP_SW#2") (class "Default")
      (node (ref "IC26") (pin "3") (pinfunction "IN_3") (pintype "input"))
      (node (ref "IC8") (pin "8") (pinfunction "PC14-OSC32_IN_8") (pintype "bidirectional"))
    )
    (net (code "245") (name "VOLT_SW0") (class "Default")
      (node (ref "IC31") (pin "3") (pinfunction "IN_3") (pintype "input"))
      (node (ref "IC8") (pin "10") (pinfunction "PF0_10") (pintype "bidirectional"))
    )
    (net (code "246") (name "VOLT_SW1") (class "Default")
      (node (ref "IC32") (pin "3") (pinfunction "IN_3") (pintype "input"))
      (node (ref "IC8") (pin "11") (pinfunction "PF1_11") (pintype "bidirectional"))
    )
    (net (code "247") (name "VOLT_SW2") (class "Default")
      (node (ref "IC33") (pin "3") (pinfunction "IN_3") (pintype "input"))
      (node (ref "IC8") (pin "12") (pinfunction "PF2_12") (pintype "bidirectional"))
    )
    (net (code "248") (name "VOLT_SW3") (class "Default")
      (node (ref "IC34") (pin "3") (pinfunction "IN_3") (pintype "input"))
      (node (ref "IC8") (pin "13") (pinfunction "PF3_13") (pintype "bidirectional"))
    )
    (net (code "249") (name "unconnected-(IC8A-PA2-Pad36)") (class "Default")
      (node (ref "IC8") (pin "36") (pinfunction "PA2_36") (pintype "bidirectional"))
    )
    (net (code "250") (name "unconnected-(IC8A-PA3-Pad37)") (class "Default")
      (node (ref "IC8") (pin "37") (pinfunction "PA3_37") (pintype "bidirectional"))
    )
    (net (code "251") (name "unconnected-(IC8A-PA10-Pad102)") (class "Default")
      (node (ref "IC8") (pin "102") (pinfunction "PA10_102") (pintype "bidirectional"))
    )
    (net (code "252") (name "unconnected-(IC8A-PA11-Pad103)") (class "Default")
      (node (ref "IC8") (pin "103") (pinfunction "PA11_103") (pintype "bidirectional"))
    )
    (net (code "253") (name "unconnected-(IC8A-PA12-Pad104)") (class "Default")
      (node (ref "IC8") (pin "104") (pinfunction "PA12_104") (pintype "bidirectional"))
    )
    (net (code "254") (name "unconnected-(IC8A-PA15-Pad110)") (class "Default")
      (node (ref "IC8") (pin "110") (pinfunction "PA15_110") (pintype "bidirectional"))
    )
    (net (code "255") (name "unconnected-(IC8A-PC0-Pad26)") (class "Default")
      (node (ref "IC8") (pin "26") (pinfunction "PC0_26") (pintype "bidirectional"))
    )
    (net (code "256") (name "unconnected-(IC8A-PC2-Pad28)") (class "Default")
      (node (ref "IC8") (pin "28") (pinfunction "PC2_28") (pintype "bidirectional"))
    )
    (net (code "257") (name "unconnected-(IC8A-PC3-Pad29)") (class "Default")
      (node (ref "IC8") (pin "29") (pinfunction "PC3_29") (pintype "bidirectional"))
    )
    (net (code "258") (name "unconnected-(IC8A-PD0-Pad114)") (class "Default")
      (node (ref "IC8") (pin "114") (pinfunction "PD0_114") (pintype "bidirectional"))
    )
    (net (code "259") (name "unconnected-(IC8A-PD1-Pad115)") (class "Default")
      (node (ref "IC8") (pin "115") (pinfunction "PD1_115") (pintype "bidirectional"))
    )
    (net (code "260") (name "unconnected-(IC8A-PD8-Pad77)") (class "Default")
      (node (ref "IC8") (pin "77") (pinfunction "PD8_77") (pintype "bidirectional"))
    )
    (net (code "261") (name "unconnected-(IC8A-PD9-Pad78)") (class "Default")
      (node (ref "IC8") (pin "78") (pinfunction "PD9_78") (pintype "bidirectional"))
    )
    (net (code "262") (name "unconnected-(IC8A-PD10-Pad79)") (class "Default")
      (node (ref "IC8") (pin "79") (pinfunction "PD10_79") (pintype "bidirectional"))
    )
    (net (code "263") (name "unconnected-(IC8A-PD14-Pad85)") (class "Default")
      (node (ref "IC8") (pin "85") (pinfunction "PD14_85") (pintype "bidirectional"))
    )
    (net (code "264") (name "unconnected-(IC8B-PE0-Pad141)") (class "Default")
      (node (ref "IC8") (pin "141") (pinfunction "PE0_141") (pintype "bidirectional"))
    )
    (net (code "265") (name "unconnected-(IC8B-PE1-Pad142)") (class "Default")
      (node (ref "IC8") (pin "142") (pinfunction "PE1_142") (pintype "bidirectional"))
    )
    (net (code "266") (name "unconnected-(IC8B-PE7-Pad58)") (class "Default")
      (node (ref "IC8") (pin "58") (pinfunction "PE7_58") (pintype "bidirectional"))
    )
    (net (code "267") (name "unconnected-(IC8B-PE8-Pad59)") (class "Default")
      (node (ref "IC8") (pin "59") (pinfunction "PE8_59") (pintype "bidirectional"))
    )
    (net (code "268") (name "unconnected-(IC8B-PE9-Pad60)") (class "Default")
      (node (ref "IC8") (pin "60") (pinfunction "PE9_60") (pintype "bidirectional"))
    )
    (net (code "269") (name "unconnected-(IC8B-PE10-Pad63)") (class "Default")
      (node (ref "IC8") (pin "63") (pinfunction "PE10_63") (pintype "bidirectional"))
    )
    (net (code "270") (name "unconnected-(IC8B-PE11-Pad64)") (class "Default")
      (node (ref "IC8") (pin "64") (pinfunction "PE11_64") (pintype "bidirectional"))
    )
    (net (code "271") (name "unconnected-(IC8B-PE12-Pad65)") (class "Default")
      (node (ref "IC8") (pin "65") (pinfunction "PE12_65") (pintype "bidirectional"))
    )
    (net (code "272") (name "unconnected-(IC8B-PE13-Pad66)") (class "Default")
      (node (ref "IC8") (pin "66") (pinfunction "PE13_66") (pintype "bidirectional"))
    )
    (net (code "273") (name "unconnected-(IC8B-PE14-Pad67)") (class "Default")
      (node (ref "IC8") (pin "67") (pinfunction "PE14_67") (pintype "bidirectional"))
    )
    (net (code "274") (name "unconnected-(IC8B-PE15-Pad68)") (class "Default")
      (node (ref "IC8") (pin "68") (pinfunction "PE15_68") (pintype "bidirectional"))
    )
    (net (code "275") (name "unconnected-(IC8B-PF4-Pad14)") (class "Default")
      (node (ref "IC8") (pin "14") (pinfunction "PF4_14") (pintype "bidirectional"))
    )
    (net (code "276") (name "unconnected-(IC8B-PF5-Pad15)") (class "Default")
      (node (ref "IC8") (pin "15") (pinfunction "PF5_15") (pintype "bidirectional"))
    )
    (net (code "277") (name "unconnected-(IC8B-PF11-Pad49)") (class "Default")
      (node (ref "IC8") (pin "49") (pinfunction "PF11_49") (pintype "bidirectional"))
    )
    (net (code "278") (name "unconnected-(IC8B-PF12-Pad50)") (class "Default")
      (node (ref "IC8") (pin "50") (pinfunction "PF12_50") (pintype "bidirectional"))
    )
    (net (code "279") (name "unconnected-(IC8B-PF13-Pad53)") (class "Default")
      (node (ref "IC8") (pin "53") (pinfunction "PF13_53") (pintype "bidirectional"))
    )
    (net (code "280") (name "unconnected-(IC8B-PF14-Pad54)") (class "Default")
      (node (ref "IC8") (pin "54") (pinfunction "PF14_54") (pintype "bidirectional"))
    )
    (net (code "281") (name "unconnected-(IC8B-PF15-Pad55)") (class "Default")
      (node (ref "IC8") (pin "55") (pinfunction "PF15_55") (pintype "bidirectional"))
    )
    (net (code "282") (name "unconnected-(IC8B-PG0-Pad56)") (class "Default")
      (node (ref "IC8") (pin "56") (pinfunction "PG0_56") (pintype "bidirectional"))
    )
    (net (code "283") (name "unconnected-(IC8B-PG1-Pad57)") (class "Default")
      (node (ref "IC8") (pin "57") (pinfunction "PG1_57") (pintype "bidirectional"))
    )
    (net (code "284") (name "unconnected-(IC8B-PG2-Pad87)") (class "Default")
      (node (ref "IC8") (pin "87") (pinfunction "PG2_87") (pintype "bidirectional"))
    )
    (net (code "285") (name "unconnected-(IC8B-PG3-Pad88)") (class "Default")
      (node (ref "IC8") (pin "88") (pinfunction "PG3_88") (pintype "bidirectional"))
    )
    (net (code "286") (name "unconnected-(IC8B-PG4-Pad89)") (class "Default")
      (node (ref "IC8") (pin "89") (pinfunction "PG4_89") (pintype "bidirectional"))
    )
    (net (code "287") (name "unconnected-(IC8B-PG5-Pad90)") (class "Default")
      (node (ref "IC8") (pin "90") (pinfunction "PG5_90") (pintype "bidirectional"))
    )
    (net (code "288") (name "unconnected-(IC8B-PG8-Pad93)") (class "Default")
      (node (ref "IC8") (pin "93") (pinfunction "PG8_93") (pintype "bidirectional"))
    )
    (net (code "289") (name "unconnected-(IC8B-PG15-Pad132)") (class "Default")
      (node (ref "IC8") (pin "132") (pinfunction "PG15_132") (pintype "bidirectional"))
    )
    (net (code "290") (name "unconnected-(IC10-BOOST-Pad20)") (class "Default")
      (node (ref "IC10") (pin "20") (pinfunction "BOOST_20") (pintype "output"))
    )
    (net (code "291") (name "unconnected-(IC11-BOOST-Pad20)") (class "Default")
      (node (ref "IC11") (pin "20") (pinfunction "BOOST_20") (pintype "output"))
    )
    (net (code "292") (name "unconnected-(IC36-AUX_IN-Pad10)") (class "Default")
      (node (ref "IC36") (pin "10") (pinfunction "AUX_IN_10") (pintype "input"))
    )
    (net (code "293") (name "~{ADC_CS}") (class "Default")
      (node (ref "IC36") (pin "38") (pinfunction "~{CS}_38") (pintype "input"))
      (node (ref "RN4") (pin "2") (pinfunction "1_2") (pintype "passive"))
    )
    (net (code "294") (name "~{DAC_ALARM}") (class "Default")
      (node (ref "IC10") (pin "3") (pinfunction "~{ALARM}_3") (pintype "output"))
      (node (ref "IC11") (pin "3") (pinfunction "~{ALARM}_3") (pintype "output"))
      (node (ref "IC8") (pin "9") (pinfunction "PC15-OSC32_OUT_9") (pintype "bidirectional"))
      (node (ref "R12") (pin "2") (pinfunction "2_2") (pintype "passive"))
    )
    (net (code "295") (name "~{DAC_CS_DUAL}") (class "Default")
      (node (ref "IC13") (pin "6") (pinfunction "~{SYNC}_6") (pintype "input"))
      (node (ref "RN5") (pin "1") (pinfunction "1_1") (pintype "passive"))
    )
    (net (code "296") (name "~{OUT_FAULT}") (class "Default")
      (node (ref "IC15") (pin "1") (pinfunction "~{FAULT}_1") (pintype "output"))
      (node (ref "IC16") (pin "1") (pinfunction "~{FAULT}_1") (pintype "output"))
      (node (ref "IC17") (pin "1") (pinfunction "~{FAULT}_1") (pintype "output"))
      (node (ref "IC18") (pin "1") (pinfunction "~{FAULT}_1") (pintype "output"))
      (node (ref "IC8") (pin "48") (pinfunction "PB2-BOOT1_48") (pintype "bidirectional"))
      (node (ref "R30") (pin "2") (pinfunction "2_2") (pintype "passive"))
    )
    (net (code "297") (name "~{RESET}") (class "Default")
      (node (ref "C24") (pin "1") (pinfunction "1_1") (pintype "passive"))
      (node (ref "IC13") (pin "5") (pinfunction "~{CLR}_5") (pintype "input"))
      (node (ref "IC3") (pin "12") (pinfunction "B3_12") (pintype "output"))
      (node (ref "IC36") (pin "2") (pinfunction "~{RST/}PD_2") (pintype "input"))
      (node (ref "IC8") (pin "25") (pinfunction "NRST_25") (pintype "bidirectional"))
      (node (ref "R6") (pin "2") (pinfunction "2_2") (pintype "passive"))
    )
  )
)
